# module_RevC_panelized.net
KiCad netlist of a schematic drawn in EAGLE
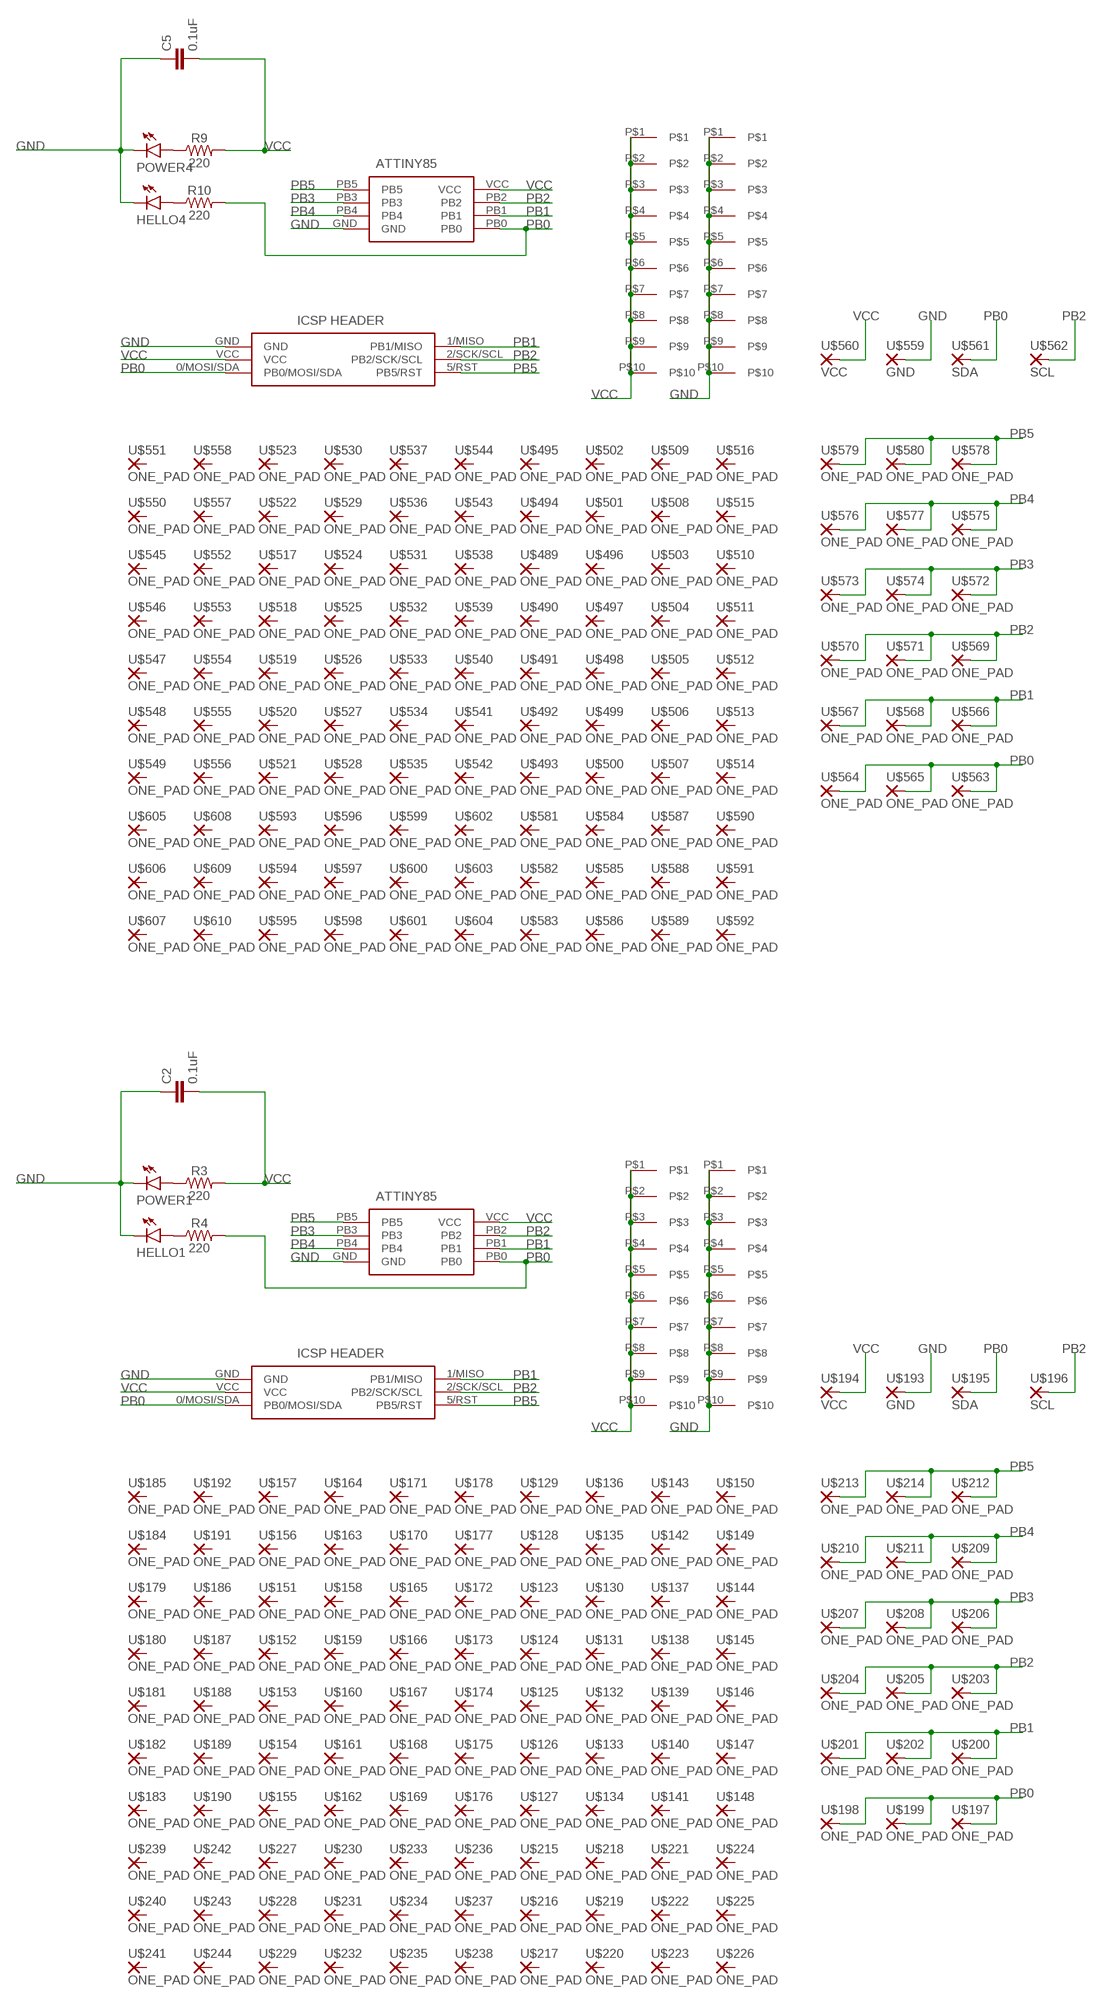
[diagram p0: schematic, sheet 1, part 1 of 2]
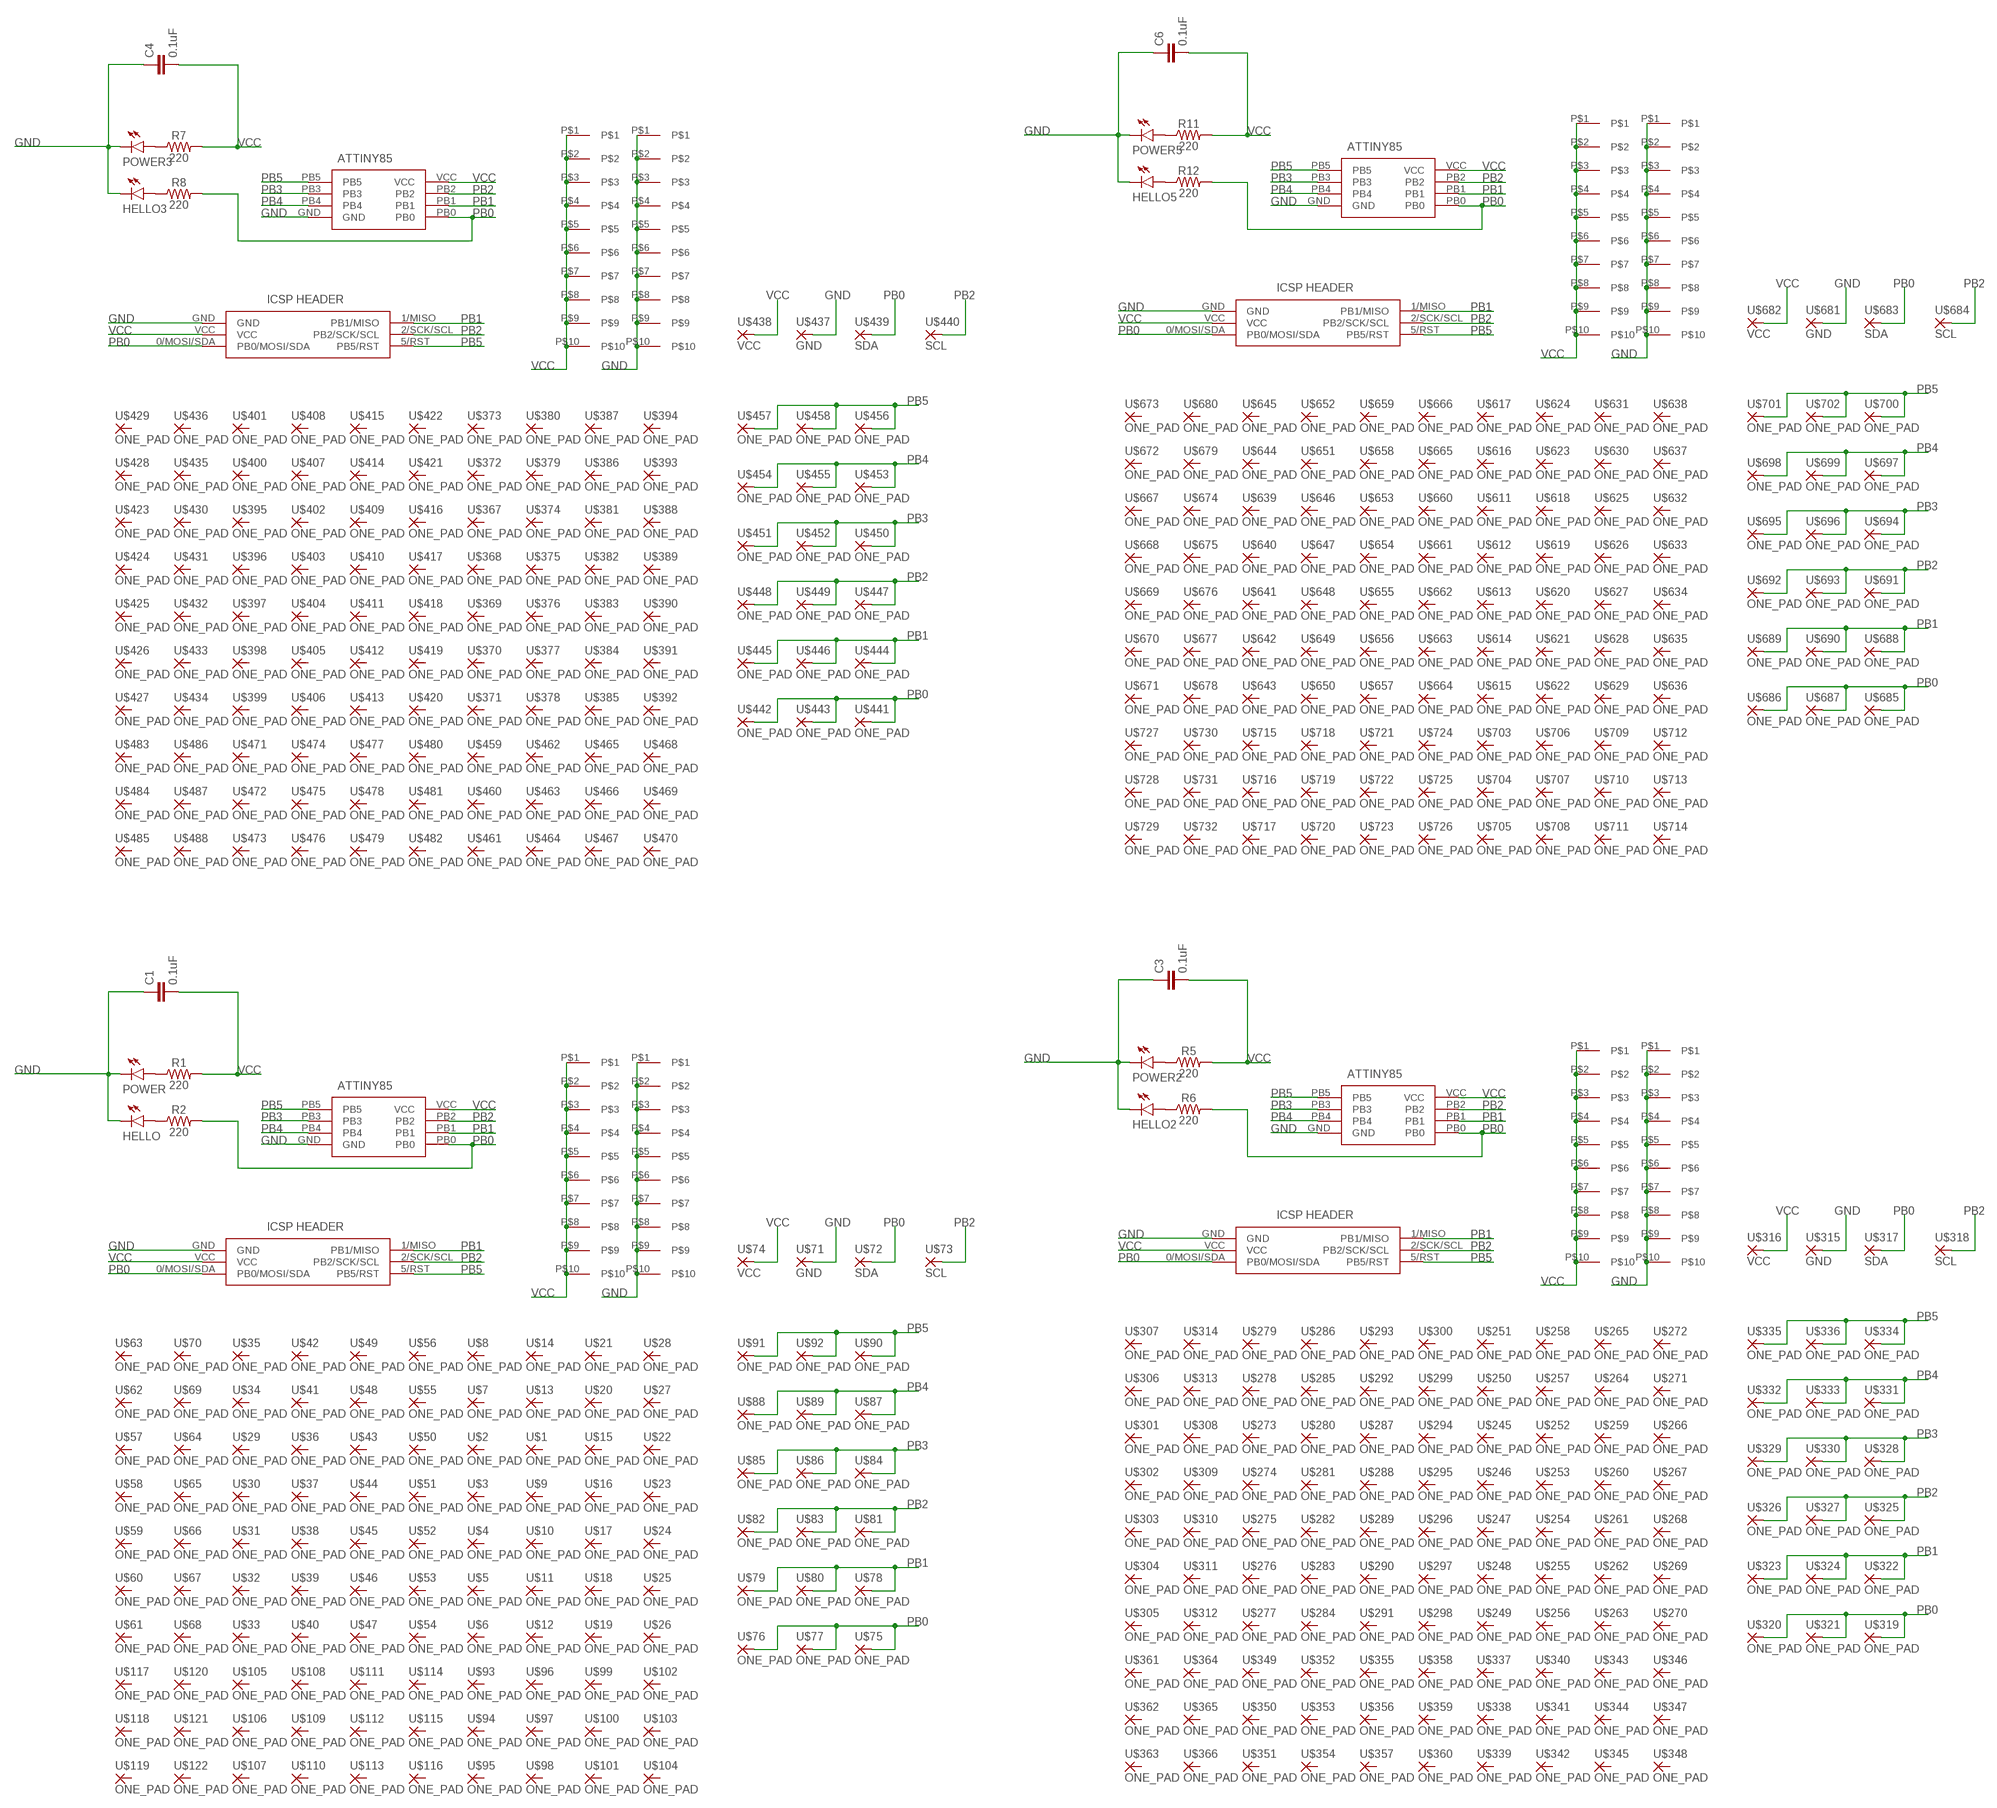
[diagram p1: schematic, sheet 1, part 2 of 2]

(export (version "E")
  (design (tool "Eeschema 10.0.6"))
  (components
    (comp (ref "C1")
      (value "0.1uF")
      (footprint "eagle-import:0603")
      (libsource (lib "eagle-import") (part "0.1UF-0603-25V-5%"))
    )
    (comp (ref "C2")
      (value "0.1uF")
      (footprint "eagle-import:0603")
      (libsource (lib "eagle-import") (part "0.1UF-0603-25V-5%"))
    )
    (comp (ref "C3")
      (value "0.1uF")
      (footprint "eagle-import:0603")
      (libsource (lib "eagle-import") (part "0.1UF-0603-25V-5%"))
    )
    (comp (ref "C4")
      (value "0.1uF")
      (footprint "eagle-import:0603")
      (libsource (lib "eagle-import") (part "0.1UF-0603-25V-5%"))
    )
    (comp (ref "C5")
      (value "0.1uF")
      (footprint "eagle-import:0603")
      (libsource (lib "eagle-import") (part "0.1UF-0603-25V-5%"))
    )
    (comp (ref "C6")
      (value "0.1uF")
      (footprint "eagle-import:0603")
      (libsource (lib "eagle-import") (part "0.1UF-0603-25V-5%"))
    )
    (comp (ref "GND")
      (value "10X-PADS")
      (footprint "eagle-import:10X-PADS")
      (libsource (lib "eagle-import") (part "10X-PADS"))
    )
    (comp (ref "GND1")
      (value "10X-PADS")
      (footprint "eagle-import:10X-PADS")
      (libsource (lib "eagle-import") (part "10X-PADS"))
    )
    (comp (ref "GND2")
      (value "10X-PADS")
      (footprint "eagle-import:10X-PADS")
      (libsource (lib "eagle-import") (part "10X-PADS"))
    )
    (comp (ref "GND3")
      (value "10X-PADS")
      (footprint "eagle-import:10X-PADS")
      (libsource (lib "eagle-import") (part "10X-PADS"))
    )
    (comp (ref "GND4")
      (value "10X-PADS")
      (footprint "eagle-import:10X-PADS")
      (libsource (lib "eagle-import") (part "10X-PADS"))
    )
    (comp (ref "GND5")
      (value "10X-PADS")
      (footprint "eagle-import:10X-PADS")
      (libsource (lib "eagle-import") (part "10X-PADS"))
    )
    (comp (ref "HELLO")
      (value "LED3MM")
      (footprint "eagle-import:LED3MM")
      (libsource (lib "eagle-import") (part "LED3MM"))
    )
    (comp (ref "HELLO1")
      (value "LED3MM")
      (footprint "eagle-import:LED3MM")
      (libsource (lib "eagle-import") (part "LED3MM"))
    )
    (comp (ref "HELLO2")
      (value "LED3MM")
      (footprint "eagle-import:LED3MM")
      (libsource (lib "eagle-import") (part "LED3MM"))
    )
    (comp (ref "HELLO3")
      (value "LED3MM")
      (footprint "eagle-import:LED3MM")
      (libsource (lib "eagle-import") (part "LED3MM"))
    )
    (comp (ref "HELLO4")
      (value "LED3MM")
      (footprint "eagle-import:LED3MM")
      (libsource (lib "eagle-import") (part "LED3MM"))
    )
    (comp (ref "HELLO5")
      (value "LED3MM")
      (footprint "eagle-import:LED3MM")
      (libsource (lib "eagle-import") (part "LED3MM"))
    )
    (comp (ref "IC1")
      (value "ATTINY85-20SU")
      (footprint "eagle-import:SOT127P798X216-8N")
      (fields (field (name "RS_PART_NUMBER") "1331674"))
      (libsource (lib "eagle-import") (part "ATTINY85-20SU"))
    )
    (comp (ref "IC2")
      (value "ATTINY85-20SU")
      (footprint "eagle-import:SOT127P798X216-8N")
      (fields (field (name "RS_PART_NUMBER") "1331674"))
      (libsource (lib "eagle-import") (part "ATTINY85-20SU"))
    )
    (comp (ref "IC3")
      (value "ATTINY85-20SU")
      (footprint "eagle-import:SOT127P798X216-8N")
      (fields (field (name "RS_PART_NUMBER") "1331674"))
      (libsource (lib "eagle-import") (part "ATTINY85-20SU"))
    )
    (comp (ref "IC4")
      (value "ATTINY85-20SU")
      (footprint "eagle-import:SOT127P798X216-8N")
      (fields (field (name "RS_PART_NUMBER") "1331674"))
      (libsource (lib "eagle-import") (part "ATTINY85-20SU"))
    )
    (comp (ref "IC5")
      (value "ATTINY85-20SU")
      (footprint "eagle-import:SOT127P798X216-8N")
      (fields (field (name "RS_PART_NUMBER") "1331674"))
      (libsource (lib "eagle-import") (part "ATTINY85-20SU"))
    )
    (comp (ref "IC6")
      (value "ATTINY85-20SU")
      (footprint "eagle-import:SOT127P798X216-8N")
      (fields (field (name "RS_PART_NUMBER") "1331674"))
      (libsource (lib "eagle-import") (part "ATTINY85-20SU"))
    )
    (comp (ref "J1")
      (value "M20-9980346")
      (footprint "eagle-import:HDRV6W64P254_2X3_762X508X868P")
      (fields (field (name "RS_PART_NUMBER") "7457046P"))
      (libsource (lib "eagle-import") (part "M20-9980346"))
    )
    (comp (ref "J2")
      (value "M20-9980346")
      (footprint "eagle-import:HDRV6W64P254_2X3_762X508X868P")
      (fields (field (name "RS_PART_NUMBER") "7457046P"))
      (libsource (lib "eagle-import") (part "M20-9980346"))
    )
    (comp (ref "J3")
      (value "M20-9980346")
      (footprint "eagle-import:HDRV6W64P254_2X3_762X508X868P")
      (fields (field (name "RS_PART_NUMBER") "7457046P"))
      (libsource (lib "eagle-import") (part "M20-9980346"))
    )
    (comp (ref "J4")
      (value "M20-9980346")
      (footprint "eagle-import:HDRV6W64P254_2X3_762X508X868P")
      (fields (field (name "RS_PART_NUMBER") "7457046P"))
      (libsource (lib "eagle-import") (part "M20-9980346"))
    )
    (comp (ref "J5")
      (value "M20-9980346")
      (footprint "eagle-import:HDRV6W64P254_2X3_762X508X868P")
      (fields (field (name "RS_PART_NUMBER") "7457046P"))
      (libsource (lib "eagle-import") (part "M20-9980346"))
    )
    (comp (ref "J6")
      (value "M20-9980346")
      (footprint "eagle-import:HDRV6W64P254_2X3_762X508X868P")
      (fields (field (name "RS_PART_NUMBER") "7457046P"))
      (libsource (lib "eagle-import") (part "M20-9980346"))
    )
    (comp (ref "POWER")
      (value "LED3MM")
      (footprint "eagle-import:LED3MM")
      (libsource (lib "eagle-import") (part "LED3MM"))
    )
    (comp (ref "POWER1")
      (value "LED3MM")
      (footprint "eagle-import:LED3MM")
      (libsource (lib "eagle-import") (part "LED3MM"))
    )
    (comp (ref "POWER2")
      (value "LED3MM")
      (footprint "eagle-import:LED3MM")
      (libsource (lib "eagle-import") (part "LED3MM"))
    )
    (comp (ref "POWER3")
      (value "LED3MM")
      (footprint "eagle-import:LED3MM")
      (libsource (lib "eagle-import") (part "LED3MM"))
    )
    (comp (ref "POWER4")
      (value "LED3MM")
      (footprint "eagle-import:LED3MM")
      (libsource (lib "eagle-import") (part "LED3MM"))
    )
    (comp (ref "POWER5")
      (value "LED3MM")
      (footprint "eagle-import:LED3MM")
      (libsource (lib "eagle-import") (part "LED3MM"))
    )
    (comp (ref "R1")
      (value "220")
      (footprint "eagle-import:AXIAL-0.3")
      (libsource (lib "eagle-import") (part "RESISTORAXIAL-0.3"))
    )
    (comp (ref "R2")
      (value "220")
      (footprint "eagle-import:AXIAL-0.3")
      (libsource (lib "eagle-import") (part "RESISTORAXIAL-0.3"))
    )
    (comp (ref "R3")
      (value "220")
      (footprint "eagle-import:AXIAL-0.3")
      (libsource (lib "eagle-import") (part "RESISTORAXIAL-0.3"))
    )
    (comp (ref "R4")
      (value "220")
      (footprint "eagle-import:AXIAL-0.3")
      (libsource (lib "eagle-import") (part "RESISTORAXIAL-0.3"))
    )
    (comp (ref "R5")
      (value "220")
      (footprint "eagle-import:AXIAL-0.3")
      (libsource (lib "eagle-import") (part "RESISTORAXIAL-0.3"))
    )
    (comp (ref "R6")
      (value "220")
      (footprint "eagle-import:AXIAL-0.3")
      (libsource (lib "eagle-import") (part "RESISTORAXIAL-0.3"))
    )
    (comp (ref "R7")
      (value "220")
      (footprint "eagle-import:AXIAL-0.3")
      (libsource (lib "eagle-import") (part "RESISTORAXIAL-0.3"))
    )
    (comp (ref "R8")
      (value "220")
      (footprint "eagle-import:AXIAL-0.3")
      (libsource (lib "eagle-import") (part "RESISTORAXIAL-0.3"))
    )
    (comp (ref "R9")
      (value "220")
      (footprint "eagle-import:AXIAL-0.3")
      (libsource (lib "eagle-import") (part "RESISTORAXIAL-0.3"))
    )
    (comp (ref "R10")
      (value "220")
      (footprint "eagle-import:AXIAL-0.3")
      (libsource (lib "eagle-import") (part "RESISTORAXIAL-0.3"))
    )
    (comp (ref "R11")
      (value "220")
      (footprint "eagle-import:AXIAL-0.3")
      (libsource (lib "eagle-import") (part "RESISTORAXIAL-0.3"))
    )
    (comp (ref "R12")
      (value "220")
      (footprint "eagle-import:AXIAL-0.3")
      (libsource (lib "eagle-import") (part "RESISTORAXIAL-0.3"))
    )
    (comp (ref "U$1")
      (value "ONE_PAD")
      (footprint "eagle-import:1X01")
      (libsource (lib "eagle-import") (part "ONE_PAD"))
    )
    (comp (ref "U$2")
      (value "ONE_PAD")
      (footprint "eagle-import:1X01")
      (libsource (lib "eagle-import") (part "ONE_PAD"))
    )
    (comp (ref "U$3")
      (value "ONE_PAD")
      (footprint "eagle-import:1X01")
      (libsource (lib "eagle-import") (part "ONE_PAD"))
    )
    (comp (ref "U$4")
      (value "ONE_PAD")
      (footprint "eagle-import:1X01")
      (libsource (lib "eagle-import") (part "ONE_PAD"))
    )
    (comp (ref "U$5")
      (value "ONE_PAD")
      (footprint "eagle-import:1X01")
      (libsource (lib "eagle-import") (part "ONE_PAD"))
    )
    (comp (ref "U$6")
      (value "ONE_PAD")
      (footprint "eagle-import:1X01")
      (libsource (lib "eagle-import") (part "ONE_PAD"))
    )
    (comp (ref "U$7")
      (value "ONE_PAD")
      (footprint "eagle-import:1X01")
      (libsource (lib "eagle-import") (part "ONE_PAD"))
    )
    (comp (ref "U$8")
      (value "ONE_PAD")
      (footprint "eagle-import:1X01")
      (libsource (lib "eagle-import") (part "ONE_PAD"))
    )
    (comp (ref "U$9")
      (value "ONE_PAD")
      (footprint "eagle-import:1X01")
      (libsource (lib "eagle-import") (part "ONE_PAD"))
    )
    (comp (ref "U$10")
      (value "ONE_PAD")
      (footprint "eagle-import:1X01")
      (libsource (lib "eagle-import") (part "ONE_PAD"))
    )
    (comp (ref "U$11")
      (value "ONE_PAD")
      (footprint "eagle-import:1X01")
      (libsource (lib "eagle-import") (part "ONE_PAD"))
    )
    (comp (ref "U$12")
      (value "ONE_PAD")
      (footprint "eagle-import:1X01")
      (libsource (lib "eagle-import") (part "ONE_PAD"))
    )
    (comp (ref "U$13")
      (value "ONE_PAD")
      (footprint "eagle-import:1X01")
      (libsource (lib "eagle-import") (part "ONE_PAD"))
    )
    (comp (ref "U$14")
      (value "ONE_PAD")
      (footprint "eagle-import:1X01")
      (libsource (lib "eagle-import") (part "ONE_PAD"))
    )
    (comp (ref "U$15")
      (value "ONE_PAD")
      (footprint "eagle-import:1X01")
      (libsource (lib "eagle-import") (part "ONE_PAD"))
    )
    (comp (ref "U$16")
      (value "ONE_PAD")
      (footprint "eagle-import:1X01")
      (libsource (lib "eagle-import") (part "ONE_PAD"))
    )
    (comp (ref "U$17")
      (value "ONE_PAD")
      (footprint "eagle-import:1X01")
      (libsource (lib "eagle-import") (part "ONE_PAD"))
    )
    (comp (ref "U$18")
      (value "ONE_PAD")
      (footprint "eagle-import:1X01")
      (libsource (lib "eagle-import") (part "ONE_PAD"))
    )
    (comp (ref "U$19")
      (value "ONE_PAD")
      (footprint "eagle-import:1X01")
      (libsource (lib "eagle-import") (part "ONE_PAD"))
    )
    (comp (ref "U$20")
      (value "ONE_PAD")
      (footprint "eagle-import:1X01")
      (libsource (lib "eagle-import") (part "ONE_PAD"))
    )
    (comp (ref "U$21")
      (value "ONE_PAD")
      (footprint "eagle-import:1X01")
      (libsource (lib "eagle-import") (part "ONE_PAD"))
    )
    (comp (ref "U$22")
      (value "ONE_PAD")
      (footprint "eagle-import:1X01")
      (libsource (lib "eagle-import") (part "ONE_PAD"))
    )
    (comp (ref "U$23")
      (value "ONE_PAD")
      (footprint "eagle-import:1X01")
      (libsource (lib "eagle-import") (part "ONE_PAD"))
    )
    (comp (ref "U$24")
      (value "ONE_PAD")
      (footprint "eagle-import:1X01")
      (libsource (lib "eagle-import") (part "ONE_PAD"))
    )
    (comp (ref "U$25")
      (value "ONE_PAD")
      (footprint "eagle-import:1X01")
      (libsource (lib "eagle-import") (part "ONE_PAD"))
    )
    (comp (ref "U$26")
      (value "ONE_PAD")
      (footprint "eagle-import:1X01")
      (libsource (lib "eagle-import") (part "ONE_PAD"))
    )
    (comp (ref "U$27")
      (value "ONE_PAD")
      (footprint "eagle-import:1X01")
      (libsource (lib "eagle-import") (part "ONE_PAD"))
    )
    (comp (ref "U$28")
      (value "ONE_PAD")
      (footprint "eagle-import:1X01")
      (libsource (lib "eagle-import") (part "ONE_PAD"))
    )
    (comp (ref "U$29")
      (value "ONE_PAD")
      (footprint "eagle-import:1X01")
      (libsource (lib "eagle-import") (part "ONE_PAD"))
    )
    (comp (ref "U$30")
      (value "ONE_PAD")
      (footprint "eagle-import:1X01")
      (libsource (lib "eagle-import") (part "ONE_PAD"))
    )
    (comp (ref "U$31")
      (value "ONE_PAD")
      (footprint "eagle-import:1X01")
      (libsource (lib "eagle-import") (part "ONE_PAD"))
    )
    (comp (ref "U$32")
      (value "ONE_PAD")
      (footprint "eagle-import:1X01")
      (libsource (lib "eagle-import") (part "ONE_PAD"))
    )
    (comp (ref "U$33")
      (value "ONE_PAD")
      (footprint "eagle-import:1X01")
      (libsource (lib "eagle-import") (part "ONE_PAD"))
    )
    (comp (ref "U$34")
      (value "ONE_PAD")
      (footprint "eagle-import:1X01")
      (libsource (lib "eagle-import") (part "ONE_PAD"))
    )
    (comp (ref "U$35")
      (value "ONE_PAD")
      (footprint "eagle-import:1X01")
      (libsource (lib "eagle-import") (part "ONE_PAD"))
    )
    (comp (ref "U$36")
      (value "ONE_PAD")
      (footprint "eagle-import:1X01")
      (libsource (lib "eagle-import") (part "ONE_PAD"))
    )
    (comp (ref "U$37")
      (value "ONE_PAD")
      (footprint "eagle-import:1X01")
      (libsource (lib "eagle-import") (part "ONE_PAD"))
    )
    (comp (ref "U$38")
      (value "ONE_PAD")
      (footprint "eagle-import:1X01")
      (libsource (lib "eagle-import") (part "ONE_PAD"))
    )
    (comp (ref "U$39")
      (value "ONE_PAD")
      (footprint "eagle-import:1X01")
      (libsource (lib "eagle-import") (part "ONE_PAD"))
    )
    (comp (ref "U$40")
      (value "ONE_PAD")
      (footprint "eagle-import:1X01")
      (libsource (lib "eagle-import") (part "ONE_PAD"))
    )
    (comp (ref "U$41")
      (value "ONE_PAD")
      (footprint "eagle-import:1X01")
      (libsource (lib "eagle-import") (part "ONE_PAD"))
    )
    (comp (ref "U$42")
      (value "ONE_PAD")
      (footprint "eagle-import:1X01")
      (libsource (lib "eagle-import") (part "ONE_PAD"))
    )
    (comp (ref "U$43")
      (value "ONE_PAD")
      (footprint "eagle-import:1X01")
      (libsource (lib "eagle-import") (part "ONE_PAD"))
    )
    (comp (ref "U$44")
      (value "ONE_PAD")
      (footprint "eagle-import:1X01")
      (libsource (lib "eagle-import") (part "ONE_PAD"))
    )
    (comp (ref "U$45")
      (value "ONE_PAD")
      (footprint "eagle-import:1X01")
      (libsource (lib "eagle-import") (part "ONE_PAD"))
    )
    (comp (ref "U$46")
      (value "ONE_PAD")
      (footprint "eagle-import:1X01")
      (libsource (lib "eagle-import") (part "ONE_PAD"))
    )
    (comp (ref "U$47")
      (value "ONE_PAD")
      (footprint "eagle-import:1X01")
      (libsource (lib "eagle-import") (part "ONE_PAD"))
    )
    (comp (ref "U$48")
      (value "ONE_PAD")
      (footprint "eagle-import:1X01")
      (libsource (lib "eagle-import") (part "ONE_PAD"))
    )
    (comp (ref "U$49")
      (value "ONE_PAD")
      (footprint "eagle-import:1X01")
      (libsource (lib "eagle-import") (part "ONE_PAD"))
    )
    (comp (ref "U$50")
      (value "ONE_PAD")
      (footprint "eagle-import:1X01")
      (libsource (lib "eagle-import") (part "ONE_PAD"))
    )
    (comp (ref "U$51")
      (value "ONE_PAD")
      (footprint "eagle-import:1X01")
      (libsource (lib "eagle-import") (part "ONE_PAD"))
    )
    (comp (ref "U$52")
      (value "ONE_PAD")
      (footprint "eagle-import:1X01")
      (libsource (lib "eagle-import") (part "ONE_PAD"))
    )
    (comp (ref "U$53")
      (value "ONE_PAD")
      (footprint "eagle-import:1X01")
      (libsource (lib "eagle-import") (part "ONE_PAD"))
    )
    (comp (ref "U$54")
      (value "ONE_PAD")
      (footprint "eagle-import:1X01")
      (libsource (lib "eagle-import") (part "ONE_PAD"))
    )
    (comp (ref "U$55")
      (value "ONE_PAD")
      (footprint "eagle-import:1X01")
      (libsource (lib "eagle-import") (part "ONE_PAD"))
    )
    (comp (ref "U$56")
      (value "ONE_PAD")
      (footprint "eagle-import:1X01")
      (libsource (lib "eagle-import") (part "ONE_PAD"))
    )
    (comp (ref "U$57")
      (value "ONE_PAD")
      (footprint "eagle-import:1X01")
      (libsource (lib "eagle-import") (part "ONE_PAD"))
    )
    (comp (ref "U$58")
      (value "ONE_PAD")
      (footprint "eagle-import:1X01")
      (libsource (lib "eagle-import") (part "ONE_PAD"))
    )
    (comp (ref "U$59")
      (value "ONE_PAD")
      (footprint "eagle-import:1X01")
      (libsource (lib "eagle-import") (part "ONE_PAD"))
    )
    (comp (ref "U$60")
      (value "ONE_PAD")
      (footprint "eagle-import:1X01")
      (libsource (lib "eagle-import") (part "ONE_PAD"))
    )
    (comp (ref "U$61")
      (value "ONE_PAD")
      (footprint "eagle-import:1X01")
      (libsource (lib "eagle-import") (part "ONE_PAD"))
    )
    (comp (ref "U$62")
      (value "ONE_PAD")
      (footprint "eagle-import:1X01")
      (libsource (lib "eagle-import") (part "ONE_PAD"))
    )
    (comp (ref "U$63")
      (value "ONE_PAD")
      (footprint "eagle-import:1X01")
      (libsource (lib "eagle-import") (part "ONE_PAD"))
    )
    (comp (ref "U$64")
      (value "ONE_PAD")
      (footprint "eagle-import:1X01")
      (libsource (lib "eagle-import") (part "ONE_PAD"))
    )
    (comp (ref "U$65")
      (value "ONE_PAD")
      (footprint "eagle-import:1X01")
      (libsource (lib "eagle-import") (part "ONE_PAD"))
    )
    (comp (ref "U$66")
      (value "ONE_PAD")
      (footprint "eagle-import:1X01")
      (libsource (lib "eagle-import") (part "ONE_PAD"))
    )
    (comp (ref "U$67")
      (value "ONE_PAD")
      (footprint "eagle-import:1X01")
      (libsource (lib "eagle-import") (part "ONE_PAD"))
    )
    (comp (ref "U$68")
      (value "ONE_PAD")
      (footprint "eagle-import:1X01")
      (libsource (lib "eagle-import") (part "ONE_PAD"))
    )
    (comp (ref "U$69")
      (value "ONE_PAD")
      (footprint "eagle-import:1X01")
      (libsource (lib "eagle-import") (part "ONE_PAD"))
    )
    (comp (ref "U$70")
      (value "ONE_PAD")
      (footprint "eagle-import:1X01")
      (libsource (lib "eagle-import") (part "ONE_PAD"))
    )
    (comp (ref "U$71")
      (value "GND")
      (footprint "eagle-import:1X01")
      (libsource (lib "eagle-import") (part "ONE_PAD"))
    )
    (comp (ref "U$72")
      (value "SDA")
      (footprint "eagle-import:1X01")
      (libsource (lib "eagle-import") (part "ONE_PAD"))
    )
    (comp (ref "U$73")
      (value "SCL")
      (footprint "eagle-import:1X01")
      (libsource (lib "eagle-import") (part "ONE_PAD"))
    )
    (comp (ref "U$74")
      (value "VCC")
      (footprint "eagle-import:1X01")
      (libsource (lib "eagle-import") (part "ONE_PAD"))
    )
    (comp (ref "U$75")
      (value "ONE_PAD")
      (footprint "eagle-import:1X01")
      (libsource (lib "eagle-import") (part "ONE_PAD"))
    )
    (comp (ref "U$76")
      (value "ONE_PAD")
      (footprint "eagle-import:1X01")
      (libsource (lib "eagle-import") (part "ONE_PAD"))
    )
    (comp (ref "U$77")
      (value "ONE_PAD")
      (footprint "eagle-import:1X01")
      (libsource (lib "eagle-import") (part "ONE_PAD"))
    )
    (comp (ref "U$78")
      (value "ONE_PAD")
      (footprint "eagle-import:1X01")
      (libsource (lib "eagle-import") (part "ONE_PAD"))
    )
    (comp (ref "U$79")
      (value "ONE_PAD")
      (footprint "eagle-import:1X01")
      (libsource (lib "eagle-import") (part "ONE_PAD"))
    )
    (comp (ref "U$80")
      (value "ONE_PAD")
      (footprint "eagle-import:1X01")
      (libsource (lib "eagle-import") (part "ONE_PAD"))
    )
    (comp (ref "U$81")
      (value "ONE_PAD")
      (footprint "eagle-import:1X01")
      (libsource (lib "eagle-import") (part "ONE_PAD"))
    )
    (comp (ref "U$82")
      (value "ONE_PAD")
      (footprint "eagle-import:1X01")
      (libsource (lib "eagle-import") (part "ONE_PAD"))
    )
    (comp (ref "U$83")
      (value "ONE_PAD")
      (footprint "eagle-import:1X01")
      (libsource (lib "eagle-import") (part "ONE_PAD"))
    )
    (comp (ref "U$84")
      (value "ONE_PAD")
      (footprint "eagle-import:1X01")
      (libsource (lib "eagle-import") (part "ONE_PAD"))
    )
    (comp (ref "U$85")
      (value "ONE_PAD")
      (footprint "eagle-import:1X01")
      (libsource (lib "eagle-import") (part "ONE_PAD"))
    )
    (comp (ref "U$86")
      (value "ONE_PAD")
      (footprint "eagle-import:1X01")
      (libsource (lib "eagle-import") (part "ONE_PAD"))
    )
    (comp (ref "U$87")
      (value "ONE_PAD")
      (footprint "eagle-import:1X01")
      (libsource (lib "eagle-import") (part "ONE_PAD"))
    )
    (comp (ref "U$88")
      (value "ONE_PAD")
      (footprint "eagle-import:1X01")
      (libsource (lib "eagle-import") (part "ONE_PAD"))
    )
    (comp (ref "U$89")
      (value "ONE_PAD")
      (footprint "eagle-import:1X01")
      (libsource (lib "eagle-import") (part "ONE_PAD"))
    )
    (comp (ref "U$90")
      (value "ONE_PAD")
      (footprint "eagle-import:1X01")
      (libsource (lib "eagle-import") (part "ONE_PAD"))
    )
    (comp (ref "U$91")
      (value "ONE_PAD")
      (footprint "eagle-import:1X01")
      (libsource (lib "eagle-import") (part "ONE_PAD"))
    )
    (comp (ref "U$92")
      (value "ONE_PAD")
      (footprint "eagle-import:1X01")
      (libsource (lib "eagle-import") (part "ONE_PAD"))
    )
    (comp (ref "U$93")
      (value "ONE_PAD")
      (footprint "eagle-import:1X01")
      (libsource (lib "eagle-import") (part "ONE_PAD"))
    )
    (comp (ref "U$94")
      (value "ONE_PAD")
      (footprint "eagle-import:1X01")
      (libsource (lib "eagle-import") (part "ONE_PAD"))
    )
    (comp (ref "U$95")
      (value "ONE_PAD")
      (footprint "eagle-import:1X01")
      (libsource (lib "eagle-import") (part "ONE_PAD"))
    )
    (comp (ref "U$96")
      (value "ONE_PAD")
      (footprint "eagle-import:1X01")
      (libsource (lib "eagle-import") (part "ONE_PAD"))
    )
    (comp (ref "U$97")
      (value "ONE_PAD")
      (footprint "eagle-import:1X01")
      (libsource (lib "eagle-import") (part "ONE_PAD"))
    )
    (comp (ref "U$98")
      (value "ONE_PAD")
      (footprint "eagle-import:1X01")
      (libsource (lib "eagle-import") (part "ONE_PAD"))
    )
    (comp (ref "U$99")
      (value "ONE_PAD")
      (footprint "eagle-import:1X01")
      (libsource (lib "eagle-import") (part "ONE_PAD"))
    )
    (comp (ref "U$100")
      (value "ONE_PAD")
      (footprint "eagle-import:1X01")
      (libsource (lib "eagle-import") (part "ONE_PAD"))
    )
    (comp (ref "U$101")
      (value "ONE_PAD")
      (footprint "eagle-import:1X01")
      (libsource (lib "eagle-import") (part "ONE_PAD"))
    )
    (comp (ref "U$102")
      (value "ONE_PAD")
      (footprint "eagle-import:1X01")
      (libsource (lib "eagle-import") (part "ONE_PAD"))
    )
    (comp (ref "U$103")
      (value "ONE_PAD")
      (footprint "eagle-import:1X01")
      (libsource (lib "eagle-import") (part "ONE_PAD"))
    )
    (comp (ref "U$104")
      (value "ONE_PAD")
      (footprint "eagle-import:1X01")
      (libsource (lib "eagle-import") (part "ONE_PAD"))
    )
    (comp (ref "U$105")
      (value "ONE_PAD")
      (footprint "eagle-import:1X01")
      (libsource (lib "eagle-import") (part "ONE_PAD"))
    )
    (comp (ref "U$106")
      (value "ONE_PAD")
      (footprint "eagle-import:1X01")
      (libsource (lib "eagle-import") (part "ONE_PAD"))
    )
    (comp (ref "U$107")
      (value "ONE_PAD")
      (footprint "eagle-import:1X01")
      (libsource (lib "eagle-import") (part "ONE_PAD"))
    )
    (comp (ref "U$108")
      (value "ONE_PAD")
      (footprint "eagle-import:1X01")
      (libsource (lib "eagle-import") (part "ONE_PAD"))
    )
    (comp (ref "U$109")
      (value "ONE_PAD")
      (footprint "eagle-import:1X01")
      (libsource (lib "eagle-import") (part "ONE_PAD"))
    )
    (comp (ref "U$110")
      (value "ONE_PAD")
      (footprint "eagle-import:1X01")
      (libsource (lib "eagle-import") (part "ONE_PAD"))
    )
    (comp (ref "U$111")
      (value "ONE_PAD")
      (footprint "eagle-import:1X01")
      (libsource (lib "eagle-import") (part "ONE_PAD"))
    )
    (comp (ref "U$112")
      (value "ONE_PAD")
      (footprint "eagle-import:1X01")
      (libsource (lib "eagle-import") (part "ONE_PAD"))
    )
    (comp (ref "U$113")
      (value "ONE_PAD")
      (footprint "eagle-import:1X01")
      (libsource (lib "eagle-import") (part "ONE_PAD"))
    )
    (comp (ref "U$114")
      (value "ONE_PAD")
      (footprint "eagle-import:1X01")
      (libsource (lib "eagle-import") (part "ONE_PAD"))
    )
    (comp (ref "U$115")
      (value "ONE_PAD")
      (footprint "eagle-import:1X01")
      (libsource (lib "eagle-import") (part "ONE_PAD"))
    )
    (comp (ref "U$116")
      (value "ONE_PAD")
      (footprint "eagle-import:1X01")
      (libsource (lib "eagle-import") (part "ONE_PAD"))
    )
    (comp (ref "U$117")
      (value "ONE_PAD")
      (footprint "eagle-import:1X01")
      (libsource (lib "eagle-import") (part "ONE_PAD"))
    )
    (comp (ref "U$118")
      (value "ONE_PAD")
      (footprint "eagle-import:1X01")
      (libsource (lib "eagle-import") (part "ONE_PAD"))
    )
    (comp (ref "U$119")
      (value "ONE_PAD")
      (footprint "eagle-import:1X01")
      (libsource (lib "eagle-import") (part "ONE_PAD"))
    )
    (comp (ref "U$120")
      (value "ONE_PAD")
      (footprint "eagle-import:1X01")
      (libsource (lib "eagle-import") (part "ONE_PAD"))
    )
    (comp (ref "U$121")
      (value "ONE_PAD")
      (footprint "eagle-import:1X01")
      (libsource (lib "eagle-import") (part "ONE_PAD"))
    )
    (comp (ref "U$122")
      (value "ONE_PAD")
      (footprint "eagle-import:1X01")
      (libsource (lib "eagle-import") (part "ONE_PAD"))
    )
    (comp (ref "U$123")
      (value "ONE_PAD")
      (footprint "eagle-import:1X01")
      (libsource (lib "eagle-import") (part "ONE_PAD"))
    )
    (comp (ref "U$124")
      (value "ONE_PAD")
      (footprint "eagle-import:1X01")
      (libsource (lib "eagle-import") (part "ONE_PAD"))
    )
    (comp (ref "U$125")
      (value "ONE_PAD")
      (footprint "eagle-import:1X01")
      (libsource (lib "eagle-import") (part "ONE_PAD"))
    )
    (comp (ref "U$126")
      (value "ONE_PAD")
      (footprint "eagle-import:1X01")
      (libsource (lib "eagle-import") (part "ONE_PAD"))
    )
    (comp (ref "U$127")
      (value "ONE_PAD")
      (footprint "eagle-import:1X01")
      (libsource (lib "eagle-import") (part "ONE_PAD"))
    )
    (comp (ref "U$128")
      (value "ONE_PAD")
      (footprint "eagle-import:1X01")
      (libsource (lib "eagle-import") (part "ONE_PAD"))
    )
    (comp (ref "U$129")
      (value "ONE_PAD")
      (footprint "eagle-import:1X01")
      (libsource (lib "eagle-import") (part "ONE_PAD"))
    )
    (comp (ref "U$130")
      (value "ONE_PAD")
      (footprint "eagle-import:1X01")
      (libsource (lib "eagle-import") (part "ONE_PAD"))
    )
    (comp (ref "U$131")
      (value "ONE_PAD")
      (footprint "eagle-import:1X01")
      (libsource (lib "eagle-import") (part "ONE_PAD"))
    )
    (comp (ref "U$132")
      (value "ONE_PAD")
      (footprint "eagle-import:1X01")
      (libsource (lib "eagle-import") (part "ONE_PAD"))
    )
    (comp (ref "U$133")
      (value "ONE_PAD")
      (footprint "eagle-import:1X01")
      (libsource (lib "eagle-import") (part "ONE_PAD"))
    )
    (comp (ref "U$134")
      (value "ONE_PAD")
      (footprint "eagle-import:1X01")
      (libsource (lib "eagle-import") (part "ONE_PAD"))
    )
    (comp (ref "U$135")
      (value "ONE_PAD")
      (footprint "eagle-import:1X01")
      (libsource (lib "eagle-import") (part "ONE_PAD"))
    )
    (comp (ref "U$136")
      (value "ONE_PAD")
      (footprint "eagle-import:1X01")
      (libsource (lib "eagle-import") (part "ONE_PAD"))
    )
    (comp (ref "U$137")
      (value "ONE_PAD")
      (footprint "eagle-import:1X01")
      (libsource (lib "eagle-import") (part "ONE_PAD"))
    )
    (comp (ref "U$138")
      (value "ONE_PAD")
      (footprint "eagle-import:1X01")
      (libsource (lib "eagle-import") (part "ONE_PAD"))
    )
    (comp (ref "U$139")
      (value "ONE_PAD")
      (footprint "eagle-import:1X01")
      (libsource (lib "eagle-import") (part "ONE_PAD"))
    )
    (comp (ref "U$140")
      (value "ONE_PAD")
      (footprint "eagle-import:1X01")
      (libsource (lib "eagle-import") (part "ONE_PAD"))
    )
    (comp (ref "U$141")
      (value "ONE_PAD")
      (footprint "eagle-import:1X01")
      (libsource (lib "eagle-import") (part "ONE_PAD"))
    )
    (comp (ref "U$142")
      (value "ONE_PAD")
      (footprint "eagle-import:1X01")
      (libsource (lib "eagle-import") (part "ONE_PAD"))
    )
    (comp (ref "U$143")
      (value "ONE_PAD")
      (footprint "eagle-import:1X01")
      (libsource (lib "eagle-import") (part "ONE_PAD"))
    )
    (comp (ref "U$144")
      (value "ONE_PAD")
      (footprint "eagle-import:1X01")
      (libsource (lib "eagle-import") (part "ONE_PAD"))
    )
    (comp (ref "U$145")
      (value "ONE_PAD")
      (footprint "eagle-import:1X01")
      (libsource (lib "eagle-import") (part "ONE_PAD"))
    )
    (comp (ref "U$146")
      (value "ONE_PAD")
      (footprint "eagle-import:1X01")
      (libsource (lib "eagle-import") (part "ONE_PAD"))
    )
    (comp (ref "U$147")
      (value "ONE_PAD")
      (footprint "eagle-import:1X01")
      (libsource (lib "eagle-import") (part "ONE_PAD"))
    )
    (comp (ref "U$148")
      (value "ONE_PAD")
      (footprint "eagle-import:1X01")
      (libsource (lib "eagle-import") (part "ONE_PAD"))
    )
    (comp (ref "U$149")
      (value "ONE_PAD")
      (footprint "eagle-import:1X01")
      (libsource (lib "eagle-import") (part "ONE_PAD"))
    )
    (comp (ref "U$150")
      (value "ONE_PAD")
      (footprint "eagle-import:1X01")
      (libsource (lib "eagle-import") (part "ONE_PAD"))
    )
    (comp (ref "U$151")
      (value "ONE_PAD")
      (footprint "eagle-import:1X01")
      (libsource (lib "eagle-import") (part "ONE_PAD"))
    )
    (comp (ref "U$152")
      (value "ONE_PAD")
      (footprint "eagle-import:1X01")
      (libsource (lib "eagle-import") (part "ONE_PAD"))
    )
    (comp (ref "U$153")
      (value "ONE_PAD")
      (footprint "eagle-import:1X01")
      (libsource (lib "eagle-import") (part "ONE_PAD"))
    )
    (comp (ref "U$154")
      (value "ONE_PAD")
      (footprint "eagle-import:1X01")
      (libsource (lib "eagle-import") (part "ONE_PAD"))
    )
    (comp (ref "U$155")
      (value "ONE_PAD")
      (footprint "eagle-import:1X01")
      (libsource (lib "eagle-import") (part "ONE_PAD"))
    )
    (comp (ref "U$156")
      (value "ONE_PAD")
      (footprint "eagle-import:1X01")
      (libsource (lib "eagle-import") (part "ONE_PAD"))
    )
    (comp (ref "U$157")
      (value "ONE_PAD")
      (footprint "eagle-import:1X01")
      (libsource (lib "eagle-import") (part "ONE_PAD"))
    )
    (comp (ref "U$158")
      (value "ONE_PAD")
      (footprint "eagle-import:1X01")
      (libsource (lib "eagle-import") (part "ONE_PAD"))
    )
    (comp (ref "U$159")
      (value "ONE_PAD")
      (footprint "eagle-import:1X01")
      (libsource (lib "eagle-import") (part "ONE_PAD"))
    )
    (comp (ref "U$160")
      (value "ONE_PAD")
      (footprint "eagle-import:1X01")
      (libsource (lib "eagle-import") (part "ONE_PAD"))
    )
    (comp (ref "U$161")
      (value "ONE_PAD")
      (footprint "eagle-import:1X01")
      (libsource (lib "eagle-import") (part "ONE_PAD"))
    )
    (comp (ref "U$162")
      (value "ONE_PAD")
      (footprint "eagle-import:1X01")
      (libsource (lib "eagle-import") (part "ONE_PAD"))
    )
    (comp (ref "U$163")
      (value "ONE_PAD")
      (footprint "eagle-import:1X01")
      (libsource (lib "eagle-import") (part "ONE_PAD"))
    )
    (comp (ref "U$164")
      (value "ONE_PAD")
      (footprint "eagle-import:1X01")
      (libsource (lib "eagle-import") (part "ONE_PAD"))
    )
    (comp (ref "U$165")
      (value "ONE_PAD")
      (footprint "eagle-import:1X01")
      (libsource (lib "eagle-import") (part "ONE_PAD"))
    )
    (comp (ref "U$166")
      (value "ONE_PAD")
      (footprint "eagle-import:1X01")
      (libsource (lib "eagle-import") (part "ONE_PAD"))
    )
    (comp (ref "U$167")
      (value "ONE_PAD")
      (footprint "eagle-import:1X01")
      (libsource (lib "eagle-import") (part "ONE_PAD"))
    )
    (comp (ref "U$168")
      (value "ONE_PAD")
      (footprint "eagle-import:1X01")
      (libsource (lib "eagle-import") (part "ONE_PAD"))
    )
    (comp (ref "U$169")
      (value "ONE_PAD")
      (footprint "eagle-import:1X01")
      (libsource (lib "eagle-import") (part "ONE_PAD"))
    )
    (comp (ref "U$170")
      (value "ONE_PAD")
      (footprint "eagle-import:1X01")
      (libsource (lib "eagle-import") (part "ONE_PAD"))
    )
    (comp (ref "U$171")
      (value "ONE_PAD")
      (footprint "eagle-import:1X01")
      (libsource (lib "eagle-import") (part "ONE_PAD"))
    )
    (comp (ref "U$172")
      (value "ONE_PAD")
      (footprint "eagle-import:1X01")
      (libsource (lib "eagle-import") (part "ONE_PAD"))
    )
    (comp (ref "U$173")
      (value "ONE_PAD")
      (footprint "eagle-import:1X01")
      (libsource (lib "eagle-import") (part "ONE_PAD"))
    )
    (comp (ref "U$174")
      (value "ONE_PAD")
      (footprint "eagle-import:1X01")
      (libsource (lib "eagle-import") (part "ONE_PAD"))
    )
    (comp (ref "U$175")
      (value "ONE_PAD")
      (footprint "eagle-import:1X01")
      (libsource (lib "eagle-import") (part "ONE_PAD"))
    )
    (comp (ref "U$176")
      (value "ONE_PAD")
      (footprint "eagle-import:1X01")
      (libsource (lib "eagle-import") (part "ONE_PAD"))
    )
    (comp (ref "U$177")
      (value "ONE_PAD")
      (footprint "eagle-import:1X01")
      (libsource (lib "eagle-import") (part "ONE_PAD"))
    )
    (comp (ref "U$178")
      (value "ONE_PAD")
      (footprint "eagle-import:1X01")
      (libsource (lib "eagle-import") (part "ONE_PAD"))
    )
    (comp (ref "U$179")
      (value "ONE_PAD")
      (footprint "eagle-import:1X01")
      (libsource (lib "eagle-import") (part "ONE_PAD"))
    )
    (comp (ref "U$180")
      (value "ONE_PAD")
      (footprint "eagle-import:1X01")
      (libsource (lib "eagle-import") (part "ONE_PAD"))
    )
    (comp (ref "U$181")
      (value "ONE_PAD")
      (footprint "eagle-import:1X01")
      (libsource (lib "eagle-import") (part "ONE_PAD"))
    )
    (comp (ref "U$182")
      (value "ONE_PAD")
      (footprint "eagle-import:1X01")
      (libsource (lib "eagle-import") (part "ONE_PAD"))
    )
    (comp (ref "U$183")
      (value "ONE_PAD")
      (footprint "eagle-import:1X01")
      (libsource (lib "eagle-import") (part "ONE_PAD"))
    )
    (comp (ref "U$184")
      (value "ONE_PAD")
      (footprint "eagle-import:1X01")
      (libsource (lib "eagle-import") (part "ONE_PAD"))
    )
    (comp (ref "U$185")
      (value "ONE_PAD")
      (footprint "eagle-import:1X01")
      (libsource (lib "eagle-import") (part "ONE_PAD"))
    )
    (comp (ref "U$186")
      (value "ONE_PAD")
      (footprint "eagle-import:1X01")
      (libsource (lib "eagle-import") (part "ONE_PAD"))
    )
    (comp (ref "U$187")
      (value "ONE_PAD")
      (footprint "eagle-import:1X01")
      (libsource (lib "eagle-import") (part "ONE_PAD"))
    )
    (comp (ref "U$188")
      (value "ONE_PAD")
      (footprint "eagle-import:1X01")
      (libsource (lib "eagle-import") (part "ONE_PAD"))
    )
    (comp (ref "U$189")
      (value "ONE_PAD")
      (footprint "eagle-import:1X01")
      (libsource (lib "eagle-import") (part "ONE_PAD"))
    )
    (comp (ref "U$190")
      (value "ONE_PAD")
      (footprint "eagle-import:1X01")
      (libsource (lib "eagle-import") (part "ONE_PAD"))
    )
    (comp (ref "U$191")
      (value "ONE_PAD")
      (footprint "eagle-import:1X01")
      (libsource (lib "eagle-import") (part "ONE_PAD"))
    )
    (comp (ref "U$192")
      (value "ONE_PAD")
      (footprint "eagle-import:1X01")
      (libsource (lib "eagle-import") (part "ONE_PAD"))
    )
    (comp (ref "U$193")
      (value "GND")
      (footprint "eagle-import:1X01")
      (libsource (lib "eagle-import") (part "ONE_PAD"))
    )
    (comp (ref "U$194")
      (value "VCC")
      (footprint "eagle-import:1X01")
      (libsource (lib "eagle-import") (part "ONE_PAD"))
    )
    (comp (ref "U$195")
      (value "SDA")
      (footprint "eagle-import:1X01")
      (libsource (lib "eagle-import") (part "ONE_PAD"))
    )
    (comp (ref "U$196")
      (value "SCL")
      (footprint "eagle-import:1X01")
      (libsource (lib "eagle-import") (part "ONE_PAD"))
    )
    (comp (ref "U$197")
      (value "ONE_PAD")
      (footprint "eagle-import:1X01")
      (libsource (lib "eagle-import") (part "ONE_PAD"))
    )
    (comp (ref "U$198")
      (value "ONE_PAD")
      (footprint "eagle-import:1X01")
      (libsource (lib "eagle-import") (part "ONE_PAD"))
    )
    (comp (ref "U$199")
      (value "ONE_PAD")
      (footprint "eagle-import:1X01")
      (libsource (lib "eagle-import") (part "ONE_PAD"))
    )
    (comp (ref "U$200")
      (value "ONE_PAD")
      (footprint "eagle-import:1X01")
      (libsource (lib "eagle-import") (part "ONE_PAD"))
    )
    (comp (ref "U$201")
      (value "ONE_PAD")
      (footprint "eagle-import:1X01")
      (libsource (lib "eagle-import") (part "ONE_PAD"))
    )
    (comp (ref "U$202")
      (value "ONE_PAD")
      (footprint "eagle-import:1X01")
      (libsource (lib "eagle-import") (part "ONE_PAD"))
    )
    (comp (ref "U$203")
      (value "ONE_PAD")
      (footprint "eagle-import:1X01")
      (libsource (lib "eagle-import") (part "ONE_PAD"))
    )
    (comp (ref "U$204")
      (value "ONE_PAD")
      (footprint "eagle-import:1X01")
      (libsource (lib "eagle-import") (part "ONE_PAD"))
    )
    (comp (ref "U$205")
      (value "ONE_PAD")
      (footprint "eagle-import:1X01")
      (libsource (lib "eagle-import") (part "ONE_PAD"))
    )
    (comp (ref "U$206")
      (value "ONE_PAD")
      (footprint "eagle-import:1X01")
      (libsource (lib "eagle-import") (part "ONE_PAD"))
    )
    (comp (ref "U$207")
      (value "ONE_PAD")
      (footprint "eagle-import:1X01")
      (libsource (lib "eagle-import") (part "ONE_PAD"))
    )
    (comp (ref "U$208")
      (value "ONE_PAD")
      (footprint "eagle-import:1X01")
      (libsource (lib "eagle-import") (part "ONE_PAD"))
    )
    (comp (ref "U$209")
      (value "ONE_PAD")
      (footprint "eagle-import:1X01")
      (libsource (lib "eagle-import") (part "ONE_PAD"))
    )
    (comp (ref "U$210")
      (value "ONE_PAD")
      (footprint "eagle-import:1X01")
      (libsource (lib "eagle-import") (part "ONE_PAD"))
    )
    (comp (ref "U$211")
      (value "ONE_PAD")
      (footprint "eagle-import:1X01")
      (libsource (lib "eagle-import") (part "ONE_PAD"))
    )
    (comp (ref "U$212")
      (value "ONE_PAD")
      (footprint "eagle-import:1X01")
      (libsource (lib "eagle-import") (part "ONE_PAD"))
    )
    (comp (ref "U$213")
      (value "ONE_PAD")
      (footprint "eagle-import:1X01")
      (libsource (lib "eagle-import") (part "ONE_PAD"))
    )
    (comp (ref "U$214")
      (value "ONE_PAD")
      (footprint "eagle-import:1X01")
      (libsource (lib "eagle-import") (part "ONE_PAD"))
    )
    (comp (ref "U$215")
      (value "ONE_PAD")
      (footprint "eagle-import:1X01")
      (libsource (lib "eagle-import") (part "ONE_PAD"))
    )
    (comp (ref "U$216")
      (value "ONE_PAD")
      (footprint "eagle-import:1X01")
      (libsource (lib "eagle-import") (part "ONE_PAD"))
    )
    (comp (ref "U$217")
      (value "ONE_PAD")
      (footprint "eagle-import:1X01")
      (libsource (lib "eagle-import") (part "ONE_PAD"))
    )
    (comp (ref "U$218")
      (value "ONE_PAD")
      (footprint "eagle-import:1X01")
      (libsource (lib "eagle-import") (part "ONE_PAD"))
    )
    (comp (ref "U$219")
      (value "ONE_PAD")
      (footprint "eagle-import:1X01")
      (libsource (lib "eagle-import") (part "ONE_PAD"))
    )
    (comp (ref "U$220")
      (value "ONE_PAD")
      (footprint "eagle-import:1X01")
      (libsource (lib "eagle-import") (part "ONE_PAD"))
    )
    (comp (ref "U$221")
      (value "ONE_PAD")
      (footprint "eagle-import:1X01")
      (libsource (lib "eagle-import") (part "ONE_PAD"))
    )
    (comp (ref "U$222")
      (value "ONE_PAD")
      (footprint "eagle-import:1X01")
      (libsource (lib "eagle-import") (part "ONE_PAD"))
    )
    (comp (ref "U$223")
      (value "ONE_PAD")
      (footprint "eagle-import:1X01")
      (libsource (lib "eagle-import") (part "ONE_PAD"))
    )
    (comp (ref "U$224")
      (value "ONE_PAD")
      (footprint "eagle-import:1X01")
      (libsource (lib "eagle-import") (part "ONE_PAD"))
    )
    (comp (ref "U$225")
      (value "ONE_PAD")
      (footprint "eagle-import:1X01")
      (libsource (lib "eagle-import") (part "ONE_PAD"))
    )
    (comp (ref "U$226")
      (value "ONE_PAD")
      (footprint "eagle-import:1X01")
      (libsource (lib "eagle-import") (part "ONE_PAD"))
    )
    (comp (ref "U$227")
      (value "ONE_PAD")
      (footprint "eagle-import:1X01")
      (libsource (lib "eagle-import") (part "ONE_PAD"))
    )
    (comp (ref "U$228")
      (value "ONE_PAD")
      (footprint "eagle-import:1X01")
      (libsource (lib "eagle-import") (part "ONE_PAD"))
    )
    (comp (ref "U$229")
      (value "ONE_PAD")
      (footprint "eagle-import:1X01")
      (libsource (lib "eagle-import") (part "ONE_PAD"))
    )
    (comp (ref "U$230")
      (value "ONE_PAD")
      (footprint "eagle-import:1X01")
      (libsource (lib "eagle-import") (part "ONE_PAD"))
    )
    (comp (ref "U$231")
      (value "ONE_PAD")
      (footprint "eagle-import:1X01")
      (libsource (lib "eagle-import") (part "ONE_PAD"))
    )
    (comp (ref "U$232")
      (value "ONE_PAD")
      (footprint "eagle-import:1X01")
      (libsource (lib "eagle-import") (part "ONE_PAD"))
    )
    (comp (ref "U$233")
      (value "ONE_PAD")
      (footprint "eagle-import:1X01")
      (libsource (lib "eagle-import") (part "ONE_PAD"))
    )
    (comp (ref "U$234")
      (value "ONE_PAD")
      (footprint "eagle-import:1X01")
      (libsource (lib "eagle-import") (part "ONE_PAD"))
    )
    (comp (ref "U$235")
      (value "ONE_PAD")
      (footprint "eagle-import:1X01")
      (libsource (lib "eagle-import") (part "ONE_PAD"))
    )
    (comp (ref "U$236")
      (value "ONE_PAD")
      (footprint "eagle-import:1X01")
      (libsource (lib "eagle-import") (part "ONE_PAD"))
    )
    (comp (ref "U$237")
      (value "ONE_PAD")
      (footprint "eagle-import:1X01")
      (libsource (lib "eagle-import") (part "ONE_PAD"))
    )
    (comp (ref "U$238")
      (value "ONE_PAD")
      (footprint "eagle-import:1X01")
      (libsource (lib "eagle-import") (part "ONE_PAD"))
    )
    (comp (ref "U$239")
      (value "ONE_PAD")
      (footprint "eagle-import:1X01")
      (libsource (lib "eagle-import") (part "ONE_PAD"))
    )
    (comp (ref "U$240")
      (value "ONE_PAD")
      (footprint "eagle-import:1X01")
      (libsource (lib "eagle-import") (part "ONE_PAD"))
    )
    (comp (ref "U$241")
      (value "ONE_PAD")
      (footprint "eagle-import:1X01")
      (libsource (lib "eagle-import") (part "ONE_PAD"))
    )
    (comp (ref "U$242")
      (value "ONE_PAD")
      (footprint "eagle-import:1X01")
      (libsource (lib "eagle-import") (part "ONE_PAD"))
    )
    (comp (ref "U$243")
      (value "ONE_PAD")
      (footprint "eagle-import:1X01")
      (libsource (lib "eagle-import") (part "ONE_PAD"))
    )
    (comp (ref "U$244")
      (value "ONE_PAD")
      (footprint "eagle-import:1X01")
      (libsource (lib "eagle-import") (part "ONE_PAD"))
    )
    (comp (ref "U$245")
      (value "ONE_PAD")
      (footprint "eagle-import:1X01")
      (libsource (lib "eagle-import") (part "ONE_PAD"))
    )
    (comp (ref "U$246")
      (value "ONE_PAD")
      (footprint "eagle-import:1X01")
      (libsource (lib "eagle-import") (part "ONE_PAD"))
    )
    (comp (ref "U$247")
      (value "ONE_PAD")
      (footprint "eagle-import:1X01")
      (libsource (lib "eagle-import") (part "ONE_PAD"))
    )
    (comp (ref "U$248")
      (value "ONE_PAD")
      (footprint "eagle-import:1X01")
      (libsource (lib "eagle-import") (part "ONE_PAD"))
    )
    (comp (ref "U$249")
      (value "ONE_PAD")
      (footprint "eagle-import:1X01")
      (libsource (lib "eagle-import") (part "ONE_PAD"))
    )
    (comp (ref "U$250")
      (value "ONE_PAD")
      (footprint "eagle-import:1X01")
      (libsource (lib "eagle-import") (part "ONE_PAD"))
    )
    (comp (ref "U$251")
      (value "ONE_PAD")
      (footprint "eagle-import:1X01")
      (libsource (lib "eagle-import") (part "ONE_PAD"))
    )
    (comp (ref "U$252")
      (value "ONE_PAD")
      (footprint "eagle-import:1X01")
      (libsource (lib "eagle-import") (part "ONE_PAD"))
    )
    (comp (ref "U$253")
      (value "ONE_PAD")
      (footprint "eagle-import:1X01")
      (libsource (lib "eagle-import") (part "ONE_PAD"))
    )
    (comp (ref "U$254")
      (value "ONE_PAD")
      (footprint "eagle-import:1X01")
      (libsource (lib "eagle-import") (part "ONE_PAD"))
    )
    (comp (ref "U$255")
      (value "ONE_PAD")
      (footprint "eagle-import:1X01")
      (libsource (lib "eagle-import") (part "ONE_PAD"))
    )
    (comp (ref "U$256")
      (value "ONE_PAD")
      (footprint "eagle-import:1X01")
      (libsource (lib "eagle-import") (part "ONE_PAD"))
    )
    (comp (ref "U$257")
      (value "ONE_PAD")
      (footprint "eagle-import:1X01")
      (libsource (lib "eagle-import") (part "ONE_PAD"))
    )
    (comp (ref "U$258")
      (value "ONE_PAD")
      (footprint "eagle-import:1X01")
      (libsource (lib "eagle-import") (part "ONE_PAD"))
    )
    (comp (ref "U$259")
      (value "ONE_PAD")
      (footprint "eagle-import:1X01")
      (libsource (lib "eagle-import") (part "ONE_PAD"))
    )
    (comp (ref "U$260")
      (value "ONE_PAD")
      (footprint "eagle-import:1X01")
      (libsource (lib "eagle-import") (part "ONE_PAD"))
    )
    (comp (ref "U$261")
      (value "ONE_PAD")
      (footprint "eagle-import:1X01")
      (libsource (lib "eagle-import") (part "ONE_PAD"))
    )
    (comp (ref "U$262")
      (value "ONE_PAD")
      (footprint "eagle-import:1X01")
      (libsource (lib "eagle-import") (part "ONE_PAD"))
    )
    (comp (ref "U$263")
      (value "ONE_PAD")
      (footprint "eagle-import:1X01")
      (libsource (lib "eagle-import") (part "ONE_PAD"))
    )
    (comp (ref "U$264")
      (value "ONE_PAD")
      (footprint "eagle-import:1X01")
      (libsource (lib "eagle-import") (part "ONE_PAD"))
    )
    (comp (ref "U$265")
      (value "ONE_PAD")
      (footprint "eagle-import:1X01")
      (libsource (lib "eagle-import") (part "ONE_PAD"))
    )
    (comp (ref "U$266")
      (value "ONE_PAD")
      (footprint "eagle-import:1X01")
      (libsource (lib "eagle-import") (part "ONE_PAD"))
    )
    (comp (ref "U$267")
      (value "ONE_PAD")
      (footprint "eagle-import:1X01")
      (libsource (lib "eagle-import") (part "ONE_PAD"))
    )
    (comp (ref "U$268")
      (value "ONE_PAD")
      (footprint "eagle-import:1X01")
      (libsource (lib "eagle-import") (part "ONE_PAD"))
    )
    (comp (ref "U$269")
      (value "ONE_PAD")
      (footprint "eagle-import:1X01")
      (libsource (lib "eagle-import") (part "ONE_PAD"))
    )
    (comp (ref "U$270")
      (value "ONE_PAD")
      (footprint "eagle-import:1X01")
      (libsource (lib "eagle-import") (part "ONE_PAD"))
    )
    (comp (ref "U$271")
      (value "ONE_PAD")
      (footprint "eagle-import:1X01")
      (libsource (lib "eagle-import") (part "ONE_PAD"))
    )
    (comp (ref "U$272")
      (value "ONE_PAD")
      (footprint "eagle-import:1X01")
      (libsource (lib "eagle-import") (part "ONE_PAD"))
    )
    (comp (ref "U$273")
      (value "ONE_PAD")
      (footprint "eagle-import:1X01")
      (libsource (lib "eagle-import") (part "ONE_PAD"))
    )
    (comp (ref "U$274")
      (value "ONE_PAD")
      (footprint "eagle-import:1X01")
      (libsource (lib "eagle-import") (part "ONE_PAD"))
    )
    (comp (ref "U$275")
      (value "ONE_PAD")
      (footprint "eagle-import:1X01")
      (libsource (lib "eagle-import") (part "ONE_PAD"))
    )
    (comp (ref "U$276")
      (value "ONE_PAD")
      (footprint "eagle-import:1X01")
      (libsource (lib "eagle-import") (part "ONE_PAD"))
    )
    (comp (ref "U$277")
      (value "ONE_PAD")
      (footprint "eagle-import:1X01")
      (libsource (lib "eagle-import") (part "ONE_PAD"))
    )
    (comp (ref "U$278")
      (value "ONE_PAD")
      (footprint "eagle-import:1X01")
      (libsource (lib "eagle-import") (part "ONE_PAD"))
    )
    (comp (ref "U$279")
      (value "ONE_PAD")
      (footprint "eagle-import:1X01")
      (libsource (lib "eagle-import") (part "ONE_PAD"))
    )
    (comp (ref "U$280")
      (value "ONE_PAD")
      (footprint "eagle-import:1X01")
      (libsource (lib "eagle-import") (part "ONE_PAD"))
    )
    (comp (ref "U$281")
      (value "ONE_PAD")
      (footprint "eagle-import:1X01")
      (libsource (lib "eagle-import") (part "ONE_PAD"))
    )
    (comp (ref "U$282")
      (value "ONE_PAD")
      (footprint "eagle-import:1X01")
      (libsource (lib "eagle-import") (part "ONE_PAD"))
    )
    (comp (ref "U$283")
      (value "ONE_PAD")
      (footprint "eagle-import:1X01")
      (libsource (lib "eagle-import") (part "ONE_PAD"))
    )
    (comp (ref "U$284")
      (value "ONE_PAD")
      (footprint "eagle-import:1X01")
      (libsource (lib "eagle-import") (part "ONE_PAD"))
    )
    (comp (ref "U$285")
      (value "ONE_PAD")
      (footprint "eagle-import:1X01")
      (libsource (lib "eagle-import") (part "ONE_PAD"))
    )
    (comp (ref "U$286")
      (value "ONE_PAD")
      (footprint "eagle-import:1X01")
      (libsource (lib "eagle-import") (part "ONE_PAD"))
    )
    (comp (ref "U$287")
      (value "ONE_PAD")
      (footprint "eagle-import:1X01")
      (libsource (lib "eagle-import") (part "ONE_PAD"))
    )
    (comp (ref "U$288")
      (value "ONE_PAD")
      (footprint "eagle-import:1X01")
      (libsource (lib "eagle-import") (part "ONE_PAD"))
    )
    (comp (ref "U$289")
      (value "ONE_PAD")
      (footprint "eagle-import:1X01")
      (libsource (lib "eagle-import") (part "ONE_PAD"))
    )
    (comp (ref "U$290")
      (value "ONE_PAD")
      (footprint "eagle-import:1X01")
      (libsource (lib "eagle-import") (part "ONE_PAD"))
    )
    (comp (ref "U$291")
      (value "ONE_PAD")
      (footprint "eagle-import:1X01")
      (libsource (lib "eagle-import") (part "ONE_PAD"))
    )
    (comp (ref "U$292")
      (value "ONE_PAD")
      (footprint "eagle-import:1X01")
      (libsource (lib "eagle-import") (part "ONE_PAD"))
    )
    (comp (ref "U$293")
      (value "ONE_PAD")
      (footprint "eagle-import:1X01")
      (libsource (lib "eagle-import") (part "ONE_PAD"))
    )
    (comp (ref "U$294")
      (value "ONE_PAD")
      (footprint "eagle-import:1X01")
      (libsource (lib "eagle-import") (part "ONE_PAD"))
    )
    (comp (ref "U$295")
      (value "ONE_PAD")
      (footprint "eagle-import:1X01")
      (libsource (lib "eagle-import") (part "ONE_PAD"))
    )
    (comp (ref "U$296")
      (value "ONE_PAD")
      (footprint "eagle-import:1X01")
      (libsource (lib "eagle-import") (part "ONE_PAD"))
    )
    (comp (ref "U$297")
      (value "ONE_PAD")
      (footprint "eagle-import:1X01")
      (libsource (lib "eagle-import") (part "ONE_PAD"))
    )
    (comp (ref "U$298")
      (value "ONE_PAD")
      (footprint "eagle-import:1X01")
      (libsource (lib "eagle-import") (part "ONE_PAD"))
    )
    (comp (ref "U$299")
      (value "ONE_PAD")
      (footprint "eagle-import:1X01")
      (libsource (lib "eagle-import") (part "ONE_PAD"))
    )
    (comp (ref "U$300")
      (value "ONE_PAD")
      (footprint "eagle-import:1X01")
      (libsource (lib "eagle-import") (part "ONE_PAD"))
    )
    (comp (ref "U$301")
      (value "ONE_PAD")
      (footprint "eagle-import:1X01")
      (libsource (lib "eagle-import") (part "ONE_PAD"))
    )
    (comp (ref "U$302")
      (value "ONE_PAD")
      (footprint "eagle-import:1X01")
      (libsource (lib "eagle-import") (part "ONE_PAD"))
    )
    (comp (ref "U$303")
      (value "ONE_PAD")
      (footprint "eagle-import:1X01")
      (libsource (lib "eagle-import") (part "ONE_PAD"))
    )
    (comp (ref "U$304")
      (value "ONE_PAD")
      (footprint "eagle-import:1X01")
      (libsource (lib "eagle-import") (part "ONE_PAD"))
    )
    (comp (ref "U$305")
      (value "ONE_PAD")
      (footprint "eagle-import:1X01")
      (libsource (lib "eagle-import") (part "ONE_PAD"))
    )
    (comp (ref "U$306")
      (value "ONE_PAD")
      (footprint "eagle-import:1X01")
      (libsource (lib "eagle-import") (part "ONE_PAD"))
    )
    (comp (ref "U$307")
      (value "ONE_PAD")
      (footprint "eagle-import:1X01")
      (libsource (lib "eagle-import") (part "ONE_PAD"))
    )
    (comp (ref "U$308")
      (value "ONE_PAD")
      (footprint "eagle-import:1X01")
      (libsource (lib "eagle-import") (part "ONE_PAD"))
    )
    (comp (ref "U$309")
      (value "ONE_PAD")
      (footprint "eagle-import:1X01")
      (libsource (lib "eagle-import") (part "ONE_PAD"))
    )
    (comp (ref "U$310")
      (value "ONE_PAD")
      (footprint "eagle-import:1X01")
      (libsource (lib "eagle-import") (part "ONE_PAD"))
    )
    (comp (ref "U$311")
      (value "ONE_PAD")
      (footprint "eagle-import:1X01")
      (libsource (lib "eagle-import") (part "ONE_PAD"))
    )
    (comp (ref "U$312")
      (value "ONE_PAD")
      (footprint "eagle-import:1X01")
      (libsource (lib "eagle-import") (part "ONE_PAD"))
    )
    (comp (ref "U$313")
      (value "ONE_PAD")
      (footprint "eagle-import:1X01")
      (libsource (lib "eagle-import") (part "ONE_PAD"))
    )
    (comp (ref "U$314")
      (value "ONE_PAD")
      (footprint "eagle-import:1X01")
      (libsource (lib "eagle-import") (part "ONE_PAD"))
    )
    (comp (ref "U$315")
      (value "GND")
      (footprint "eagle-import:1X01")
      (libsource (lib "eagle-import") (part "ONE_PAD"))
    )
    (comp (ref "U$316")
      (value "VCC")
      (footprint "eagle-import:1X01")
      (libsource (lib "eagle-import") (part "ONE_PAD"))
    )
    (comp (ref "U$317")
      (value "SDA")
      (footprint "eagle-import:1X01")
      (libsource (lib "eagle-import") (part "ONE_PAD"))
    )
    (comp (ref "U$318")
      (value "SCL")
      (footprint "eagle-import:1X01")
      (libsource (lib "eagle-import") (part "ONE_PAD"))
    )
    (comp (ref "U$319")
      (value "ONE_PAD")
      (footprint "eagle-import:1X01")
      (libsource (lib "eagle-import") (part "ONE_PAD"))
    )
    (comp (ref "U$320")
      (value "ONE_PAD")
      (footprint "eagle-import:1X01")
      (libsource (lib "eagle-import") (part "ONE_PAD"))
    )
    (comp (ref "U$321")
      (value "ONE_PAD")
      (footprint "eagle-import:1X01")
      (libsource (lib "eagle-import") (part "ONE_PAD"))
    )
    (comp (ref "U$322")
      (value "ONE_PAD")
      (footprint "eagle-import:1X01")
      (libsource (lib "eagle-import") (part "ONE_PAD"))
    )
    (comp (ref "U$323")
      (value "ONE_PAD")
      (footprint "eagle-import:1X01")
      (libsource (lib "eagle-import") (part "ONE_PAD"))
    )
    (comp (ref "U$324")
      (value "ONE_PAD")
      (footprint "eagle-import:1X01")
      (libsource (lib "eagle-import") (part "ONE_PAD"))
    )
    (comp (ref "U$325")
      (value "ONE_PAD")
      (footprint "eagle-import:1X01")
      (libsource (lib "eagle-import") (part "ONE_PAD"))
    )
    (comp (ref "U$326")
      (value "ONE_PAD")
      (footprint "eagle-import:1X01")
      (libsource (lib "eagle-import") (part "ONE_PAD"))
    )
    (comp (ref "U$327")
      (value "ONE_PAD")
      (footprint "eagle-import:1X01")
      (libsource (lib "eagle-import") (part "ONE_PAD"))
    )
    (comp (ref "U$328")
      (value "ONE_PAD")
      (footprint "eagle-import:1X01")
      (libsource (lib "eagle-import") (part "ONE_PAD"))
    )
    (comp (ref "U$329")
      (value "ONE_PAD")
      (footprint "eagle-import:1X01")
      (libsource (lib "eagle-import") (part "ONE_PAD"))
    )
    (comp (ref "U$330")
      (value "ONE_PAD")
      (footprint "eagle-import:1X01")
      (libsource (lib "eagle-import") (part "ONE_PAD"))
    )
    (comp (ref "U$331")
      (value "ONE_PAD")
      (footprint "eagle-import:1X01")
      (libsource (lib "eagle-import") (part "ONE_PAD"))
    )
    (comp (ref "U$332")
      (value "ONE_PAD")
      (footprint "eagle-import:1X01")
      (libsource (lib "eagle-import") (part "ONE_PAD"))
    )
    (comp (ref "U$333")
      (value "ONE_PAD")
      (footprint "eagle-import:1X01")
      (libsource (lib "eagle-import") (part "ONE_PAD"))
    )
    (comp (ref "U$334")
      (value "ONE_PAD")
      (footprint "eagle-import:1X01")
      (libsource (lib "eagle-import") (part "ONE_PAD"))
    )
    (comp (ref "U$335")
      (value "ONE_PAD")
      (footprint "eagle-import:1X01")
      (libsource (lib "eagle-import") (part "ONE_PAD"))
    )
    (comp (ref "U$336")
      (value "ONE_PAD")
      (footprint "eagle-import:1X01")
      (libsource (lib "eagle-import") (part "ONE_PAD"))
    )
    (comp (ref "U$337")
      (value "ONE_PAD")
      (footprint "eagle-import:1X01")
      (libsource (lib "eagle-import") (part "ONE_PAD"))
    )
    (comp (ref "U$338")
      (value "ONE_PAD")
      (footprint "eagle-import:1X01")
      (libsource (lib "eagle-import") (part "ONE_PAD"))
    )
    (comp (ref "U$339")
      (value "ONE_PAD")
      (footprint "eagle-import:1X01")
      (libsource (lib "eagle-import") (part "ONE_PAD"))
    )
    (comp (ref "U$340")
      (value "ONE_PAD")
      (footprint "eagle-import:1X01")
      (libsource (lib "eagle-import") (part "ONE_PAD"))
    )
    (comp (ref "U$341")
      (value "ONE_PAD")
      (footprint "eagle-import:1X01")
      (libsource (lib "eagle-import") (part "ONE_PAD"))
    )
    (comp (ref "U$342")
      (value "ONE_PAD")
      (footprint "eagle-import:1X01")
      (libsource (lib "eagle-import") (part "ONE_PAD"))
    )
    (comp (ref "U$343")
      (value "ONE_PAD")
      (footprint "eagle-import:1X01")
      (libsource (lib "eagle-import") (part "ONE_PAD"))
    )
    (comp (ref "U$344")
      (value "ONE_PAD")
      (footprint "eagle-import:1X01")
      (libsource (lib "eagle-import") (part "ONE_PAD"))
    )
    (comp (ref "U$345")
      (value "ONE_PAD")
      (footprint "eagle-import:1X01")
      (libsource (lib "eagle-import") (part "ONE_PAD"))
    )
    (comp (ref "U$346")
      (value "ONE_PAD")
      (footprint "eagle-import:1X01")
      (libsource (lib "eagle-import") (part "ONE_PAD"))
    )
    (comp (ref "U$347")
      (value "ONE_PAD")
      (footprint "eagle-import:1X01")
      (libsource (lib "eagle-import") (part "ONE_PAD"))
    )
    (comp (ref "U$348")
      (value "ONE_PAD")
      (footprint "eagle-import:1X01")
      (libsource (lib "eagle-import") (part "ONE_PAD"))
    )
    (comp (ref "U$349")
      (value "ONE_PAD")
      (footprint "eagle-import:1X01")
      (libsource (lib "eagle-import") (part "ONE_PAD"))
    )
    (comp (ref "U$350")
      (value "ONE_PAD")
      (footprint "eagle-import:1X01")
      (libsource (lib "eagle-import") (part "ONE_PAD"))
    )
    (comp (ref "U$351")
      (value "ONE_PAD")
      (footprint "eagle-import:1X01")
      (libsource (lib "eagle-import") (part "ONE_PAD"))
    )
    (comp (ref "U$352")
      (value "ONE_PAD")
      (footprint "eagle-import:1X01")
      (libsource (lib "eagle-import") (part "ONE_PAD"))
    )
    (comp (ref "U$353")
      (value "ONE_PAD")
      (footprint "eagle-import:1X01")
      (libsource (lib "eagle-import") (part "ONE_PAD"))
    )
    (comp (ref "U$354")
      (value "ONE_PAD")
      (footprint "eagle-import:1X01")
      (libsource (lib "eagle-import") (part "ONE_PAD"))
    )
    (comp (ref "U$355")
      (value "ONE_PAD")
      (footprint "eagle-import:1X01")
      (libsource (lib "eagle-import") (part "ONE_PAD"))
    )
    (comp (ref "U$356")
      (value "ONE_PAD")
      (footprint "eagle-import:1X01")
      (libsource (lib "eagle-import") (part "ONE_PAD"))
    )
    (comp (ref "U$357")
      (value "ONE_PAD")
      (footprint "eagle-import:1X01")
      (libsource (lib "eagle-import") (part "ONE_PAD"))
    )
    (comp (ref "U$358")
      (value "ONE_PAD")
      (footprint "eagle-import:1X01")
      (libsource (lib "eagle-import") (part "ONE_PAD"))
    )
    (comp (ref "U$359")
      (value "ONE_PAD")
      (footprint "eagle-import:1X01")
      (libsource (lib "eagle-import") (part "ONE_PAD"))
    )
    (comp (ref "U$360")
      (value "ONE_PAD")
      (footprint "eagle-import:1X01")
      (libsource (lib "eagle-import") (part "ONE_PAD"))
    )
    (comp (ref "U$361")
      (value "ONE_PAD")
      (footprint "eagle-import:1X01")
      (libsource (lib "eagle-import") (part "ONE_PAD"))
    )
    (comp (ref "U$362")
      (value "ONE_PAD")
      (footprint "eagle-import:1X01")
      (libsource (lib "eagle-import") (part "ONE_PAD"))
    )
    (comp (ref "U$363")
      (value "ONE_PAD")
      (footprint "eagle-import:1X01")
      (libsource (lib "eagle-import") (part "ONE_PAD"))
    )
    (comp (ref "U$364")
      (value "ONE_PAD")
      (footprint "eagle-import:1X01")
      (libsource (lib "eagle-import") (part "ONE_PAD"))
    )
    (comp (ref "U$365")
      (value "ONE_PAD")
      (footprint "eagle-import:1X01")
      (libsource (lib "eagle-import") (part "ONE_PAD"))
    )
    (comp (ref "U$366")
      (value "ONE_PAD")
      (footprint "eagle-import:1X01")
      (libsource (lib "eagle-import") (part "ONE_PAD"))
    )
    (comp (ref "U$367")
      (value "ONE_PAD")
      (footprint "eagle-import:1X01")
      (libsource (lib "eagle-import") (part "ONE_PAD"))
    )
    (comp (ref "U$368")
      (value "ONE_PAD")
      (footprint "eagle-import:1X01")
      (libsource (lib "eagle-import") (part "ONE_PAD"))
    )
    (comp (ref "U$369")
      (value "ONE_PAD")
      (footprint "eagle-import:1X01")
      (libsource (lib "eagle-import") (part "ONE_PAD"))
    )
    (comp (ref "U$370")
      (value "ONE_PAD")
      (footprint "eagle-import:1X01")
      (libsource (lib "eagle-import") (part "ONE_PAD"))
    )
    (comp (ref "U$371")
      (value "ONE_PAD")
      (footprint "eagle-import:1X01")
      (libsource (lib "eagle-import") (part "ONE_PAD"))
    )
    (comp (ref "U$372")
      (value "ONE_PAD")
      (footprint "eagle-import:1X01")
      (libsource (lib "eagle-import") (part "ONE_PAD"))
    )
    (comp (ref "U$373")
      (value "ONE_PAD")
      (footprint "eagle-import:1X01")
      (libsource (lib "eagle-import") (part "ONE_PAD"))
    )
    (comp (ref "U$374")
      (value "ONE_PAD")
      (footprint "eagle-import:1X01")
      (libsource (lib "eagle-import") (part "ONE_PAD"))
    )
    (comp (ref "U$375")
      (value "ONE_PAD")
      (footprint "eagle-import:1X01")
      (libsource (lib "eagle-import") (part "ONE_PAD"))
    )
    (comp (ref "U$376")
      (value "ONE_PAD")
      (footprint "eagle-import:1X01")
      (libsource (lib "eagle-import") (part "ONE_PAD"))
    )
    (comp (ref "U$377")
      (value "ONE_PAD")
      (footprint "eagle-import:1X01")
      (libsource (lib "eagle-import") (part "ONE_PAD"))
    )
    (comp (ref "U$378")
      (value "ONE_PAD")
      (footprint "eagle-import:1X01")
      (libsource (lib "eagle-import") (part "ONE_PAD"))
    )
    (comp (ref "U$379")
      (value "ONE_PAD")
      (footprint "eagle-import:1X01")
      (libsource (lib "eagle-import") (part "ONE_PAD"))
    )
    (comp (ref "U$380")
      (value "ONE_PAD")
      (footprint "eagle-import:1X01")
      (libsource (lib "eagle-import") (part "ONE_PAD"))
    )
    (comp (ref "U$381")
      (value "ONE_PAD")
      (footprint "eagle-import:1X01")
      (libsource (lib "eagle-import") (part "ONE_PAD"))
    )
    (comp (ref "U$382")
      (value "ONE_PAD")
      (footprint "eagle-import:1X01")
      (libsource (lib "eagle-import") (part "ONE_PAD"))
    )
    (comp (ref "U$383")
      (value "ONE_PAD")
      (footprint "eagle-import:1X01")
      (libsource (lib "eagle-import") (part "ONE_PAD"))
    )
    (comp (ref "U$384")
      (value "ONE_PAD")
      (footprint "eagle-import:1X01")
      (libsource (lib "eagle-import") (part "ONE_PAD"))
    )
    (comp (ref "U$385")
      (value "ONE_PAD")
      (footprint "eagle-import:1X01")
      (libsource (lib "eagle-import") (part "ONE_PAD"))
    )
    (comp (ref "U$386")
      (value "ONE_PAD")
      (footprint "eagle-import:1X01")
      (libsource (lib "eagle-import") (part "ONE_PAD"))
    )
    (comp (ref "U$387")
      (value "ONE_PAD")
      (footprint "eagle-import:1X01")
      (libsource (lib "eagle-import") (part "ONE_PAD"))
    )
    (comp (ref "U$388")
      (value "ONE_PAD")
      (footprint "eagle-import:1X01")
      (libsource (lib "eagle-import") (part "ONE_PAD"))
    )
    (comp (ref "U$389")
      (value "ONE_PAD")
      (footprint "eagle-import:1X01")
      (libsource (lib "eagle-import") (part "ONE_PAD"))
    )
    (comp (ref "U$390")
      (value "ONE_PAD")
      (footprint "eagle-import:1X01")
      (libsource (lib "eagle-import") (part "ONE_PAD"))
    )
    (comp (ref "U$391")
      (value "ONE_PAD")
      (footprint "eagle-import:1X01")
      (libsource (lib "eagle-import") (part "ONE_PAD"))
    )
    (comp (ref "U$392")
      (value "ONE_PAD")
      (footprint "eagle-import:1X01")
      (libsource (lib "eagle-import") (part "ONE_PAD"))
    )
    (comp (ref "U$393")
      (value "ONE_PAD")
      (footprint "eagle-import:1X01")
      (libsource (lib "eagle-import") (part "ONE_PAD"))
    )
    (comp (ref "U$394")
      (value "ONE_PAD")
      (footprint "eagle-import:1X01")
      (libsource (lib "eagle-import") (part "ONE_PAD"))
    )
    (comp (ref "U$395")
      (value "ONE_PAD")
      (footprint "eagle-import:1X01")
      (libsource (lib "eagle-import") (part "ONE_PAD"))
    )
    (comp (ref "U$396")
      (value "ONE_PAD")
      (footprint "eagle-import:1X01")
      (libsource (lib "eagle-import") (part "ONE_PAD"))
    )
    (comp (ref "U$397")
      (value "ONE_PAD")
      (footprint "eagle-import:1X01")
      (libsource (lib "eagle-import") (part "ONE_PAD"))
    )
    (comp (ref "U$398")
      (value "ONE_PAD")
      (footprint "eagle-import:1X01")
      (libsource (lib "eagle-import") (part "ONE_PAD"))
    )
    (comp (ref "U$399")
      (value "ONE_PAD")
      (footprint "eagle-import:1X01")
      (libsource (lib "eagle-import") (part "ONE_PAD"))
    )
    (comp (ref "U$400")
      (value "ONE_PAD")
      (footprint "eagle-import:1X01")
      (libsource (lib "eagle-import") (part "ONE_PAD"))
    )
    (comp (ref "U$401")
      (value "ONE_PAD")
      (footprint "eagle-import:1X01")
      (libsource (lib "eagle-import") (part "ONE_PAD"))
    )
    (comp (ref "U$402")
      (value "ONE_PAD")
      (footprint "eagle-import:1X01")
      (libsource (lib "eagle-import") (part "ONE_PAD"))
    )
    (comp (ref "U$403")
      (value "ONE_PAD")
      (footprint "eagle-import:1X01")
      (libsource (lib "eagle-import") (part "ONE_PAD"))
    )
    (comp (ref "U$404")
      (value "ONE_PAD")
      (footprint "eagle-import:1X01")
      (libsource (lib "eagle-import") (part "ONE_PAD"))
    )
    (comp (ref "U$405")
      (value "ONE_PAD")
      (footprint "eagle-import:1X01")
      (libsource (lib "eagle-import") (part "ONE_PAD"))
    )
    (comp (ref "U$406")
      (value "ONE_PAD")
      (footprint "eagle-import:1X01")
      (libsource (lib "eagle-import") (part "ONE_PAD"))
    )
    (comp (ref "U$407")
      (value "ONE_PAD")
      (footprint "eagle-import:1X01")
      (libsource (lib "eagle-import") (part "ONE_PAD"))
    )
    (comp (ref "U$408")
      (value "ONE_PAD")
      (footprint "eagle-import:1X01")
      (libsource (lib "eagle-import") (part "ONE_PAD"))
    )
    (comp (ref "U$409")
      (value "ONE_PAD")
      (footprint "eagle-import:1X01")
      (libsource (lib "eagle-import") (part "ONE_PAD"))
    )
    (comp (ref "U$410")
      (value "ONE_PAD")
      (footprint "eagle-import:1X01")
      (libsource (lib "eagle-import") (part "ONE_PAD"))
    )
    (comp (ref "U$411")
      (value "ONE_PAD")
      (footprint "eagle-import:1X01")
      (libsource (lib "eagle-import") (part "ONE_PAD"))
    )
    (comp (ref "U$412")
      (value "ONE_PAD")
      (footprint "eagle-import:1X01")
      (libsource (lib "eagle-import") (part "ONE_PAD"))
    )
    (comp (ref "U$413")
      (value "ONE_PAD")
      (footprint "eagle-import:1X01")
      (libsource (lib "eagle-import") (part "ONE_PAD"))
    )
    (comp (ref "U$414")
      (value "ONE_PAD")
      (footprint "eagle-import:1X01")
      (libsource (lib "eagle-import") (part "ONE_PAD"))
    )
    (comp (ref "U$415")
      (value "ONE_PAD")
      (footprint "eagle-import:1X01")
      (libsource (lib "eagle-import") (part "ONE_PAD"))
    )
    (comp (ref "U$416")
      (value "ONE_PAD")
      (footprint "eagle-import:1X01")
      (libsource (lib "eagle-import") (part "ONE_PAD"))
    )
    (comp (ref "U$417")
      (value "ONE_PAD")
      (footprint "eagle-import:1X01")
      (libsource (lib "eagle-import") (part "ONE_PAD"))
    )
    (comp (ref "U$418")
      (value "ONE_PAD")
      (footprint "eagle-import:1X01")
      (libsource (lib "eagle-import") (part "ONE_PAD"))
    )
    (comp (ref "U$419")
      (value "ONE_PAD")
      (footprint "eagle-import:1X01")
      (libsource (lib "eagle-import") (part "ONE_PAD"))
    )
    (comp (ref "U$420")
      (value "ONE_PAD")
      (footprint "eagle-import:1X01")
      (libsource (lib "eagle-import") (part "ONE_PAD"))
    )
    (comp (ref "U$421")
      (value "ONE_PAD")
      (footprint "eagle-import:1X01")
      (libsource (lib "eagle-import") (part "ONE_PAD"))
    )
    (comp (ref "U$422")
      (value "ONE_PAD")
      (footprint "eagle-import:1X01")
      (libsource (lib "eagle-import") (part "ONE_PAD"))
    )
    (comp (ref "U$423")
      (value "ONE_PAD")
      (footprint "eagle-import:1X01")
      (libsource (lib "eagle-import") (part "ONE_PAD"))
    )
    (comp (ref "U$424")
      (value "ONE_PAD")
      (footprint "eagle-import:1X01")
      (libsource (lib "eagle-import") (part "ONE_PAD"))
    )
    (comp (ref "U$425")
      (value "ONE_PAD")
      (footprint "eagle-import:1X01")
      (libsource (lib "eagle-import") (part "ONE_PAD"))
    )
    (comp (ref "U$426")
      (value "ONE_PAD")
      (footprint "eagle-import:1X01")
      (libsource (lib "eagle-import") (part "ONE_PAD"))
    )
    (comp (ref "U$427")
      (value "ONE_PAD")
      (footprint "eagle-import:1X01")
      (libsource (lib "eagle-import") (part "ONE_PAD"))
    )
    (comp (ref "U$428")
      (value "ONE_PAD")
      (footprint "eagle-import:1X01")
      (libsource (lib "eagle-import") (part "ONE_PAD"))
    )
    (comp (ref "U$429")
      (value "ONE_PAD")
      (footprint "eagle-import:1X01")
      (libsource (lib "eagle-import") (part "ONE_PAD"))
    )
    (comp (ref "U$430")
      (value "ONE_PAD")
      (footprint "eagle-import:1X01")
      (libsource (lib "eagle-import") (part "ONE_PAD"))
    )
    (comp (ref "U$431")
      (value "ONE_PAD")
      (footprint "eagle-import:1X01")
      (libsource (lib "eagle-import") (part "ONE_PAD"))
    )
    (comp (ref "U$432")
      (value "ONE_PAD")
      (footprint "eagle-import:1X01")
      (libsource (lib "eagle-import") (part "ONE_PAD"))
    )
    (comp (ref "U$433")
      (value "ONE_PAD")
      (footprint "eagle-import:1X01")
      (libsource (lib "eagle-import") (part "ONE_PAD"))
    )
    (comp (ref "U$434")
      (value "ONE_PAD")
      (footprint "eagle-import:1X01")
      (libsource (lib "eagle-import") (part "ONE_PAD"))
    )
    (comp (ref "U$435")
      (value "ONE_PAD")
      (footprint "eagle-import:1X01")
      (libsource (lib "eagle-import") (part "ONE_PAD"))
    )
    (comp (ref "U$436")
      (value "ONE_PAD")
      (footprint "eagle-import:1X01")
      (libsource (lib "eagle-import") (part "ONE_PAD"))
    )
    (comp (ref "U$437")
      (value "GND")
      (footprint "eagle-import:1X01")
      (libsource (lib "eagle-import") (part "ONE_PAD"))
    )
    (comp (ref "U$438")
      (value "VCC")
      (footprint "eagle-import:1X01")
      (libsource (lib "eagle-import") (part "ONE_PAD"))
    )
    (comp (ref "U$439")
      (value "SDA")
      (footprint "eagle-import:1X01")
      (libsource (lib "eagle-import") (part "ONE_PAD"))
    )
    (comp (ref "U$440")
      (value "SCL")
      (footprint "eagle-import:1X01")
      (libsource (lib "eagle-import") (part "ONE_PAD"))
    )
    (comp (ref "U$441")
      (value "ONE_PAD")
      (footprint "eagle-import:1X01")
      (libsource (lib "eagle-import") (part "ONE_PAD"))
    )
    (comp (ref "U$442")
      (value "ONE_PAD")
      (footprint "eagle-import:1X01")
      (libsource (lib "eagle-import") (part "ONE_PAD"))
    )
    (comp (ref "U$443")
      (value "ONE_PAD")
      (footprint "eagle-import:1X01")
      (libsource (lib "eagle-import") (part "ONE_PAD"))
    )
    (comp (ref "U$444")
      (value "ONE_PAD")
      (footprint "eagle-import:1X01")
      (libsource (lib "eagle-import") (part "ONE_PAD"))
    )
    (comp (ref "U$445")
      (value "ONE_PAD")
      (footprint "eagle-import:1X01")
      (libsource (lib "eagle-import") (part "ONE_PAD"))
    )
    (comp (ref "U$446")
      (value "ONE_PAD")
      (footprint "eagle-import:1X01")
      (libsource (lib "eagle-import") (part "ONE_PAD"))
    )
    (comp (ref "U$447")
      (value "ONE_PAD")
      (footprint "eagle-import:1X01")
      (libsource (lib "eagle-import") (part "ONE_PAD"))
    )
    (comp (ref "U$448")
      (value "ONE_PAD")
      (footprint "eagle-import:1X01")
      (libsource (lib "eagle-import") (part "ONE_PAD"))
    )
    (comp (ref "U$449")
      (value "ONE_PAD")
      (footprint "eagle-import:1X01")
      (libsource (lib "eagle-import") (part "ONE_PAD"))
    )
    (comp (ref "U$450")
      (value "ONE_PAD")
      (footprint "eagle-import:1X01")
      (libsource (lib "eagle-import") (part "ONE_PAD"))
    )
    (comp (ref "U$451")
      (value "ONE_PAD")
      (footprint "eagle-import:1X01")
      (libsource (lib "eagle-import") (part "ONE_PAD"))
    )
    (comp (ref "U$452")
      (value "ONE_PAD")
      (footprint "eagle-import:1X01")
      (libsource (lib "eagle-import") (part "ONE_PAD"))
    )
    (comp (ref "U$453")
      (value "ONE_PAD")
      (footprint "eagle-import:1X01")
      (libsource (lib "eagle-import") (part "ONE_PAD"))
    )
    (comp (ref "U$454")
      (value "ONE_PAD")
      (footprint "eagle-import:1X01")
      (libsource (lib "eagle-import") (part "ONE_PAD"))
    )
    (comp (ref "U$455")
      (value "ONE_PAD")
      (footprint "eagle-import:1X01")
      (libsource (lib "eagle-import") (part "ONE_PAD"))
    )
    (comp (ref "U$456")
      (value "ONE_PAD")
      (footprint "eagle-import:1X01")
      (libsource (lib "eagle-import") (part "ONE_PAD"))
    )
    (comp (ref "U$457")
      (value "ONE_PAD")
      (footprint "eagle-import:1X01")
      (libsource (lib "eagle-import") (part "ONE_PAD"))
    )
    (comp (ref "U$458")
      (value "ONE_PAD")
      (footprint "eagle-import:1X01")
      (libsource (lib "eagle-import") (part "ONE_PAD"))
    )
    (comp (ref "U$459")
      (value "ONE_PAD")
      (footprint "eagle-import:1X01")
      (libsource (lib "eagle-import") (part "ONE_PAD"))
    )
    (comp (ref "U$460")
      (value "ONE_PAD")
      (footprint "eagle-import:1X01")
      (libsource (lib "eagle-import") (part "ONE_PAD"))
    )
    (comp (ref "U$461")
      (value "ONE_PAD")
      (footprint "eagle-import:1X01")
      (libsource (lib "eagle-import") (part "ONE_PAD"))
    )
    (comp (ref "U$462")
      (value "ONE_PAD")
      (footprint "eagle-import:1X01")
      (libsource (lib "eagle-import") (part "ONE_PAD"))
    )
    (comp (ref "U$463")
      (value "ONE_PAD")
      (footprint "eagle-import:1X01")
      (libsource (lib "eagle-import") (part "ONE_PAD"))
    )
    (comp (ref "U$464")
      (value "ONE_PAD")
      (footprint "eagle-import:1X01")
      (libsource (lib "eagle-import") (part "ONE_PAD"))
    )
    (comp (ref "U$465")
      (value "ONE_PAD")
      (footprint "eagle-import:1X01")
      (libsource (lib "eagle-import") (part "ONE_PAD"))
    )
    (comp (ref "U$466")
      (value "ONE_PAD")
      (footprint "eagle-import:1X01")
      (libsource (lib "eagle-import") (part "ONE_PAD"))
    )
    (comp (ref "U$467")
      (value "ONE_PAD")
      (footprint "eagle-import:1X01")
      (libsource (lib "eagle-import") (part "ONE_PAD"))
    )
    (comp (ref "U$468")
      (value "ONE_PAD")
      (footprint "eagle-import:1X01")
      (libsource (lib "eagle-import") (part "ONE_PAD"))
    )
    (comp (ref "U$469")
      (value "ONE_PAD")
      (footprint "eagle-import:1X01")
      (libsource (lib "eagle-import") (part "ONE_PAD"))
    )
    (comp (ref "U$470")
      (value "ONE_PAD")
      (footprint "eagle-import:1X01")
      (libsource (lib "eagle-import") (part "ONE_PAD"))
    )
    (comp (ref "U$471")
      (value "ONE_PAD")
      (footprint "eagle-import:1X01")
      (libsource (lib "eagle-import") (part "ONE_PAD"))
    )
    (comp (ref "U$472")
      (value "ONE_PAD")
      (footprint "eagle-import:1X01")
      (libsource (lib "eagle-import") (part "ONE_PAD"))
    )
    (comp (ref "U$473")
      (value "ONE_PAD")
      (footprint "eagle-import:1X01")
      (libsource (lib "eagle-import") (part "ONE_PAD"))
    )
    (comp (ref "U$474")
      (value "ONE_PAD")
      (footprint "eagle-import:1X01")
      (libsource (lib "eagle-import") (part "ONE_PAD"))
    )
    (comp (ref "U$475")
      (value "ONE_PAD")
      (footprint "eagle-import:1X01")
      (libsource (lib "eagle-import") (part "ONE_PAD"))
    )
    (comp (ref "U$476")
      (value "ONE_PAD")
      (footprint "eagle-import:1X01")
      (libsource (lib "eagle-import") (part "ONE_PAD"))
    )
    (comp (ref "U$477")
      (value "ONE_PAD")
      (footprint "eagle-import:1X01")
      (libsource (lib "eagle-import") (part "ONE_PAD"))
    )
    (comp (ref "U$478")
      (value "ONE_PAD")
      (footprint "eagle-import:1X01")
      (libsource (lib "eagle-import") (part "ONE_PAD"))
    )
    (comp (ref "U$479")
      (value "ONE_PAD")
      (footprint "eagle-import:1X01")
      (libsource (lib "eagle-import") (part "ONE_PAD"))
    )
    (comp (ref "U$480")
      (value "ONE_PAD")
      (footprint "eagle-import:1X01")
      (libsource (lib "eagle-import") (part "ONE_PAD"))
    )
    (comp (ref "U$481")
      (value "ONE_PAD")
      (footprint "eagle-import:1X01")
      (libsource (lib "eagle-import") (part "ONE_PAD"))
    )
    (comp (ref "U$482")
      (value "ONE_PAD")
      (footprint "eagle-import:1X01")
      (libsource (lib "eagle-import") (part "ONE_PAD"))
    )
    (comp (ref "U$483")
      (value "ONE_PAD")
      (footprint "eagle-import:1X01")
      (libsource (lib "eagle-import") (part "ONE_PAD"))
    )
    (comp (ref "U$484")
      (value "ONE_PAD")
      (footprint "eagle-import:1X01")
      (libsource (lib "eagle-import") (part "ONE_PAD"))
    )
    (comp (ref "U$485")
      (value "ONE_PAD")
      (footprint "eagle-import:1X01")
      (libsource (lib "eagle-import") (part "ONE_PAD"))
    )
    (comp (ref "U$486")
      (value "ONE_PAD")
      (footprint "eagle-import:1X01")
      (libsource (lib "eagle-import") (part "ONE_PAD"))
    )
    (comp (ref "U$487")
      (value "ONE_PAD")
      (footprint "eagle-import:1X01")
      (libsource (lib "eagle-import") (part "ONE_PAD"))
    )
    (comp (ref "U$488")
      (value "ONE_PAD")
      (footprint "eagle-import:1X01")
      (libsource (lib "eagle-import") (part "ONE_PAD"))
    )
    (comp (ref "U$489")
      (value "ONE_PAD")
      (footprint "eagle-import:1X01")
      (libsource (lib "eagle-import") (part "ONE_PAD"))
    )
    (comp (ref "U$490")
      (value "ONE_PAD")
      (footprint "eagle-import:1X01")
      (libsource (lib "eagle-import") (part "ONE_PAD"))
    )
    (comp (ref "U$491")
      (value "ONE_PAD")
      (footprint "eagle-import:1X01")
      (libsource (lib "eagle-import") (part "ONE_PAD"))
    )
    (comp (ref "U$492")
      (value "ONE_PAD")
      (footprint "eagle-import:1X01")
      (libsource (lib "eagle-import") (part "ONE_PAD"))
    )
    (comp (ref "U$493")
      (value "ONE_PAD")
      (footprint "eagle-import:1X01")
      (libsource (lib "eagle-import") (part "ONE_PAD"))
    )
    (comp (ref "U$494")
      (value "ONE_PAD")
      (footprint "eagle-import:1X01")
      (libsource (lib "eagle-import") (part "ONE_PAD"))
    )
    (comp (ref "U$495")
      (value "ONE_PAD")
      (footprint "eagle-import:1X01")
      (libsource (lib "eagle-import") (part "ONE_PAD"))
    )
    (comp (ref "U$496")
      (value "ONE_PAD")
      (footprint "eagle-import:1X01")
      (libsource (lib "eagle-import") (part "ONE_PAD"))
    )
    (comp (ref "U$497")
      (value "ONE_PAD")
      (footprint "eagle-import:1X01")
      (libsource (lib "eagle-import") (part "ONE_PAD"))
    )
    (comp (ref "U$498")
      (value "ONE_PAD")
      (footprint "eagle-import:1X01")
      (libsource (lib "eagle-import") (part "ONE_PAD"))
    )
    (comp (ref "U$499")
      (value "ONE_PAD")
      (footprint "eagle-import:1X01")
      (libsource (lib "eagle-import") (part "ONE_PAD"))
    )
    (comp (ref "U$500")
      (value "ONE_PAD")
      (footprint "eagle-import:1X01")
      (libsource (lib "eagle-import") (part "ONE_PAD"))
    )
    (comp (ref "U$501")
      (value "ONE_PAD")
      (footprint "eagle-import:1X01")
      (libsource (lib "eagle-import") (part "ONE_PAD"))
    )
    (comp (ref "U$502")
      (value "ONE_PAD")
      (footprint "eagle-import:1X01")
      (libsource (lib "eagle-import") (part "ONE_PAD"))
    )
    (comp (ref "U$503")
      (value "ONE_PAD")
      (footprint "eagle-import:1X01")
      (libsource (lib "eagle-import") (part "ONE_PAD"))
    )
    (comp (ref "U$504")
      (value "ONE_PAD")
      (footprint "eagle-import:1X01")
      (libsource (lib "eagle-import") (part "ONE_PAD"))
    )
    (comp (ref "U$505")
      (value "ONE_PAD")
      (footprint "eagle-import:1X01")
      (libsource (lib "eagle-import") (part "ONE_PAD"))
    )
    (comp (ref "U$506")
      (value "ONE_PAD")
      (footprint "eagle-import:1X01")
      (libsource (lib "eagle-import") (part "ONE_PAD"))
    )
    (comp (ref "U$507")
      (value "ONE_PAD")
      (footprint "eagle-import:1X01")
      (libsource (lib "eagle-import") (part "ONE_PAD"))
    )
    (comp (ref "U$508")
      (value "ONE_PAD")
      (footprint "eagle-import:1X01")
      (libsource (lib "eagle-import") (part "ONE_PAD"))
    )
    (comp (ref "U$509")
      (value "ONE_PAD")
      (footprint "eagle-import:1X01")
      (libsource (lib "eagle-import") (part "ONE_PAD"))
    )
    (comp (ref "U$510")
      (value "ONE_PAD")
      (footprint "eagle-import:1X01")
      (libsource (lib "eagle-import") (part "ONE_PAD"))
    )
    (comp (ref "U$511")
      (value "ONE_PAD")
      (footprint "eagle-import:1X01")
      (libsource (lib "eagle-import") (part "ONE_PAD"))
    )
    (comp (ref "U$512")
      (value "ONE_PAD")
      (footprint "eagle-import:1X01")
      (libsource (lib "eagle-import") (part "ONE_PAD"))
    )
    (comp (ref "U$513")
      (value "ONE_PAD")
      (footprint "eagle-import:1X01")
      (libsource (lib "eagle-import") (part "ONE_PAD"))
    )
    (comp (ref "U$514")
      (value "ONE_PAD")
      (footprint "eagle-import:1X01")
      (libsource (lib "eagle-import") (part "ONE_PAD"))
    )
    (comp (ref "U$515")
      (value "ONE_PAD")
      (footprint "eagle-import:1X01")
      (libsource (lib "eagle-import") (part "ONE_PAD"))
    )
    (comp (ref "U$516")
      (value "ONE_PAD")
      (footprint "eagle-import:1X01")
      (libsource (lib "eagle-import") (part "ONE_PAD"))
    )
    (comp (ref "U$517")
      (value "ONE_PAD")
      (footprint "eagle-import:1X01")
      (libsource (lib "eagle-import") (part "ONE_PAD"))
    )
    (comp (ref "U$518")
      (value "ONE_PAD")
      (footprint "eagle-import:1X01")
      (libsource (lib "eagle-import") (part "ONE_PAD"))
    )
    (comp (ref "U$519")
      (value "ONE_PAD")
      (footprint "eagle-import:1X01")
      (libsource (lib "eagle-import") (part "ONE_PAD"))
    )
    (comp (ref "U$520")
      (value "ONE_PAD")
      (footprint "eagle-import:1X01")
      (libsource (lib "eagle-import") (part "ONE_PAD"))
    )
    (comp (ref "U$521")
      (value "ONE_PAD")
      (footprint "eagle-import:1X01")
      (libsource (lib "eagle-import") (part "ONE_PAD"))
    )
    (comp (ref "U$522")
      (value "ONE_PAD")
      (footprint "eagle-import:1X01")
      (libsource (lib "eagle-import") (part "ONE_PAD"))
    )
    (comp (ref "U$523")
      (value "ONE_PAD")
      (footprint "eagle-import:1X01")
      (libsource (lib "eagle-import") (part "ONE_PAD"))
    )
    (comp (ref "U$524")
      (value "ONE_PAD")
      (footprint "eagle-import:1X01")
      (libsource (lib "eagle-import") (part "ONE_PAD"))
    )
    (comp (ref "U$525")
      (value "ONE_PAD")
      (footprint "eagle-import:1X01")
      (libsource (lib "eagle-import") (part "ONE_PAD"))
    )
    (comp (ref "U$526")
      (value "ONE_PAD")
      (footprint "eagle-import:1X01")
      (libsource (lib "eagle-import") (part "ONE_PAD"))
    )
    (comp (ref "U$527")
      (value "ONE_PAD")
      (footprint "eagle-import:1X01")
      (libsource (lib "eagle-import") (part "ONE_PAD"))
    )
    (comp (ref "U$528")
      (value "ONE_PAD")
      (footprint "eagle-import:1X01")
      (libsource (lib "eagle-import") (part "ONE_PAD"))
    )
    (comp (ref "U$529")
      (value "ONE_PAD")
      (footprint "eagle-import:1X01")
      (libsource (lib "eagle-import") (part "ONE_PAD"))
    )
    (comp (ref "U$530")
      (value "ONE_PAD")
      (footprint "eagle-import:1X01")
      (libsource (lib "eagle-import") (part "ONE_PAD"))
    )
    (comp (ref "U$531")
      (value "ONE_PAD")
      (footprint "eagle-import:1X01")
      (libsource (lib "eagle-import") (part "ONE_PAD"))
    )
    (comp (ref "U$532")
      (value "ONE_PAD")
      (footprint "eagle-import:1X01")
      (libsource (lib "eagle-import") (part "ONE_PAD"))
    )
    (comp (ref "U$533")
      (value "ONE_PAD")
      (footprint "eagle-import:1X01")
      (libsource (lib "eagle-import") (part "ONE_PAD"))
    )
    (comp (ref "U$534")
      (value "ONE_PAD")
      (footprint "eagle-import:1X01")
      (libsource (lib "eagle-import") (part "ONE_PAD"))
    )
    (comp (ref "U$535")
      (value "ONE_PAD")
      (footprint "eagle-import:1X01")
      (libsource (lib "eagle-import") (part "ONE_PAD"))
    )
    (comp (ref "U$536")
      (value "ONE_PAD")
      (footprint "eagle-import:1X01")
      (libsource (lib "eagle-import") (part "ONE_PAD"))
    )
    (comp (ref "U$537")
      (value "ONE_PAD")
      (footprint "eagle-import:1X01")
      (libsource (lib "eagle-import") (part "ONE_PAD"))
    )
    (comp (ref "U$538")
      (value "ONE_PAD")
      (footprint "eagle-import:1X01")
      (libsource (lib "eagle-import") (part "ONE_PAD"))
    )
    (comp (ref "U$539")
      (value "ONE_PAD")
      (footprint "eagle-import:1X01")
      (libsource (lib "eagle-import") (part "ONE_PAD"))
    )
    (comp (ref "U$540")
      (value "ONE_PAD")
      (footprint "eagle-import:1X01")
      (libsource (lib "eagle-import") (part "ONE_PAD"))
    )
    (comp (ref "U$541")
      (value "ONE_PAD")
      (footprint "eagle-import:1X01")
      (libsource (lib "eagle-import") (part "ONE_PAD"))
    )
    (comp (ref "U$542")
      (value "ONE_PAD")
      (footprint "eagle-import:1X01")
      (libsource (lib "eagle-import") (part "ONE_PAD"))
    )
    (comp (ref "U$543")
      (value "ONE_PAD")
      (footprint "eagle-import:1X01")
      (libsource (lib "eagle-import") (part "ONE_PAD"))
    )
    (comp (ref "U$544")
      (value "ONE_PAD")
      (footprint "eagle-import:1X01")
      (libsource (lib "eagle-import") (part "ONE_PAD"))
    )
    (comp (ref "U$545")
      (value "ONE_PAD")
      (footprint "eagle-import:1X01")
      (libsource (lib "eagle-import") (part "ONE_PAD"))
    )
    (comp (ref "U$546")
      (value "ONE_PAD")
      (footprint "eagle-import:1X01")
      (libsource (lib "eagle-import") (part "ONE_PAD"))
    )
    (comp (ref "U$547")
      (value "ONE_PAD")
      (footprint "eagle-import:1X01")
      (libsource (lib "eagle-import") (part "ONE_PAD"))
    )
    (comp (ref "U$548")
      (value "ONE_PAD")
      (footprint "eagle-import:1X01")
      (libsource (lib "eagle-import") (part "ONE_PAD"))
    )
    (comp (ref "U$549")
      (value "ONE_PAD")
      (footprint "eagle-import:1X01")
      (libsource (lib "eagle-import") (part "ONE_PAD"))
    )
    (comp (ref "U$550")
      (value "ONE_PAD")
      (footprint "eagle-import:1X01")
      (libsource (lib "eagle-import") (part "ONE_PAD"))
    )
    (comp (ref "U$551")
      (value "ONE_PAD")
      (footprint "eagle-import:1X01")
      (libsource (lib "eagle-import") (part "ONE_PAD"))
    )
    (comp (ref "U$552")
      (value "ONE_PAD")
      (footprint "eagle-import:1X01")
      (libsource (lib "eagle-import") (part "ONE_PAD"))
    )
    (comp (ref "U$553")
      (value "ONE_PAD")
      (footprint "eagle-import:1X01")
      (libsource (lib "eagle-import") (part "ONE_PAD"))
    )
    (comp (ref "U$554")
      (value "ONE_PAD")
      (footprint "eagle-import:1X01")
      (libsource (lib "eagle-import") (part "ONE_PAD"))
    )
    (comp (ref "U$555")
      (value "ONE_PAD")
      (footprint "eagle-import:1X01")
      (libsource (lib "eagle-import") (part "ONE_PAD"))
    )
    (comp (ref "U$556")
      (value "ONE_PAD")
      (footprint "eagle-import:1X01")
      (libsource (lib "eagle-import") (part "ONE_PAD"))
    )
    (comp (ref "U$557")
      (value "ONE_PAD")
      (footprint "eagle-import:1X01")
      (libsource (lib "eagle-import") (part "ONE_PAD"))
    )
    (comp (ref "U$558")
      (value "ONE_PAD")
      (footprint "eagle-import:1X01")
      (libsource (lib "eagle-import") (part "ONE_PAD"))
    )
    (comp (ref "U$559")
      (value "GND")
      (footprint "eagle-import:1X01")
      (libsource (lib "eagle-import") (part "ONE_PAD"))
    )
    (comp (ref "U$560")
      (value "VCC")
      (footprint "eagle-import:1X01")
      (libsource (lib "eagle-import") (part "ONE_PAD"))
    )
    (comp (ref "U$561")
      (value "SDA")
      (footprint "eagle-import:1X01")
      (libsource (lib "eagle-import") (part "ONE_PAD"))
    )
    (comp (ref "U$562")
      (value "SCL")
      (footprint "eagle-import:1X01")
      (libsource (lib "eagle-import") (part "ONE_PAD"))
    )
    (comp (ref "U$563")
      (value "ONE_PAD")
      (footprint "eagle-import:1X01")
      (libsource (lib "eagle-import") (part "ONE_PAD"))
    )
    (comp (ref "U$564")
      (value "ONE_PAD")
      (footprint "eagle-import:1X01")
      (libsource (lib "eagle-import") (part "ONE_PAD"))
    )
    (comp (ref "U$565")
      (value "ONE_PAD")
      (footprint "eagle-import:1X01")
      (libsource (lib "eagle-import") (part "ONE_PAD"))
    )
    (comp (ref "U$566")
      (value "ONE_PAD")
      (footprint "eagle-import:1X01")
      (libsource (lib "eagle-import") (part "ONE_PAD"))
    )
    (comp (ref "U$567")
      (value "ONE_PAD")
      (footprint "eagle-import:1X01")
      (libsource (lib "eagle-import") (part "ONE_PAD"))
    )
    (comp (ref "U$568")
      (value "ONE_PAD")
      (footprint "eagle-import:1X01")
      (libsource (lib "eagle-import") (part "ONE_PAD"))
    )
    (comp (ref "U$569")
      (value "ONE_PAD")
      (footprint "eagle-import:1X01")
      (libsource (lib "eagle-import") (part "ONE_PAD"))
    )
    (comp (ref "U$570")
      (value "ONE_PAD")
      (footprint "eagle-import:1X01")
      (libsource (lib "eagle-import") (part "ONE_PAD"))
    )
    (comp (ref "U$571")
      (value "ONE_PAD")
      (footprint "eagle-import:1X01")
      (libsource (lib "eagle-import") (part "ONE_PAD"))
    )
    (comp (ref "U$572")
      (value "ONE_PAD")
      (footprint "eagle-import:1X01")
      (libsource (lib "eagle-import") (part "ONE_PAD"))
    )
    (comp (ref "U$573")
      (value "ONE_PAD")
      (footprint "eagle-import:1X01")
      (libsource (lib "eagle-import") (part "ONE_PAD"))
    )
    (comp (ref "U$574")
      (value "ONE_PAD")
      (footprint "eagle-import:1X01")
      (libsource (lib "eagle-import") (part "ONE_PAD"))
    )
    (comp (ref "U$575")
      (value "ONE_PAD")
      (footprint "eagle-import:1X01")
      (libsource (lib "eagle-import") (part "ONE_PAD"))
    )
    (comp (ref "U$576")
      (value "ONE_PAD")
      (footprint "eagle-import:1X01")
      (libsource (lib "eagle-import") (part "ONE_PAD"))
    )
    (comp (ref "U$577")
      (value "ONE_PAD")
      (footprint "eagle-import:1X01")
      (libsource (lib "eagle-import") (part "ONE_PAD"))
    )
    (comp (ref "U$578")
      (value "ONE_PAD")
      (footprint "eagle-import:1X01")
      (libsource (lib "eagle-import") (part "ONE_PAD"))
    )
    (comp (ref "U$579")
      (value "ONE_PAD")
      (footprint "eagle-import:1X01")
      (libsource (lib "eagle-import") (part "ONE_PAD"))
    )
    (comp (ref "U$580")
      (value "ONE_PAD")
      (footprint "eagle-import:1X01")
      (libsource (lib "eagle-import") (part "ONE_PAD"))
    )
    (comp (ref "U$581")
      (value "ONE_PAD")
      (footprint "eagle-import:1X01")
      (libsource (lib "eagle-import") (part "ONE_PAD"))
    )
    (comp (ref "U$582")
      (value "ONE_PAD")
      (footprint "eagle-import:1X01")
      (libsource (lib "eagle-import") (part "ONE_PAD"))
    )
    (comp (ref "U$583")
      (value "ONE_PAD")
      (footprint "eagle-import:1X01")
      (libsource (lib "eagle-import") (part "ONE_PAD"))
    )
    (comp (ref "U$584")
      (value "ONE_PAD")
      (footprint "eagle-import:1X01")
      (libsource (lib "eagle-import") (part "ONE_PAD"))
    )
    (comp (ref "U$585")
      (value "ONE_PAD")
      (footprint "eagle-import:1X01")
      (libsource (lib "eagle-import") (part "ONE_PAD"))
    )
    (comp (ref "U$586")
      (value "ONE_PAD")
      (footprint "eagle-import:1X01")
      (libsource (lib "eagle-import") (part "ONE_PAD"))
    )
    (comp (ref "U$587")
      (value "ONE_PAD")
      (footprint "eagle-import:1X01")
      (libsource (lib "eagle-import") (part "ONE_PAD"))
    )
    (comp (ref "U$588")
      (value "ONE_PAD")
      (footprint "eagle-import:1X01")
      (libsource (lib "eagle-import") (part "ONE_PAD"))
    )
    (comp (ref "U$589")
      (value "ONE_PAD")
      (footprint "eagle-import:1X01")
      (libsource (lib "eagle-import") (part "ONE_PAD"))
    )
    (comp (ref "U$590")
      (value "ONE_PAD")
      (footprint "eagle-import:1X01")
      (libsource (lib "eagle-import") (part "ONE_PAD"))
    )
    (comp (ref "U$591")
      (value "ONE_PAD")
      (footprint "eagle-import:1X01")
      (libsource (lib "eagle-import") (part "ONE_PAD"))
    )
    (comp (ref "U$592")
      (value "ONE_PAD")
      (footprint "eagle-import:1X01")
      (libsource (lib "eagle-import") (part "ONE_PAD"))
    )
    (comp (ref "U$593")
      (value "ONE_PAD")
      (footprint "eagle-import:1X01")
      (libsource (lib "eagle-import") (part "ONE_PAD"))
    )
    (comp (ref "U$594")
      (value "ONE_PAD")
      (footprint "eagle-import:1X01")
      (libsource (lib "eagle-import") (part "ONE_PAD"))
    )
    (comp (ref "U$595")
      (value "ONE_PAD")
      (footprint "eagle-import:1X01")
      (libsource (lib "eagle-import") (part "ONE_PAD"))
    )
    (comp (ref "U$596")
      (value "ONE_PAD")
      (footprint "eagle-import:1X01")
      (libsource (lib "eagle-import") (part "ONE_PAD"))
    )
    (comp (ref "U$597")
      (value "ONE_PAD")
      (footprint "eagle-import:1X01")
      (libsource (lib "eagle-import") (part "ONE_PAD"))
    )
    (comp (ref "U$598")
      (value "ONE_PAD")
      (footprint "eagle-import:1X01")
      (libsource (lib "eagle-import") (part "ONE_PAD"))
    )
    (comp (ref "U$599")
      (value "ONE_PAD")
      (footprint "eagle-import:1X01")
      (libsource (lib "eagle-import") (part "ONE_PAD"))
    )
    (comp (ref "U$600")
      (value "ONE_PAD")
      (footprint "eagle-import:1X01")
      (libsource (lib "eagle-import") (part "ONE_PAD"))
    )
    (comp (ref "U$601")
      (value "ONE_PAD")
      (footprint "eagle-import:1X01")
      (libsource (lib "eagle-import") (part "ONE_PAD"))
    )
    (comp (ref "U$602")
      (value "ONE_PAD")
      (footprint "eagle-import:1X01")
      (libsource (lib "eagle-import") (part "ONE_PAD"))
    )
    (comp (ref "U$603")
      (value "ONE_PAD")
      (footprint "eagle-import:1X01")
      (libsource (lib "eagle-import") (part "ONE_PAD"))
    )
    (comp (ref "U$604")
      (value "ONE_PAD")
      (footprint "eagle-import:1X01")
      (libsource (lib "eagle-import") (part "ONE_PAD"))
    )
    (comp (ref "U$605")
      (value "ONE_PAD")
      (footprint "eagle-import:1X01")
      (libsource (lib "eagle-import") (part "ONE_PAD"))
    )
    (comp (ref "U$606")
      (value "ONE_PAD")
      (footprint "eagle-import:1X01")
      (libsource (lib "eagle-import") (part "ONE_PAD"))
    )
    (comp (ref "U$607")
      (value "ONE_PAD")
      (footprint "eagle-import:1X01")
      (libsource (lib "eagle-import") (part "ONE_PAD"))
    )
    (comp (ref "U$608")
      (value "ONE_PAD")
      (footprint "eagle-import:1X01")
      (libsource (lib "eagle-import") (part "ONE_PAD"))
    )
    (comp (ref "U$609")
      (value "ONE_PAD")
      (footprint "eagle-import:1X01")
      (libsource (lib "eagle-import") (part "ONE_PAD"))
    )
    (comp (ref "U$610")
      (value "ONE_PAD")
      (footprint "eagle-import:1X01")
      (libsource (lib "eagle-import") (part "ONE_PAD"))
    )
    (comp (ref "U$611")
      (value "ONE_PAD")
      (footprint "eagle-import:1X01")
      (libsource (lib "eagle-import") (part "ONE_PAD"))
    )
    (comp (ref "U$612")
      (value "ONE_PAD")
      (footprint "eagle-import:1X01")
      (libsource (lib "eagle-import") (part "ONE_PAD"))
    )
    (comp (ref "U$613")
      (value "ONE_PAD")
      (footprint "eagle-import:1X01")
      (libsource (lib "eagle-import") (part "ONE_PAD"))
    )
    (comp (ref "U$614")
      (value "ONE_PAD")
      (footprint "eagle-import:1X01")
      (libsource (lib "eagle-import") (part "ONE_PAD"))
    )
    (comp (ref "U$615")
      (value "ONE_PAD")
      (footprint "eagle-import:1X01")
      (libsource (lib "eagle-import") (part "ONE_PAD"))
    )
    (comp (ref "U$616")
      (value "ONE_PAD")
      (footprint "eagle-import:1X01")
      (libsource (lib "eagle-import") (part "ONE_PAD"))
    )
    (comp (ref "U$617")
      (value "ONE_PAD")
      (footprint "eagle-import:1X01")
      (libsource (lib "eagle-import") (part "ONE_PAD"))
    )
    (comp (ref "U$618")
      (value "ONE_PAD")
      (footprint "eagle-import:1X01")
      (libsource (lib "eagle-import") (part "ONE_PAD"))
    )
    (comp (ref "U$619")
      (value "ONE_PAD")
      (footprint "eagle-import:1X01")
      (libsource (lib "eagle-import") (part "ONE_PAD"))
    )
    (comp (ref "U$620")
      (value "ONE_PAD")
      (footprint "eagle-import:1X01")
      (libsource (lib "eagle-import") (part "ONE_PAD"))
    )
    (comp (ref "U$621")
      (value "ONE_PAD")
      (footprint "eagle-import:1X01")
      (libsource (lib "eagle-import") (part "ONE_PAD"))
    )
    (comp (ref "U$622")
      (value "ONE_PAD")
      (footprint "eagle-import:1X01")
      (libsource (lib "eagle-import") (part "ONE_PAD"))
    )
    (comp (ref "U$623")
      (value "ONE_PAD")
      (footprint "eagle-import:1X01")
      (libsource (lib "eagle-import") (part "ONE_PAD"))
    )
    (comp (ref "U$624")
      (value "ONE_PAD")
      (footprint "eagle-import:1X01")
      (libsource (lib "eagle-import") (part "ONE_PAD"))
    )
    (comp (ref "U$625")
      (value "ONE_PAD")
      (footprint "eagle-import:1X01")
      (libsource (lib "eagle-import") (part "ONE_PAD"))
    )
    (comp (ref "U$626")
      (value "ONE_PAD")
      (footprint "eagle-import:1X01")
      (libsource (lib "eagle-import") (part "ONE_PAD"))
    )
    (comp (ref "U$627")
      (value "ONE_PAD")
      (footprint "eagle-import:1X01")
      (libsource (lib "eagle-import") (part "ONE_PAD"))
    )
    (comp (ref "U$628")
      (value "ONE_PAD")
      (footprint "eagle-import:1X01")
      (libsource (lib "eagle-import") (part "ONE_PAD"))
    )
    (comp (ref "U$629")
      (value "ONE_PAD")
      (footprint "eagle-import:1X01")
      (libsource (lib "eagle-import") (part "ONE_PAD"))
    )
    (comp (ref "U$630")
      (value "ONE_PAD")
      (footprint "eagle-import:1X01")
      (libsource (lib "eagle-import") (part "ONE_PAD"))
    )
    (comp (ref "U$631")
      (value "ONE_PAD")
      (footprint "eagle-import:1X01")
      (libsource (lib "eagle-import") (part "ONE_PAD"))
    )
    (comp (ref "U$632")
      (value "ONE_PAD")
      (footprint "eagle-import:1X01")
      (libsource (lib "eagle-import") (part "ONE_PAD"))
    )
    (comp (ref "U$633")
      (value "ONE_PAD")
      (footprint "eagle-import:1X01")
      (libsource (lib "eagle-import") (part "ONE_PAD"))
    )
    (comp (ref "U$634")
      (value "ONE_PAD")
      (footprint "eagle-import:1X01")
      (libsource (lib "eagle-import") (part "ONE_PAD"))
    )
    (comp (ref "U$635")
      (value "ONE_PAD")
      (footprint "eagle-import:1X01")
      (libsource (lib "eagle-import") (part "ONE_PAD"))
    )
    (comp (ref "U$636")
      (value "ONE_PAD")
      (footprint "eagle-import:1X01")
      (libsource (lib "eagle-import") (part "ONE_PAD"))
    )
    (comp (ref "U$637")
      (value "ONE_PAD")
      (footprint "eagle-import:1X01")
      (libsource (lib "eagle-import") (part "ONE_PAD"))
    )
    (comp (ref "U$638")
      (value "ONE_PAD")
      (footprint "eagle-import:1X01")
      (libsource (lib "eagle-import") (part "ONE_PAD"))
    )
    (comp (ref "U$639")
      (value "ONE_PAD")
      (footprint "eagle-import:1X01")
      (libsource (lib "eagle-import") (part "ONE_PAD"))
    )
    (comp (ref "U$640")
      (value "ONE_PAD")
      (footprint "eagle-import:1X01")
      (libsource (lib "eagle-import") (part "ONE_PAD"))
    )
    (comp (ref "U$641")
      (value "ONE_PAD")
      (footprint "eagle-import:1X01")
      (libsource (lib "eagle-import") (part "ONE_PAD"))
    )
    (comp (ref "U$642")
      (value "ONE_PAD")
      (footprint "eagle-import:1X01")
      (libsource (lib "eagle-import") (part "ONE_PAD"))
    )
    (comp (ref "U$643")
      (value "ONE_PAD")
      (footprint "eagle-import:1X01")
      (libsource (lib "eagle-import") (part "ONE_PAD"))
    )
    (comp (ref "U$644")
      (value "ONE_PAD")
      (footprint "eagle-import:1X01")
      (libsource (lib "eagle-import") (part "ONE_PAD"))
    )
    (comp (ref "U$645")
      (value "ONE_PAD")
      (footprint "eagle-import:1X01")
      (libsource (lib "eagle-import") (part "ONE_PAD"))
    )
    (comp (ref "U$646")
      (value "ONE_PAD")
      (footprint "eagle-import:1X01")
      (libsource (lib "eagle-import") (part "ONE_PAD"))
    )
    (comp (ref "U$647")
      (value "ONE_PAD")
      (footprint "eagle-import:1X01")
      (libsource (lib "eagle-import") (part "ONE_PAD"))
    )
    (comp (ref "U$648")
      (value "ONE_PAD")
      (footprint "eagle-import:1X01")
      (libsource (lib "eagle-import") (part "ONE_PAD"))
    )
    (comp (ref "U$649")
      (value "ONE_PAD")
      (footprint "eagle-import:1X01")
      (libsource (lib "eagle-import") (part "ONE_PAD"))
    )
    (comp (ref "U$650")
      (value "ONE_PAD")
      (footprint "eagle-import:1X01")
      (libsource (lib "eagle-import") (part "ONE_PAD"))
    )
    (comp (ref "U$651")
      (value "ONE_PAD")
      (footprint "eagle-import:1X01")
      (libsource (lib "eagle-import") (part "ONE_PAD"))
    )
    (comp (ref "U$652")
      (value "ONE_PAD")
      (footprint "eagle-import:1X01")
      (libsource (lib "eagle-import") (part "ONE_PAD"))
    )
    (comp (ref "U$653")
      (value "ONE_PAD")
      (footprint "eagle-import:1X01")
      (libsource (lib "eagle-import") (part "ONE_PAD"))
    )
    (comp (ref "U$654")
      (value "ONE_PAD")
      (footprint "eagle-import:1X01")
      (libsource (lib "eagle-import") (part "ONE_PAD"))
    )
    (comp (ref "U$655")
      (value "ONE_PAD")
      (footprint "eagle-import:1X01")
      (libsource (lib "eagle-import") (part "ONE_PAD"))
    )
    (comp (ref "U$656")
      (value "ONE_PAD")
      (footprint "eagle-import:1X01")
      (libsource (lib "eagle-import") (part "ONE_PAD"))
    )
    (comp (ref "U$657")
      (value "ONE_PAD")
      (footprint "eagle-import:1X01")
      (libsource (lib "eagle-import") (part "ONE_PAD"))
    )
    (comp (ref "U$658")
      (value "ONE_PAD")
      (footprint "eagle-import:1X01")
      (libsource (lib "eagle-import") (part "ONE_PAD"))
    )
    (comp (ref "U$659")
      (value "ONE_PAD")
      (footprint "eagle-import:1X01")
      (libsource (lib "eagle-import") (part "ONE_PAD"))
    )
    (comp (ref "U$660")
      (value "ONE_PAD")
      (footprint "eagle-import:1X01")
      (libsource (lib "eagle-import") (part "ONE_PAD"))
    )
    (comp (ref "U$661")
      (value "ONE_PAD")
      (footprint "eagle-import:1X01")
      (libsource (lib "eagle-import") (part "ONE_PAD"))
    )
    (comp (ref "U$662")
      (value "ONE_PAD")
      (footprint "eagle-import:1X01")
      (libsource (lib "eagle-import") (part "ONE_PAD"))
    )
    (comp (ref "U$663")
      (value "ONE_PAD")
      (footprint "eagle-import:1X01")
      (libsource (lib "eagle-import") (part "ONE_PAD"))
    )
    (comp (ref "U$664")
      (value "ONE_PAD")
      (footprint "eagle-import:1X01")
      (libsource (lib "eagle-import") (part "ONE_PAD"))
    )
    (comp (ref "U$665")
      (value "ONE_PAD")
      (footprint "eagle-import:1X01")
      (libsource (lib "eagle-import") (part "ONE_PAD"))
    )
    (comp (ref "U$666")
      (value "ONE_PAD")
      (footprint "eagle-import:1X01")
      (libsource (lib "eagle-import") (part "ONE_PAD"))
    )
    (comp (ref "U$667")
      (value "ONE_PAD")
      (footprint "eagle-import:1X01")
      (libsource (lib "eagle-import") (part "ONE_PAD"))
    )
    (comp (ref "U$668")
      (value "ONE_PAD")
      (footprint "eagle-import:1X01")
      (libsource (lib "eagle-import") (part "ONE_PAD"))
    )
    (comp (ref "U$669")
      (value "ONE_PAD")
      (footprint "eagle-import:1X01")
      (libsource (lib "eagle-import") (part "ONE_PAD"))
    )
    (comp (ref "U$670")
      (value "ONE_PAD")
      (footprint "eagle-import:1X01")
      (libsource (lib "eagle-import") (part "ONE_PAD"))
    )
    (comp (ref "U$671")
      (value "ONE_PAD")
      (footprint "eagle-import:1X01")
      (libsource (lib "eagle-import") (part "ONE_PAD"))
    )
    (comp (ref "U$672")
      (value "ONE_PAD")
      (footprint "eagle-import:1X01")
      (libsource (lib "eagle-import") (part "ONE_PAD"))
    )
    (comp (ref "U$673")
      (value "ONE_PAD")
      (footprint "eagle-import:1X01")
      (libsource (lib "eagle-import") (part "ONE_PAD"))
    )
    (comp (ref "U$674")
      (value "ONE_PAD")
      (footprint "eagle-import:1X01")
      (libsource (lib "eagle-import") (part "ONE_PAD"))
    )
    (comp (ref "U$675")
      (value "ONE_PAD")
      (footprint "eagle-import:1X01")
      (libsource (lib "eagle-import") (part "ONE_PAD"))
    )
    (comp (ref "U$676")
      (value "ONE_PAD")
      (footprint "eagle-import:1X01")
      (libsource (lib "eagle-import") (part "ONE_PAD"))
    )
    (comp (ref "U$677")
      (value "ONE_PAD")
      (footprint "eagle-import:1X01")
      (libsource (lib "eagle-import") (part "ONE_PAD"))
    )
    (comp (ref "U$678")
      (value "ONE_PAD")
      (footprint "eagle-import:1X01")
      (libsource (lib "eagle-import") (part "ONE_PAD"))
    )
    (comp (ref "U$679")
      (value "ONE_PAD")
      (footprint "eagle-import:1X01")
      (libsource (lib "eagle-import") (part "ONE_PAD"))
    )
    (comp (ref "U$680")
      (value "ONE_PAD")
      (footprint "eagle-import:1X01")
      (libsource (lib "eagle-import") (part "ONE_PAD"))
    )
    (comp (ref "U$681")
      (value "GND")
      (footprint "eagle-import:1X01")
      (libsource (lib "eagle-import") (part "ONE_PAD"))
    )
    (comp (ref "U$682")
      (value "VCC")
      (footprint "eagle-import:1X01")
      (libsource (lib "eagle-import") (part "ONE_PAD"))
    )
    (comp (ref "U$683")
      (value "SDA")
      (footprint "eagle-import:1X01")
      (libsource (lib "eagle-import") (part "ONE_PAD"))
    )
    (comp (ref "U$684")
      (value "SCL")
      (footprint "eagle-import:1X01")
      (libsource (lib "eagle-import") (part "ONE_PAD"))
    )
    (comp (ref "U$685")
      (value "ONE_PAD")
      (footprint "eagle-import:1X01")
      (libsource (lib "eagle-import") (part "ONE_PAD"))
    )
    (comp (ref "U$686")
      (value "ONE_PAD")
      (footprint "eagle-import:1X01")
      (libsource (lib "eagle-import") (part "ONE_PAD"))
    )
    (comp (ref "U$687")
      (value "ONE_PAD")
      (footprint "eagle-import:1X01")
      (libsource (lib "eagle-import") (part "ONE_PAD"))
    )
    (comp (ref "U$688")
      (value "ONE_PAD")
      (footprint "eagle-import:1X01")
      (libsource (lib "eagle-import") (part "ONE_PAD"))
    )
    (comp (ref "U$689")
      (value "ONE_PAD")
      (footprint "eagle-import:1X01")
      (libsource (lib "eagle-import") (part "ONE_PAD"))
    )
    (comp (ref "U$690")
      (value "ONE_PAD")
      (footprint "eagle-import:1X01")
      (libsource (lib "eagle-import") (part "ONE_PAD"))
    )
    (comp (ref "U$691")
      (value "ONE_PAD")
      (footprint "eagle-import:1X01")
      (libsource (lib "eagle-import") (part "ONE_PAD"))
    )
    (comp (ref "U$692")
      (value "ONE_PAD")
      (footprint "eagle-import:1X01")
      (libsource (lib "eagle-import") (part "ONE_PAD"))
    )
    (comp (ref "U$693")
      (value "ONE_PAD")
      (footprint "eagle-import:1X01")
      (libsource (lib "eagle-import") (part "ONE_PAD"))
    )
    (comp (ref "U$694")
      (value "ONE_PAD")
      (footprint "eagle-import:1X01")
      (libsource (lib "eagle-import") (part "ONE_PAD"))
    )
    (comp (ref "U$695")
      (value "ONE_PAD")
      (footprint "eagle-import:1X01")
      (libsource (lib "eagle-import") (part "ONE_PAD"))
    )
    (comp (ref "U$696")
      (value "ONE_PAD")
      (footprint "eagle-import:1X01")
      (libsource (lib "eagle-import") (part "ONE_PAD"))
    )
    (comp (ref "U$697")
      (value "ONE_PAD")
      (footprint "eagle-import:1X01")
      (libsource (lib "eagle-import") (part "ONE_PAD"))
    )
    (comp (ref "U$698")
      (value "ONE_PAD")
      (footprint "eagle-import:1X01")
      (libsource (lib "eagle-import") (part "ONE_PAD"))
    )
    (comp (ref "U$699")
      (value "ONE_PAD")
      (footprint "eagle-import:1X01")
      (libsource (lib "eagle-import") (part "ONE_PAD"))
    )
    (comp (ref "U$700")
      (value "ONE_PAD")
      (footprint "eagle-import:1X01")
      (libsource (lib "eagle-import") (part "ONE_PAD"))
    )
    (comp (ref "U$701")
      (value "ONE_PAD")
      (footprint "eagle-import:1X01")
      (libsource (lib "eagle-import") (part "ONE_PAD"))
    )
    (comp (ref "U$702")
      (value "ONE_PAD")
      (footprint "eagle-import:1X01")
      (libsource (lib "eagle-import") (part "ONE_PAD"))
    )
    (comp (ref "U$703")
      (value "ONE_PAD")
      (footprint "eagle-import:1X01")
      (libsource (lib "eagle-import") (part "ONE_PAD"))
    )
    (comp (ref "U$704")
      (value "ONE_PAD")
      (footprint "eagle-import:1X01")
      (libsource (lib "eagle-import") (part "ONE_PAD"))
    )
    (comp (ref "U$705")
      (value "ONE_PAD")
      (footprint "eagle-import:1X01")
      (libsource (lib "eagle-import") (part "ONE_PAD"))
    )
    (comp (ref "U$706")
      (value "ONE_PAD")
      (footprint "eagle-import:1X01")
      (libsource (lib "eagle-import") (part "ONE_PAD"))
    )
    (comp (ref "U$707")
      (value "ONE_PAD")
      (footprint "eagle-import:1X01")
      (libsource (lib "eagle-import") (part "ONE_PAD"))
    )
    (comp (ref "U$708")
      (value "ONE_PAD")
      (footprint "eagle-import:1X01")
      (libsource (lib "eagle-import") (part "ONE_PAD"))
    )
    (comp (ref "U$709")
      (value "ONE_PAD")
      (footprint "eagle-import:1X01")
      (libsource (lib "eagle-import") (part "ONE_PAD"))
    )
    (comp (ref "U$710")
      (value "ONE_PAD")
      (footprint "eagle-import:1X01")
      (libsource (lib "eagle-import") (part "ONE_PAD"))
    )
    (comp (ref "U$711")
      (value "ONE_PAD")
      (footprint "eagle-import:1X01")
      (libsource (lib "eagle-import") (part "ONE_PAD"))
    )
    (comp (ref "U$712")
      (value "ONE_PAD")
      (footprint "eagle-import:1X01")
      (libsource (lib "eagle-import") (part "ONE_PAD"))
    )
    (comp (ref "U$713")
      (value "ONE_PAD")
      (footprint "eagle-import:1X01")
      (libsource (lib "eagle-import") (part "ONE_PAD"))
    )
    (comp (ref "U$714")
      (value "ONE_PAD")
      (footprint "eagle-import:1X01")
      (libsource (lib "eagle-import") (part "ONE_PAD"))
    )
    (comp (ref "U$715")
      (value "ONE_PAD")
      (footprint "eagle-import:1X01")
      (libsource (lib "eagle-import") (part "ONE_PAD"))
    )
    (comp (ref "U$716")
      (value "ONE_PAD")
      (footprint "eagle-import:1X01")
      (libsource (lib "eagle-import") (part "ONE_PAD"))
    )
    (comp (ref "U$717")
      (value "ONE_PAD")
      (footprint "eagle-import:1X01")
      (libsource (lib "eagle-import") (part "ONE_PAD"))
    )
    (comp (ref "U$718")
      (value "ONE_PAD")
      (footprint "eagle-import:1X01")
      (libsource (lib "eagle-import") (part "ONE_PAD"))
    )
    (comp (ref "U$719")
      (value "ONE_PAD")
      (footprint "eagle-import:1X01")
      (libsource (lib "eagle-import") (part "ONE_PAD"))
    )
    (comp (ref "U$720")
      (value "ONE_PAD")
      (footprint "eagle-import:1X01")
      (libsource (lib "eagle-import") (part "ONE_PAD"))
    )
    (comp (ref "U$721")
      (value "ONE_PAD")
      (footprint "eagle-import:1X01")
      (libsource (lib "eagle-import") (part "ONE_PAD"))
    )
    (comp (ref "U$722")
      (value "ONE_PAD")
      (footprint "eagle-import:1X01")
      (libsource (lib "eagle-import") (part "ONE_PAD"))
    )
    (comp (ref "U$723")
      (value "ONE_PAD")
      (footprint "eagle-import:1X01")
      (libsource (lib "eagle-import") (part "ONE_PAD"))
    )
    (comp (ref "U$724")
      (value "ONE_PAD")
      (footprint "eagle-import:1X01")
      (libsource (lib "eagle-import") (part "ONE_PAD"))
    )
    (comp (ref "U$725")
      (value "ONE_PAD")
      (footprint "eagle-import:1X01")
      (libsource (lib "eagle-import") (part "ONE_PAD"))
    )
    (comp (ref "U$726")
      (value "ONE_PAD")
      (footprint "eagle-import:1X01")
      (libsource (lib "eagle-import") (part "ONE_PAD"))
    )
    (comp (ref "U$727")
      (value "ONE_PAD")
      (footprint "eagle-import:1X01")
      (libsource (lib "eagle-import") (part "ONE_PAD"))
    )
    (comp (ref "U$728")
      (value "ONE_PAD")
      (footprint "eagle-import:1X01")
      (libsource (lib "eagle-import") (part "ONE_PAD"))
    )
    (comp (ref "U$729")
      (value "ONE_PAD")
      (footprint "eagle-import:1X01")
      (libsource (lib "eagle-import") (part "ONE_PAD"))
    )
    (comp (ref "U$730")
      (value "ONE_PAD")
      (footprint "eagle-import:1X01")
      (libsource (lib "eagle-import") (part "ONE_PAD"))
    )
    (comp (ref "U$731")
      (value "ONE_PAD")
      (footprint "eagle-import:1X01")
      (libsource (lib "eagle-import") (part "ONE_PAD"))
    )
    (comp (ref "U$732")
      (value "ONE_PAD")
      (footprint "eagle-import:1X01")
      (libsource (lib "eagle-import") (part "ONE_PAD"))
    )
    (comp (ref "VCC")
      (value "10X-PADS")
      (footprint "eagle-import:10X-PADS")
      (libsource (lib "eagle-import") (part "10X-PADS"))
    )
    (comp (ref "VCC1")
      (value "10X-PADS")
      (footprint "eagle-import:10X-PADS")
      (libsource (lib "eagle-import") (part "10X-PADS"))
    )
    (comp (ref "VCC2")
      (value "10X-PADS")
      (footprint "eagle-import:10X-PADS")
      (libsource (lib "eagle-import") (part "10X-PADS"))
    )
    (comp (ref "VCC3")
      (value "10X-PADS")
      (footprint "eagle-import:10X-PADS")
      (libsource (lib "eagle-import") (part "10X-PADS"))
    )
    (comp (ref "VCC4")
      (value "10X-PADS")
      (footprint "eagle-import:10X-PADS")
      (libsource (lib "eagle-import") (part "10X-PADS"))
    )
    (comp (ref "VCC5")
      (value "10X-PADS")
      (footprint "eagle-import:10X-PADS")
      (libsource (lib "eagle-import") (part "10X-PADS"))
    )
  )
  (nets
    (net (code "1") (name "/GND") (class "Default")
      (node (ref "C1") (pin "1") (pinfunction "1_1") (pintype "passive"))
      (node (ref "C2") (pin "1") (pinfunction "1_1") (pintype "passive"))
      (node (ref "C3") (pin "1") (pinfunction "1_1") (pintype "passive"))
      (node (ref "C4") (pin "1") (pinfunction "1_1") (pintype "passive"))
      (node (ref "C5") (pin "1") (pinfunction "1_1") (pintype "passive"))
      (node (ref "C6") (pin "1") (pinfunction "1_1") (pintype "passive"))
      (node (ref "GND") (pin "P$1") (pinfunction "P$1_P$1") (pintype "bidirectional"))
      (node (ref "GND") (pin "P$10") (pinfunction "P$10_P$10") (pintype "bidirectional"))
      (node (ref "GND") (pin "P$2") (pinfunction "P$2_P$2") (pintype "bidirectional"))
      (node (ref "GND") (pin "P$3") (pinfunction "P$3_P$3") (pintype "bidirectional"))
      (node (ref "GND") (pin "P$4") (pinfunction "P$4_P$4") (pintype "bidirectional"))
      (node (ref "GND") (pin "P$5") (pinfunction "P$5_P$5") (pintype "bidirectional"))
      (node (ref "GND") (pin "P$6") (pinfunction "P$6_P$6") (pintype "bidirectional"))
      (node (ref "GND") (pin "P$7") (pinfunction "P$7_P$7") (pintype "bidirectional"))
      (node (ref "GND") (pin "P$8") (pinfunction "P$8_P$8") (pintype "bidirectional"))
      (node (ref "GND") (pin "P$9") (pinfunction "P$9_P$9") (pintype "bidirectional"))
      (node (ref "GND1") (pin "P$1") (pinfunction "P$1_P$1") (pintype "bidirectional"))
      (node (ref "GND1") (pin "P$10") (pinfunction "P$10_P$10") (pintype "bidirectional"))
      (node (ref "GND1") (pin "P$2") (pinfunction "P$2_P$2") (pintype "bidirectional"))
      (node (ref "GND1") (pin "P$3") (pinfunction "P$3_P$3") (pintype "bidirectional"))
      (node (ref "GND1") (pin "P$4") (pinfunction "P$4_P$4") (pintype "bidirectional"))
      (node (ref "GND1") (pin "P$5") (pinfunction "P$5_P$5") (pintype "bidirectional"))
      (node (ref "GND1") (pin "P$6") (pinfunction "P$6_P$6") (pintype "bidirectional"))
      (node (ref "GND1") (pin "P$7") (pinfunction "P$7_P$7") (pintype "bidirectional"))
      (node (ref "GND1") (pin "P$8") (pinfunction "P$8_P$8") (pintype "bidirectional"))
      (node (ref "GND1") (pin "P$9") (pinfunction "P$9_P$9") (pintype "bidirectional"))
      (node (ref "GND2") (pin "P$1") (pinfunction "P$1_P$1") (pintype "bidirectional"))
      (node (ref "GND2") (pin "P$10") (pinfunction "P$10_P$10") (pintype "bidirectional"))
      (node (ref "GND2") (pin "P$2") (pinfunction "P$2_P$2") (pintype "bidirectional"))
      (node (ref "GND2") (pin "P$3") (pinfunction "P$3_P$3") (pintype "bidirectional"))
      (node (ref "GND2") (pin "P$4") (pinfunction "P$4_P$4") (pintype "bidirectional"))
      (node (ref "GND2") (pin "P$5") (pinfunction "P$5_P$5") (pintype "bidirectional"))
      (node (ref "GND2") (pin "P$6") (pinfunction "P$6_P$6") (pintype "bidirectional"))
      (node (ref "GND2") (pin "P$7") (pinfunction "P$7_P$7") (pintype "bidirectional"))
      (node (ref "GND2") (pin "P$8") (pinfunction "P$8_P$8") (pintype "bidirectional"))
      (node (ref "GND2") (pin "P$9") (pinfunction "P$9_P$9") (pintype "bidirectional"))
      (node (ref "GND3") (pin "P$1") (pinfunction "P$1_P$1") (pintype "bidirectional"))
      (node (ref "GND3") (pin "P$10") (pinfunction "P$10_P$10") (pintype "bidirectional"))
      (node (ref "GND3") (pin "P$2") (pinfunction "P$2_P$2") (pintype "bidirectional"))
      (node (ref "GND3") (pin "P$3") (pinfunction "P$3_P$3") (pintype "bidirectional"))
      (node (ref "GND3") (pin "P$4") (pinfunction "P$4_P$4") (pintype "bidirectional"))
      (node (ref "GND3") (pin "P$5") (pinfunction "P$5_P$5") (pintype "bidirectional"))
      (node (ref "GND3") (pin "P$6") (pinfunction "P$6_P$6") (pintype "bidirectional"))
      (node (ref "GND3") (pin "P$7") (pinfunction "P$7_P$7") (pintype "bidirectional"))
      (node (ref "GND3") (pin "P$8") (pinfunction "P$8_P$8") (pintype "bidirectional"))
      (node (ref "GND3") (pin "P$9") (pinfunction "P$9_P$9") (pintype "bidirectional"))
      (node (ref "GND4") (pin "P$1") (pinfunction "P$1_P$1") (pintype "bidirectional"))
      (node (ref "GND4") (pin "P$10") (pinfunction "P$10_P$10") (pintype "bidirectional"))
      (node (ref "GND4") (pin "P$2") (pinfunction "P$2_P$2") (pintype "bidirectional"))
      (node (ref "GND4") (pin "P$3") (pinfunction "P$3_P$3") (pintype "bidirectional"))
      (node (ref "GND4") (pin "P$4") (pinfunction "P$4_P$4") (pintype "bidirectional"))
      (node (ref "GND4") (pin "P$5") (pinfunction "P$5_P$5") (pintype "bidirectional"))
      (node (ref "GND4") (pin "P$6") (pinfunction "P$6_P$6") (pintype "bidirectional"))
      (node (ref "GND4") (pin "P$7") (pinfunction "P$7_P$7") (pintype "bidirectional"))
      (node (ref "GND4") (pin "P$8") (pinfunction "P$8_P$8") (pintype "bidirectional"))
      (node (ref "GND4") (pin "P$9") (pinfunction "P$9_P$9") (pintype "bidirectional"))
      (node (ref "GND5") (pin "P$1") (pinfunction "P$1_P$1") (pintype "bidirectional"))
      (node (ref "GND5") (pin "P$10") (pinfunction "P$10_P$10") (pintype "bidirectional"))
      (node (ref "GND5") (pin "P$2") (pinfunction "P$2_P$2") (pintype "bidirectional"))
      (node (ref "GND5") (pin "P$3") (pinfunction "P$3_P$3") (pintype "bidirectional"))
      (node (ref "GND5") (pin "P$4") (pinfunction "P$4_P$4") (pintype "bidirectional"))
      (node (ref "GND5") (pin "P$5") (pinfunction "P$5_P$5") (pintype "bidirectional"))
      (node (ref "GND5") (pin "P$6") (pinfunction "P$6_P$6") (pintype "bidirectional"))
      (node (ref "GND5") (pin "P$7") (pinfunction "P$7_P$7") (pintype "bidirectional"))
      (node (ref "GND5") (pin "P$8") (pinfunction "P$8_P$8") (pintype "bidirectional"))
      (node (ref "GND5") (pin "P$9") (pinfunction "P$9_P$9") (pintype "bidirectional"))
      (node (ref "HELLO") (pin "NEG") (pinfunction "NEG_NEG") (pintype "passive"))
      (node (ref "HELLO1") (pin "NEG") (pinfunction "NEG_NEG") (pintype "passive"))
      (node (ref "HELLO2") (pin "NEG") (pinfunction "NEG_NEG") (pintype "passive"))
      (node (ref "HELLO3") (pin "NEG") (pinfunction "NEG_NEG") (pintype "passive"))
      (node (ref "HELLO4") (pin "NEG") (pinfunction "NEG_NEG") (pintype "passive"))
      (node (ref "HELLO5") (pin "NEG") (pinfunction "NEG_NEG") (pintype "passive"))
      (node (ref "IC1") (pin "GND") (pinfunction "GND_GND") (pintype "bidirectional"))
      (node (ref "IC2") (pin "GND") (pinfunction "GND_GND") (pintype "bidirectional"))
      (node (ref "IC3") (pin "GND") (pinfunction "GND_GND") (pintype "bidirectional"))
      (node (ref "IC4") (pin "GND") (pinfunction "GND_GND") (pintype "bidirectional"))
      (node (ref "IC5") (pin "GND") (pinfunction "GND_GND") (pintype "bidirectional"))
      (node (ref "IC6") (pin "GND") (pinfunction "GND_GND") (pintype "bidirectional"))
      (node (ref "J1") (pin "GND") (pinfunction "GND_GND") (pintype "bidirectional"))
      (node (ref "J2") (pin "GND") (pinfunction "GND_GND") (pintype "bidirectional"))
      (node (ref "J3") (pin "GND") (pinfunction "GND_GND") (pintype "bidirectional"))
      (node (ref "J4") (pin "GND") (pinfunction "GND_GND") (pintype "bidirectional"))
      (node (ref "J5") (pin "GND") (pinfunction "GND_GND") (pintype "bidirectional"))
      (node (ref "J6") (pin "GND") (pinfunction "GND_GND") (pintype "bidirectional"))
      (node (ref "POWER") (pin "NEG") (pinfunction "NEG_NEG") (pintype "passive"))
      (node (ref "POWER1") (pin "NEG") (pinfunction "NEG_NEG") (pintype "passive"))
      (node (ref "POWER2") (pin "NEG") (pinfunction "NEG_NEG") (pintype "passive"))
      (node (ref "POWER3") (pin "NEG") (pinfunction "NEG_NEG") (pintype "passive"))
      (node (ref "POWER4") (pin "NEG") (pinfunction "NEG_NEG") (pintype "passive"))
      (node (ref "POWER5") (pin "NEG") (pinfunction "NEG_NEG") (pintype "passive"))
      (node (ref "U$193") (pin "1") (pinfunction "P_1") (pintype "passive"))
      (node (ref "U$315") (pin "1") (pinfunction "P_1") (pintype "passive"))
      (node (ref "U$437") (pin "1") (pinfunction "P_1") (pintype "passive"))
      (node (ref "U$559") (pin "1") (pinfunction "P_1") (pintype "passive"))
      (node (ref "U$681") (pin "1") (pinfunction "P_1") (pintype "passive"))
      (node (ref "U$71") (pin "1") (pinfunction "P_1") (pintype "passive"))
    )
    (net (code "2") (name "/PB0") (class "Default")
      (node (ref "IC1") (pin "PB0") (pinfunction "PB0_PB0") (pintype "bidirectional"))
      (node (ref "IC2") (pin "PB0") (pinfunction "PB0_PB0") (pintype "bidirectional"))
      (node (ref "IC3") (pin "PB0") (pinfunction "PB0_PB0") (pintype "bidirectional"))
      (node (ref "IC4") (pin "PB0") (pinfunction "PB0_PB0") (pintype "bidirectional"))
      (node (ref "IC5") (pin "PB0") (pinfunction "PB0_PB0") (pintype "bidirectional"))
      (node (ref "IC6") (pin "PB0") (pinfunction "PB0_PB0") (pintype "bidirectional"))
      (node (ref "J1") (pin "0/MOSI/SDA") (pinfunction "PB0/MOSI/SDA_0/MOSI/SDA") (pintype "bidirectional"))
      (node (ref "J2") (pin "0/MOSI/SDA") (pinfunction "PB0/MOSI/SDA_0/MOSI/SDA") (pintype "bidirectional"))
      (node (ref "J3") (pin "0/MOSI/SDA") (pinfunction "PB0/MOSI/SDA_0/MOSI/SDA") (pintype "bidirectional"))
      (node (ref "J4") (pin "0/MOSI/SDA") (pinfunction "PB0/MOSI/SDA_0/MOSI/SDA") (pintype "bidirectional"))
      (node (ref "J5") (pin "0/MOSI/SDA") (pinfunction "PB0/MOSI/SDA_0/MOSI/SDA") (pintype "bidirectional"))
      (node (ref "J6") (pin "0/MOSI/SDA") (pinfunction "PB0/MOSI/SDA_0/MOSI/SDA") (pintype "bidirectional"))
      (node (ref "R10") (pin "P$2") (pinfunction "2_P$2") (pintype "passive"))
      (node (ref "R12") (pin "P$2") (pinfunction "2_P$2") (pintype "passive"))
      (node (ref "R2") (pin "P$2") (pinfunction "2_P$2") (pintype "passive"))
      (node (ref "R4") (pin "P$2") (pinfunction "2_P$2") (pintype "passive"))
      (node (ref "R6") (pin "P$2") (pinfunction "2_P$2") (pintype "passive"))
      (node (ref "R8") (pin "P$2") (pinfunction "2_P$2") (pintype "passive"))
      (node (ref "U$195") (pin "1") (pinfunction "P_1") (pintype "passive"))
      (node (ref "U$197") (pin "1") (pinfunction "P_1") (pintype "passive"))
      (node (ref "U$198") (pin "1") (pinfunction "P_1") (pintype "passive"))
      (node (ref "U$199") (pin "1") (pinfunction "P_1") (pintype "passive"))
      (node (ref "U$317") (pin "1") (pinfunction "P_1") (pintype "passive"))
      (node (ref "U$319") (pin "1") (pinfunction "P_1") (pintype "passive"))
      (node (ref "U$320") (pin "1") (pinfunction "P_1") (pintype "passive"))
      (node (ref "U$321") (pin "1") (pinfunction "P_1") (pintype "passive"))
      (node (ref "U$439") (pin "1") (pinfunction "P_1") (pintype "passive"))
      (node (ref "U$441") (pin "1") (pinfunction "P_1") (pintype "passive"))
      (node (ref "U$442") (pin "1") (pinfunction "P_1") (pintype "passive"))
      (node (ref "U$443") (pin "1") (pinfunction "P_1") (pintype "passive"))
      (node (ref "U$561") (pin "1") (pinfunction "P_1") (pintype "passive"))
      (node (ref "U$563") (pin "1") (pinfunction "P_1") (pintype "passive"))
      (node (ref "U$564") (pin "1") (pinfunction "P_1") (pintype "passive"))
      (node (ref "U$565") (pin "1") (pinfunction "P_1") (pintype "passive"))
      (node (ref "U$683") (pin "1") (pinfunction "P_1") (pintype "passive"))
      (node (ref "U$685") (pin "1") (pinfunction "P_1") (pintype "passive"))
      (node (ref "U$686") (pin "1") (pinfunction "P_1") (pintype "passive"))
      (node (ref "U$687") (pin "1") (pinfunction "P_1") (pintype "passive"))
      (node (ref "U$72") (pin "1") (pinfunction "P_1") (pintype "passive"))
      (node (ref "U$75") (pin "1") (pinfunction "P_1") (pintype "passive"))
      (node (ref "U$76") (pin "1") (pinfunction "P_1") (pintype "passive"))
      (node (ref "U$77") (pin "1") (pinfunction "P_1") (pintype "passive"))
    )
    (net (code "3") (name "/PB1") (class "Default")
      (node (ref "IC1") (pin "PB1") (pinfunction "PB1_PB1") (pintype "bidirectional"))
      (node (ref "IC2") (pin "PB1") (pinfunction "PB1_PB1") (pintype "bidirectional"))
      (node (ref "IC3") (pin "PB1") (pinfunction "PB1_PB1") (pintype "bidirectional"))
      (node (ref "IC4") (pin "PB1") (pinfunction "PB1_PB1") (pintype "bidirectional"))
      (node (ref "IC5") (pin "PB1") (pinfunction "PB1_PB1") (pintype "bidirectional"))
      (node (ref "IC6") (pin "PB1") (pinfunction "PB1_PB1") (pintype "bidirectional"))
      (node (ref "J1") (pin "1/MISO") (pinfunction "PB1/MISO_1/MISO") (pintype "bidirectional"))
      (node (ref "J2") (pin "1/MISO") (pinfunction "PB1/MISO_1/MISO") (pintype "bidirectional"))
      (node (ref "J3") (pin "1/MISO") (pinfunction "PB1/MISO_1/MISO") (pintype "bidirectional"))
      (node (ref "J4") (pin "1/MISO") (pinfunction "PB1/MISO_1/MISO") (pintype "bidirectional"))
      (node (ref "J5") (pin "1/MISO") (pinfunction "PB1/MISO_1/MISO") (pintype "bidirectional"))
      (node (ref "J6") (pin "1/MISO") (pinfunction "PB1/MISO_1/MISO") (pintype "bidirectional"))
      (node (ref "U$200") (pin "1") (pinfunction "P_1") (pintype "passive"))
      (node (ref "U$201") (pin "1") (pinfunction "P_1") (pintype "passive"))
      (node (ref "U$202") (pin "1") (pinfunction "P_1") (pintype "passive"))
      (node (ref "U$322") (pin "1") (pinfunction "P_1") (pintype "passive"))
      (node (ref "U$323") (pin "1") (pinfunction "P_1") (pintype "passive"))
      (node (ref "U$324") (pin "1") (pinfunction "P_1") (pintype "passive"))
      (node (ref "U$444") (pin "1") (pinfunction "P_1") (pintype "passive"))
      (node (ref "U$445") (pin "1") (pinfunction "P_1") (pintype "passive"))
      (node (ref "U$446") (pin "1") (pinfunction "P_1") (pintype "passive"))
      (node (ref "U$566") (pin "1") (pinfunction "P_1") (pintype "passive"))
      (node (ref "U$567") (pin "1") (pinfunction "P_1") (pintype "passive"))
      (node (ref "U$568") (pin "1") (pinfunction "P_1") (pintype "passive"))
      (node (ref "U$688") (pin "1") (pinfunction "P_1") (pintype "passive"))
      (node (ref "U$689") (pin "1") (pinfunction "P_1") (pintype "passive"))
      (node (ref "U$690") (pin "1") (pinfunction "P_1") (pintype "passive"))
      (node (ref "U$78") (pin "1") (pinfunction "P_1") (pintype "passive"))
      (node (ref "U$79") (pin "1") (pinfunction "P_1") (pintype "passive"))
      (node (ref "U$80") (pin "1") (pinfunction "P_1") (pintype "passive"))
    )
    (net (code "4") (name "/PB2") (class "Default")
      (node (ref "IC1") (pin "PB2") (pinfunction "PB2_PB2") (pintype "bidirectional"))
      (node (ref "IC2") (pin "PB2") (pinfunction "PB2_PB2") (pintype "bidirectional"))
      (node (ref "IC3") (pin "PB2") (pinfunction "PB2_PB2") (pintype "bidirectional"))
      (node (ref "IC4") (pin "PB2") (pinfunction "PB2_PB2") (pintype "bidirectional"))
      (node (ref "IC5") (pin "PB2") (pinfunction "PB2_PB2") (pintype "bidirectional"))
      (node (ref "IC6") (pin "PB2") (pinfunction "PB2_PB2") (pintype "bidirectional"))
      (node (ref "J1") (pin "2/SCK/SCL") (pinfunction "PB2/SCK/SCL_2/SCK/SCL") (pintype "bidirectional"))
      (node (ref "J2") (pin "2/SCK/SCL") (pinfunction "PB2/SCK/SCL_2/SCK/SCL") (pintype "bidirectional"))
      (node (ref "J3") (pin "2/SCK/SCL") (pinfunction "PB2/SCK/SCL_2/SCK/SCL") (pintype "bidirectional"))
      (node (ref "J4") (pin "2/SCK/SCL") (pinfunction "PB2/SCK/SCL_2/SCK/SCL") (pintype "bidirectional"))
      (node (ref "J5") (pin "2/SCK/SCL") (pinfunction "PB2/SCK/SCL_2/SCK/SCL") (pintype "bidirectional"))
      (node (ref "J6") (pin "2/SCK/SCL") (pinfunction "PB2/SCK/SCL_2/SCK/SCL") (pintype "bidirectional"))
      (node (ref "U$196") (pin "1") (pinfunction "P_1") (pintype "passive"))
      (node (ref "U$203") (pin "1") (pinfunction "P_1") (pintype "passive"))
      (node (ref "U$204") (pin "1") (pinfunction "P_1") (pintype "passive"))
      (node (ref "U$205") (pin "1") (pinfunction "P_1") (pintype "passive"))
      (node (ref "U$318") (pin "1") (pinfunction "P_1") (pintype "passive"))
      (node (ref "U$325") (pin "1") (pinfunction "P_1") (pintype "passive"))
      (node (ref "U$326") (pin "1") (pinfunction "P_1") (pintype "passive"))
      (node (ref "U$327") (pin "1") (pinfunction "P_1") (pintype "passive"))
      (node (ref "U$440") (pin "1") (pinfunction "P_1") (pintype "passive"))
      (node (ref "U$447") (pin "1") (pinfunction "P_1") (pintype "passive"))
      (node (ref "U$448") (pin "1") (pinfunction "P_1") (pintype "passive"))
      (node (ref "U$449") (pin "1") (pinfunction "P_1") (pintype "passive"))
      (node (ref "U$562") (pin "1") (pinfunction "P_1") (pintype "passive"))
      (node (ref "U$569") (pin "1") (pinfunction "P_1") (pintype "passive"))
      (node (ref "U$570") (pin "1") (pinfunction "P_1") (pintype "passive"))
      (node (ref "U$571") (pin "1") (pinfunction "P_1") (pintype "passive"))
      (node (ref "U$684") (pin "1") (pinfunction "P_1") (pintype "passive"))
      (node (ref "U$691") (pin "1") (pinfunction "P_1") (pintype "passive"))
      (node (ref "U$692") (pin "1") (pinfunction "P_1") (pintype "passive"))
      (node (ref "U$693") (pin "1") (pinfunction "P_1") (pintype "passive"))
      (node (ref "U$73") (pin "1") (pinfunction "P_1") (pintype "passive"))
      (node (ref "U$81") (pin "1") (pinfunction "P_1") (pintype "passive"))
      (node (ref "U$82") (pin "1") (pinfunction "P_1") (pintype "passive"))
      (node (ref "U$83") (pin "1") (pinfunction "P_1") (pintype "passive"))
    )
    (net (code "5") (name "/PB3") (class "Default")
      (node (ref "IC1") (pin "PB3") (pinfunction "PB3_PB3") (pintype "bidirectional"))
      (node (ref "IC2") (pin "PB3") (pinfunction "PB3_PB3") (pintype "bidirectional"))
      (node (ref "IC3") (pin "PB3") (pinfunction "PB3_PB3") (pintype "bidirectional"))
      (node (ref "IC4") (pin "PB3") (pinfunction "PB3_PB3") (pintype "bidirectional"))
      (node (ref "IC5") (pin "PB3") (pinfunction "PB3_PB3") (pintype "bidirectional"))
      (node (ref "IC6") (pin "PB3") (pinfunction "PB3_PB3") (pintype "bidirectional"))
      (node (ref "U$206") (pin "1") (pinfunction "P_1") (pintype "passive"))
      (node (ref "U$207") (pin "1") (pinfunction "P_1") (pintype "passive"))
      (node (ref "U$208") (pin "1") (pinfunction "P_1") (pintype "passive"))
      (node (ref "U$328") (pin "1") (pinfunction "P_1") (pintype "passive"))
      (node (ref "U$329") (pin "1") (pinfunction "P_1") (pintype "passive"))
      (node (ref "U$330") (pin "1") (pinfunction "P_1") (pintype "passive"))
      (node (ref "U$450") (pin "1") (pinfunction "P_1") (pintype "passive"))
      (node (ref "U$451") (pin "1") (pinfunction "P_1") (pintype "passive"))
      (node (ref "U$452") (pin "1") (pinfunction "P_1") (pintype "passive"))
      (node (ref "U$572") (pin "1") (pinfunction "P_1") (pintype "passive"))
      (node (ref "U$573") (pin "1") (pinfunction "P_1") (pintype "passive"))
      (node (ref "U$574") (pin "1") (pinfunction "P_1") (pintype "passive"))
      (node (ref "U$694") (pin "1") (pinfunction "P_1") (pintype "passive"))
      (node (ref "U$695") (pin "1") (pinfunction "P_1") (pintype "passive"))
      (node (ref "U$696") (pin "1") (pinfunction "P_1") (pintype "passive"))
      (node (ref "U$84") (pin "1") (pinfunction "P_1") (pintype "passive"))
      (node (ref "U$85") (pin "1") (pinfunction "P_1") (pintype "passive"))
      (node (ref "U$86") (pin "1") (pinfunction "P_1") (pintype "passive"))
    )
    (net (code "6") (name "/PB4") (class "Default")
      (node (ref "IC1") (pin "PB4") (pinfunction "PB4_PB4") (pintype "bidirectional"))
      (node (ref "IC2") (pin "PB4") (pinfunction "PB4_PB4") (pintype "bidirectional"))
      (node (ref "IC3") (pin "PB4") (pinfunction "PB4_PB4") (pintype "bidirectional"))
      (node (ref "IC4") (pin "PB4") (pinfunction "PB4_PB4") (pintype "bidirectional"))
      (node (ref "IC5") (pin "PB4") (pinfunction "PB4_PB4") (pintype "bidirectional"))
      (node (ref "IC6") (pin "PB4") (pinfunction "PB4_PB4") (pintype "bidirectional"))
      (node (ref "U$209") (pin "1") (pinfunction "P_1") (pintype "passive"))
      (node (ref "U$210") (pin "1") (pinfunction "P_1") (pintype "passive"))
      (node (ref "U$211") (pin "1") (pinfunction "P_1") (pintype "passive"))
      (node (ref "U$331") (pin "1") (pinfunction "P_1") (pintype "passive"))
      (node (ref "U$332") (pin "1") (pinfunction "P_1") (pintype "passive"))
      (node (ref "U$333") (pin "1") (pinfunction "P_1") (pintype "passive"))
      (node (ref "U$453") (pin "1") (pinfunction "P_1") (pintype "passive"))
      (node (ref "U$454") (pin "1") (pinfunction "P_1") (pintype "passive"))
      (node (ref "U$455") (pin "1") (pinfunction "P_1") (pintype "passive"))
      (node (ref "U$575") (pin "1") (pinfunction "P_1") (pintype "passive"))
      (node (ref "U$576") (pin "1") (pinfunction "P_1") (pintype "passive"))
      (node (ref "U$577") (pin "1") (pinfunction "P_1") (pintype "passive"))
      (node (ref "U$697") (pin "1") (pinfunction "P_1") (pintype "passive"))
      (node (ref "U$698") (pin "1") (pinfunction "P_1") (pintype "passive"))
      (node (ref "U$699") (pin "1") (pinfunction "P_1") (pintype "passive"))
      (node (ref "U$87") (pin "1") (pinfunction "P_1") (pintype "passive"))
      (node (ref "U$88") (pin "1") (pinfunction "P_1") (pintype "passive"))
      (node (ref "U$89") (pin "1") (pinfunction "P_1") (pintype "passive"))
    )
    (net (code "7") (name "/PB5") (class "Default")
      (node (ref "IC1") (pin "PB5") (pinfunction "PB5_PB5") (pintype "bidirectional"))
      (node (ref "IC2") (pin "PB5") (pinfunction "PB5_PB5") (pintype "bidirectional"))
      (node (ref "IC3") (pin "PB5") (pinfunction "PB5_PB5") (pintype "bidirectional"))
      (node (ref "IC4") (pin "PB5") (pinfunction "PB5_PB5") (pintype "bidirectional"))
      (node (ref "IC5") (pin "PB5") (pinfunction "PB5_PB5") (pintype "bidirectional"))
      (node (ref "IC6") (pin "PB5") (pinfunction "PB5_PB5") (pintype "bidirectional"))
      (node (ref "J1") (pin "5/RST") (pinfunction "PB5/RST_5/RST") (pintype "bidirectional"))
      (node (ref "J2") (pin "5/RST") (pinfunction "PB5/RST_5/RST") (pintype "bidirectional"))
      (node (ref "J3") (pin "5/RST") (pinfunction "PB5/RST_5/RST") (pintype "bidirectional"))
      (node (ref "J4") (pin "5/RST") (pinfunction "PB5/RST_5/RST") (pintype "bidirectional"))
      (node (ref "J5") (pin "5/RST") (pinfunction "PB5/RST_5/RST") (pintype "bidirectional"))
      (node (ref "J6") (pin "5/RST") (pinfunction "PB5/RST_5/RST") (pintype "bidirectional"))
      (node (ref "U$212") (pin "1") (pinfunction "P_1") (pintype "passive"))
      (node (ref "U$213") (pin "1") (pinfunction "P_1") (pintype "passive"))
      (node (ref "U$214") (pin "1") (pinfunction "P_1") (pintype "passive"))
      (node (ref "U$334") (pin "1") (pinfunction "P_1") (pintype "passive"))
      (node (ref "U$335") (pin "1") (pinfunction "P_1") (pintype "passive"))
      (node (ref "U$336") (pin "1") (pinfunction "P_1") (pintype "passive"))
      (node (ref "U$456") (pin "1") (pinfunction "P_1") (pintype "passive"))
      (node (ref "U$457") (pin "1") (pinfunction "P_1") (pintype "passive"))
      (node (ref "U$458") (pin "1") (pinfunction "P_1") (pintype "passive"))
      (node (ref "U$578") (pin "1") (pinfunction "P_1") (pintype "passive"))
      (node (ref "U$579") (pin "1") (pinfunction "P_1") (pintype "passive"))
      (node (ref "U$580") (pin "1") (pinfunction "P_1") (pintype "passive"))
      (node (ref "U$700") (pin "1") (pinfunction "P_1") (pintype "passive"))
      (node (ref "U$701") (pin "1") (pinfunction "P_1") (pintype "passive"))
      (node (ref "U$702") (pin "1") (pinfunction "P_1") (pintype "passive"))
      (node (ref "U$90") (pin "1") (pinfunction "P_1") (pintype "passive"))
      (node (ref "U$91") (pin "1") (pinfunction "P_1") (pintype "passive"))
      (node (ref "U$92") (pin "1") (pinfunction "P_1") (pintype "passive"))
    )
    (net (code "8") (name "/VCC") (class "Default")
      (node (ref "C1") (pin "2") (pinfunction "2_2") (pintype "passive"))
      (node (ref "C2") (pin "2") (pinfunction "2_2") (pintype "passive"))
      (node (ref "C3") (pin "2") (pinfunction "2_2") (pintype "passive"))
      (node (ref "C4") (pin "2") (pinfunction "2_2") (pintype "passive"))
      (node (ref "C5") (pin "2") (pinfunction "2_2") (pintype "passive"))
      (node (ref "C6") (pin "2") (pinfunction "2_2") (pintype "passive"))
      (node (ref "IC1") (pin "VCC") (pinfunction "VCC_VCC") (pintype "bidirectional"))
      (node (ref "IC2") (pin "VCC") (pinfunction "VCC_VCC") (pintype "bidirectional"))
      (node (ref "IC3") (pin "VCC") (pinfunction "VCC_VCC") (pintype "bidirectional"))
      (node (ref "IC4") (pin "VCC") (pinfunction "VCC_VCC") (pintype "bidirectional"))
      (node (ref "IC5") (pin "VCC") (pinfunction "VCC_VCC") (pintype "bidirectional"))
      (node (ref "IC6") (pin "VCC") (pinfunction "VCC_VCC") (pintype "bidirectional"))
      (node (ref "J1") (pin "VCC") (pinfunction "VCC_VCC") (pintype "bidirectional"))
      (node (ref "J2") (pin "VCC") (pinfunction "VCC_VCC") (pintype "bidirectional"))
      (node (ref "J3") (pin "VCC") (pinfunction "VCC_VCC") (pintype "bidirectional"))
      (node (ref "J4") (pin "VCC") (pinfunction "VCC_VCC") (pintype "bidirectional"))
      (node (ref "J5") (pin "VCC") (pinfunction "VCC_VCC") (pintype "bidirectional"))
      (node (ref "J6") (pin "VCC") (pinfunction "VCC_VCC") (pintype "bidirectional"))
      (node (ref "R1") (pin "P$2") (pinfunction "2_P$2") (pintype "passive"))
      (node (ref "R11") (pin "P$2") (pinfunction "2_P$2") (pintype "passive"))
      (node (ref "R3") (pin "P$2") (pinfunction "2_P$2") (pintype "passive"))
      (node (ref "R5") (pin "P$2") (pinfunction "2_P$2") (pintype "passive"))
      (node (ref "R7") (pin "P$2") (pinfunction "2_P$2") (pintype "passive"))
      (node (ref "R9") (pin "P$2") (pinfunction "2_P$2") (pintype "passive"))
      (node (ref "U$194") (pin "1") (pinfunction "P_1") (pintype "passive"))
      (node (ref "U$316") (pin "1") (pinfunction "P_1") (pintype "passive"))
      (node (ref "U$438") (pin "1") (pinfunction "P_1") (pintype "passive"))
      (node (ref "U$560") (pin "1") (pinfunction "P_1") (pintype "passive"))
      (node (ref "U$682") (pin "1") (pinfunction "P_1") (pintype "passive"))
      (node (ref "U$74") (pin "1") (pinfunction "P_1") (pintype "passive"))
      (node (ref "VCC") (pin "P$1") (pinfunction "P$1_P$1") (pintype "bidirectional"))
      (node (ref "VCC") (pin "P$10") (pinfunction "P$10_P$10") (pintype "bidirectional"))
      (node (ref "VCC") (pin "P$2") (pinfunction "P$2_P$2") (pintype "bidirectional"))
      (node (ref "VCC") (pin "P$3") (pinfunction "P$3_P$3") (pintype "bidirectional"))
      (node (ref "VCC") (pin "P$4") (pinfunction "P$4_P$4") (pintype "bidirectional"))
      (node (ref "VCC") (pin "P$5") (pinfunction "P$5_P$5") (pintype "bidirectional"))
      (node (ref "VCC") (pin "P$6") (pinfunction "P$6_P$6") (pintype "bidirectional"))
      (node (ref "VCC") (pin "P$7") (pinfunction "P$7_P$7") (pintype "bidirectional"))
      (node (ref "VCC") (pin "P$8") (pinfunction "P$8_P$8") (pintype "bidirectional"))
      (node (ref "VCC") (pin "P$9") (pinfunction "P$9_P$9") (pintype "bidirectional"))
      (node (ref "VCC1") (pin "P$1") (pinfunction "P$1_P$1") (pintype "bidirectional"))
      (node (ref "VCC1") (pin "P$10") (pinfunction "P$10_P$10") (pintype "bidirectional"))
      (node (ref "VCC1") (pin "P$2") (pinfunction "P$2_P$2") (pintype "bidirectional"))
      (node (ref "VCC1") (pin "P$3") (pinfunction "P$3_P$3") (pintype "bidirectional"))
      (node (ref "VCC1") (pin "P$4") (pinfunction "P$4_P$4") (pintype "bidirectional"))
      (node (ref "VCC1") (pin "P$5") (pinfunction "P$5_P$5") (pintype "bidirectional"))
      (node (ref "VCC1") (pin "P$6") (pinfunction "P$6_P$6") (pintype "bidirectional"))
      (node (ref "VCC1") (pin "P$7") (pinfunction "P$7_P$7") (pintype "bidirectional"))
      (node (ref "VCC1") (pin "P$8") (pinfunction "P$8_P$8") (pintype "bidirectional"))
      (node (ref "VCC1") (pin "P$9") (pinfunction "P$9_P$9") (pintype "bidirectional"))
      (node (ref "VCC2") (pin "P$1") (pinfunction "P$1_P$1") (pintype "bidirectional"))
      (node (ref "VCC2") (pin "P$10") (pinfunction "P$10_P$10") (pintype "bidirectional"))
      (node (ref "VCC2") (pin "P$2") (pinfunction "P$2_P$2") (pintype "bidirectional"))
      (node (ref "VCC2") (pin "P$3") (pinfunction "P$3_P$3") (pintype "bidirectional"))
      (node (ref "VCC2") (pin "P$4") (pinfunction "P$4_P$4") (pintype "bidirectional"))
      (node (ref "VCC2") (pin "P$5") (pinfunction "P$5_P$5") (pintype "bidirectional"))
      (node (ref "VCC2") (pin "P$6") (pinfunction "P$6_P$6") (pintype "bidirectional"))
      (node (ref "VCC2") (pin "P$7") (pinfunction "P$7_P$7") (pintype "bidirectional"))
      (node (ref "VCC2") (pin "P$8") (pinfunction "P$8_P$8") (pintype "bidirectional"))
      (node (ref "VCC2") (pin "P$9") (pinfunction "P$9_P$9") (pintype "bidirectional"))
      (node (ref "VCC3") (pin "P$1") (pinfunction "P$1_P$1") (pintype "bidirectional"))
      (node (ref "VCC3") (pin "P$10") (pinfunction "P$10_P$10") (pintype "bidirectional"))
      (node (ref "VCC3") (pin "P$2") (pinfunction "P$2_P$2") (pintype "bidirectional"))
      (node (ref "VCC3") (pin "P$3") (pinfunction "P$3_P$3") (pintype "bidirectional"))
      (node (ref "VCC3") (pin "P$4") (pinfunction "P$4_P$4") (pintype "bidirectional"))
      (node (ref "VCC3") (pin "P$5") (pinfunction "P$5_P$5") (pintype "bidirectional"))
      (node (ref "VCC3") (pin "P$6") (pinfunction "P$6_P$6") (pintype "bidirectional"))
      (node (ref "VCC3") (pin "P$7") (pinfunction "P$7_P$7") (pintype "bidirectional"))
      (node (ref "VCC3") (pin "P$8") (pinfunction "P$8_P$8") (pintype "bidirectional"))
      (node (ref "VCC3") (pin "P$9") (pinfunction "P$9_P$9") (pintype "bidirectional"))
      (node (ref "VCC4") (pin "P$1") (pinfunction "P$1_P$1") (pintype "bidirectional"))
      (node (ref "VCC4") (pin "P$10") (pinfunction "P$10_P$10") (pintype "bidirectional"))
      (node (ref "VCC4") (pin "P$2") (pinfunction "P$2_P$2") (pintype "bidirectional"))
      (node (ref "VCC4") (pin "P$3") (pinfunction "P$3_P$3") (pintype "bidirectional"))
      (node (ref "VCC4") (pin "P$4") (pinfunction "P$4_P$4") (pintype "bidirectional"))
      (node (ref "VCC4") (pin "P$5") (pinfunction "P$5_P$5") (pintype "bidirectional"))
      (node (ref "VCC4") (pin "P$6") (pinfunction "P$6_P$6") (pintype "bidirectional"))
      (node (ref "VCC4") (pin "P$7") (pinfunction "P$7_P$7") (pintype "bidirectional"))
      (node (ref "VCC4") (pin "P$8") (pinfunction "P$8_P$8") (pintype "bidirectional"))
      (node (ref "VCC4") (pin "P$9") (pinfunction "P$9_P$9") (pintype "bidirectional"))
      (node (ref "VCC5") (pin "P$1") (pinfunction "P$1_P$1") (pintype "bidirectional"))
      (node (ref "VCC5") (pin "P$10") (pinfunction "P$10_P$10") (pintype "bidirectional"))
      (node (ref "VCC5") (pin "P$2") (pinfunction "P$2_P$2") (pintype "bidirectional"))
      (node (ref "VCC5") (pin "P$3") (pinfunction "P$3_P$3") (pintype "bidirectional"))
      (node (ref "VCC5") (pin "P$4") (pinfunction "P$4_P$4") (pintype "bidirectional"))
      (node (ref "VCC5") (pin "P$5") (pinfunction "P$5_P$5") (pintype "bidirectional"))
      (node (ref "VCC5") (pin "P$6") (pinfunction "P$6_P$6") (pintype "bidirectional"))
      (node (ref "VCC5") (pin "P$7") (pinfunction "P$7_P$7") (pintype "bidirectional"))
      (node (ref "VCC5") (pin "P$8") (pinfunction "P$8_P$8") (pintype "bidirectional"))
      (node (ref "VCC5") (pin "P$9") (pinfunction "P$9_P$9") (pintype "bidirectional"))
    )
    (net (code "9") (name "Net-(R1-1)") (class "Default")
      (node (ref "POWER") (pin "POS") (pinfunction "POS_POS") (pintype "passive"))
      (node (ref "R1") (pin "P$1") (pinfunction "1_P$1") (pintype "passive"))
    )
    (net (code "10") (name "Net-(R2-1)") (class "Default")
      (node (ref "HELLO") (pin "POS") (pinfunction "POS_POS") (pintype "passive"))
      (node (ref "R2") (pin "P$1") (pinfunction "1_P$1") (pintype "passive"))
    )
    (net (code "11") (name "Net-(R3-1)") (class "Default")
      (node (ref "POWER1") (pin "POS") (pinfunction "POS_POS") (pintype "passive"))
      (node (ref "R3") (pin "P$1") (pinfunction "1_P$1") (pintype "passive"))
    )
    (net (code "12") (name "Net-(R4-1)") (class "Default")
      (node (ref "HELLO1") (pin "POS") (pinfunction "POS_POS") (pintype "passive"))
      (node (ref "R4") (pin "P$1") (pinfunction "1_P$1") (pintype "passive"))
    )
    (net (code "13") (name "Net-(R5-1)") (class "Default")
      (node (ref "POWER2") (pin "POS") (pinfunction "POS_POS") (pintype "passive"))
      (node (ref "R5") (pin "P$1") (pinfunction "1_P$1") (pintype "passive"))
    )
    (net (code "14") (name "Net-(R6-1)") (class "Default")
      (node (ref "HELLO2") (pin "POS") (pinfunction "POS_POS") (pintype "passive"))
      (node (ref "R6") (pin "P$1") (pinfunction "1_P$1") (pintype "passive"))
    )
    (net (code "15") (name "Net-(R7-1)") (class "Default")
      (node (ref "POWER3") (pin "POS") (pinfunction "POS_POS") (pintype "passive"))
      (node (ref "R7") (pin "P$1") (pinfunction "1_P$1") (pintype "passive"))
    )
    (net (code "16") (name "Net-(R8-1)") (class "Default")
      (node (ref "HELLO3") (pin "POS") (pinfunction "POS_POS") (pintype "passive"))
      (node (ref "R8") (pin "P$1") (pinfunction "1_P$1") (pintype "passive"))
    )
    (net (code "17") (name "Net-(R9-1)") (class "Default")
      (node (ref "POWER4") (pin "POS") (pinfunction "POS_POS") (pintype "passive"))
      (node (ref "R9") (pin "P$1") (pinfunction "1_P$1") (pintype "passive"))
    )
    (net (code "18") (name "Net-(R10-1)") (class "Default")
      (node (ref "HELLO4") (pin "POS") (pinfunction "POS_POS") (pintype "passive"))
      (node (ref "R10") (pin "P$1") (pinfunction "1_P$1") (pintype "passive"))
    )
    (net (code "19") (name "Net-(R11-1)") (class "Default")
      (node (ref "POWER5") (pin "POS") (pinfunction "POS_POS") (pintype "passive"))
      (node (ref "R11") (pin "P$1") (pinfunction "1_P$1") (pintype "passive"))
    )
    (net (code "20") (name "Net-(R12-1)") (class "Default")
      (node (ref "HELLO5") (pin "POS") (pinfunction "POS_POS") (pintype "passive"))
      (node (ref "R12") (pin "P$1") (pinfunction "1_P$1") (pintype "passive"))
    )
    (net (code "21") (name "unconnected-(U$1-P-Pad1)") (class "Default")
      (node (ref "U$1") (pin "1") (pinfunction "P_1") (pintype "passive"))
    )
    (net (code "22") (name "unconnected-(U$2-P-Pad1)") (class "Default")
      (node (ref "U$2") (pin "1") (pinfunction "P_1") (pintype "passive"))
    )
    (net (code "23") (name "unconnected-(U$3-P-Pad1)") (class "Default")
      (node (ref "U$3") (pin "1") (pinfunction "P_1") (pintype "passive"))
    )
    (net (code "24") (name "unconnected-(U$4-P-Pad1)") (class "Default")
      (node (ref "U$4") (pin "1") (pinfunction "P_1") (pintype "passive"))
    )
    (net (code "25") (name "unconnected-(U$5-P-Pad1)") (class "Default")
      (node (ref "U$5") (pin "1") (pinfunction "P_1") (pintype "passive"))
    )
    (net (code "26") (name "unconnected-(U$6-P-Pad1)") (class "Default")
      (node (ref "U$6") (pin "1") (pinfunction "P_1") (pintype "passive"))
    )
    (net (code "27") (name "unconnected-(U$7-P-Pad1)") (class "Default")
      (node (ref "U$7") (pin "1") (pinfunction "P_1") (pintype "passive"))
    )
    (net (code "28") (name "unconnected-(U$8-P-Pad1)") (class "Default")
      (node (ref "U$8") (pin "1") (pinfunction "P_1") (pintype "passive"))
    )
    (net (code "29") (name "unconnected-(U$9-P-Pad1)") (class "Default")
      (node (ref "U$9") (pin "1") (pinfunction "P_1") (pintype "passive"))
    )
    (net (code "30") (name "unconnected-(U$10-P-Pad1)") (class "Default")
      (node (ref "U$10") (pin "1") (pinfunction "P_1") (pintype "passive"))
    )
    (net (code "31") (name "unconnected-(U$11-P-Pad1)") (class "Default")
      (node (ref "U$11") (pin "1") (pinfunction "P_1") (pintype "passive"))
    )
    (net (code "32") (name "unconnected-(U$12-P-Pad1)") (class "Default")
      (node (ref "U$12") (pin "1") (pinfunction "P_1") (pintype "passive"))
    )
    (net (code "33") (name "unconnected-(U$13-P-Pad1)") (class "Default")
      (node (ref "U$13") (pin "1") (pinfunction "P_1") (pintype "passive"))
    )
    (net (code "34") (name "unconnected-(U$14-P-Pad1)") (class "Default")
      (node (ref "U$14") (pin "1") (pinfunction "P_1") (pintype "passive"))
    )
    (net (code "35") (name "unconnected-(U$15-P-Pad1)") (class "Default")
      (node (ref "U$15") (pin "1") (pinfunction "P_1") (pintype "passive"))
    )
    (net (code "36") (name "unconnected-(U$16-P-Pad1)") (class "Default")
      (node (ref "U$16") (pin "1") (pinfunction "P_1") (pintype "passive"))
    )
    (net (code "37") (name "unconnected-(U$17-P-Pad1)") (class "Default")
      (node (ref "U$17") (pin "1") (pinfunction "P_1") (pintype "passive"))
    )
    (net (code "38") (name "unconnected-(U$18-P-Pad1)") (class "Default")
      (node (ref "U$18") (pin "1") (pinfunction "P_1") (pintype "passive"))
    )
    (net (code "39") (name "unconnected-(U$19-P-Pad1)") (class "Default")
      (node (ref "U$19") (pin "1") (pinfunction "P_1") (pintype "passive"))
    )
    (net (code "40") (name "unconnected-(U$20-P-Pad1)") (class "Default")
      (node (ref "U$20") (pin "1") (pinfunction "P_1") (pintype "passive"))
    )
    (net (code "41") (name "unconnected-(U$21-P-Pad1)") (class "Default")
      (node (ref "U$21") (pin "1") (pinfunction "P_1") (pintype "passive"))
    )
    (net (code "42") (name "unconnected-(U$22-P-Pad1)") (class "Default")
      (node (ref "U$22") (pin "1") (pinfunction "P_1") (pintype "passive"))
    )
    (net (code "43") (name "unconnected-(U$23-P-Pad1)") (class "Default")
      (node (ref "U$23") (pin "1") (pinfunction "P_1") (pintype "passive"))
    )
    (net (code "44") (name "unconnected-(U$24-P-Pad1)") (class "Default")
      (node (ref "U$24") (pin "1") (pinfunction "P_1") (pintype "passive"))
    )
    (net (code "45") (name "unconnected-(U$25-P-Pad1)") (class "Default")
      (node (ref "U$25") (pin "1") (pinfunction "P_1") (pintype "passive"))
    )
    (net (code "46") (name "unconnected-(U$26-P-Pad1)") (class "Default")
      (node (ref "U$26") (pin "1") (pinfunction "P_1") (pintype "passive"))
    )
    (net (code "47") (name "unconnected-(U$27-P-Pad1)") (class "Default")
      (node (ref "U$27") (pin "1") (pinfunction "P_1") (pintype "passive"))
    )
    (net (code "48") (name "unconnected-(U$28-P-Pad1)") (class "Default")
      (node (ref "U$28") (pin "1") (pinfunction "P_1") (pintype "passive"))
    )
    (net (code "49") (name "unconnected-(U$29-P-Pad1)") (class "Default")
      (node (ref "U$29") (pin "1") (pinfunction "P_1") (pintype "passive"))
    )
    (net (code "50") (name "unconnected-(U$30-P-Pad1)") (class "Default")
      (node (ref "U$30") (pin "1") (pinfunction "P_1") (pintype "passive"))
    )
    (net (code "51") (name "unconnected-(U$31-P-Pad1)") (class "Default")
      (node (ref "U$31") (pin "1") (pinfunction "P_1") (pintype "passive"))
    )
    (net (code "52") (name "unconnected-(U$32-P-Pad1)") (class "Default")
      (node (ref "U$32") (pin "1") (pinfunction "P_1") (pintype "passive"))
    )
    (net (code "53") (name "unconnected-(U$33-P-Pad1)") (class "Default")
      (node (ref "U$33") (pin "1") (pinfunction "P_1") (pintype "passive"))
    )
    (net (code "54") (name "unconnected-(U$34-P-Pad1)") (class "Default")
      (node (ref "U$34") (pin "1") (pinfunction "P_1") (pintype "passive"))
    )
    (net (code "55") (name "unconnected-(U$35-P-Pad1)") (class "Default")
      (node (ref "U$35") (pin "1") (pinfunction "P_1") (pintype "passive"))
    )
    (net (code "56") (name "unconnected-(U$36-P-Pad1)") (class "Default")
      (node (ref "U$36") (pin "1") (pinfunction "P_1") (pintype "passive"))
    )
    (net (code "57") (name "unconnected-(U$37-P-Pad1)") (class "Default")
      (node (ref "U$37") (pin "1") (pinfunction "P_1") (pintype "passive"))
    )
    (net (code "58") (name "unconnected-(U$38-P-Pad1)") (class "Default")
      (node (ref "U$38") (pin "1") (pinfunction "P_1") (pintype "passive"))
    )
    (net (code "59") (name "unconnected-(U$39-P-Pad1)") (class "Default")
      (node (ref "U$39") (pin "1") (pinfunction "P_1") (pintype "passive"))
    )
    (net (code "60") (name "unconnected-(U$40-P-Pad1)") (class "Default")
      (node (ref "U$40") (pin "1") (pinfunction "P_1") (pintype "passive"))
    )
    (net (code "61") (name "unconnected-(U$41-P-Pad1)") (class "Default")
      (node (ref "U$41") (pin "1") (pinfunction "P_1") (pintype "passive"))
    )
    (net (code "62") (name "unconnected-(U$42-P-Pad1)") (class "Default")
      (node (ref "U$42") (pin "1") (pinfunction "P_1") (pintype "passive"))
    )
    (net (code "63") (name "unconnected-(U$43-P-Pad1)") (class "Default")
      (node (ref "U$43") (pin "1") (pinfunction "P_1") (pintype "passive"))
    )
    (net (code "64") (name "unconnected-(U$44-P-Pad1)") (class "Default")
      (node (ref "U$44") (pin "1") (pinfunction "P_1") (pintype "passive"))
    )
    (net (code "65") (name "unconnected-(U$45-P-Pad1)") (class "Default")
      (node (ref "U$45") (pin "1") (pinfunction "P_1") (pintype "passive"))
    )
    (net (code "66") (name "unconnected-(U$46-P-Pad1)") (class "Default")
      (node (ref "U$46") (pin "1") (pinfunction "P_1") (pintype "passive"))
    )
    (net (code "67") (name "unconnected-(U$47-P-Pad1)") (class "Default")
      (node (ref "U$47") (pin "1") (pinfunction "P_1") (pintype "passive"))
    )
    (net (code "68") (name "unconnected-(U$48-P-Pad1)") (class "Default")
      (node (ref "U$48") (pin "1") (pinfunction "P_1") (pintype "passive"))
    )
    (net (code "69") (name "unconnected-(U$49-P-Pad1)") (class "Default")
      (node (ref "U$49") (pin "1") (pinfunction "P_1") (pintype "passive"))
    )
    (net (code "70") (name "unconnected-(U$50-P-Pad1)") (class "Default")
      (node (ref "U$50") (pin "1") (pinfunction "P_1") (pintype "passive"))
    )
    (net (code "71") (name "unconnected-(U$51-P-Pad1)") (class "Default")
      (node (ref "U$51") (pin "1") (pinfunction "P_1") (pintype "passive"))
    )
    (net (code "72") (name "unconnected-(U$52-P-Pad1)") (class "Default")
      (node (ref "U$52") (pin "1") (pinfunction "P_1") (pintype "passive"))
    )
    (net (code "73") (name "unconnected-(U$53-P-Pad1)") (class "Default")
      (node (ref "U$53") (pin "1") (pinfunction "P_1") (pintype "passive"))
    )
    (net (code "74") (name "unconnected-(U$54-P-Pad1)") (class "Default")
      (node (ref "U$54") (pin "1") (pinfunction "P_1") (pintype "passive"))
    )
    (net (code "75") (name "unconnected-(U$55-P-Pad1)") (class "Default")
      (node (ref "U$55") (pin "1") (pinfunction "P_1") (pintype "passive"))
    )
    (net (code "76") (name "unconnected-(U$56-P-Pad1)") (class "Default")
      (node (ref "U$56") (pin "1") (pinfunction "P_1") (pintype "passive"))
    )
    (net (code "77") (name "unconnected-(U$57-P-Pad1)") (class "Default")
      (node (ref "U$57") (pin "1") (pinfunction "P_1") (pintype "passive"))
    )
    (net (code "78") (name "unconnected-(U$58-P-Pad1)") (class "Default")
      (node (ref "U$58") (pin "1") (pinfunction "P_1") (pintype "passive"))
    )
    (net (code "79") (name "unconnected-(U$59-P-Pad1)") (class "Default")
      (node (ref "U$59") (pin "1") (pinfunction "P_1") (pintype "passive"))
    )
    (net (code "80") (name "unconnected-(U$60-P-Pad1)") (class "Default")
      (node (ref "U$60") (pin "1") (pinfunction "P_1") (pintype "passive"))
    )
    (net (code "81") (name "unconnected-(U$61-P-Pad1)") (class "Default")
      (node (ref "U$61") (pin "1") (pinfunction "P_1") (pintype "passive"))
    )
    (net (code "82") (name "unconnected-(U$62-P-Pad1)") (class "Default")
      (node (ref "U$62") (pin "1") (pinfunction "P_1") (pintype "passive"))
    )
    (net (code "83") (name "unconnected-(U$63-P-Pad1)") (class "Default")
      (node (ref "U$63") (pin "1") (pinfunction "P_1") (pintype "passive"))
    )
    (net (code "84") (name "unconnected-(U$64-P-Pad1)") (class "Default")
      (node (ref "U$64") (pin "1") (pinfunction "P_1") (pintype "passive"))
    )
    (net (code "85") (name "unconnected-(U$65-P-Pad1)") (class "Default")
      (node (ref "U$65") (pin "1") (pinfunction "P_1") (pintype "passive"))
    )
    (net (code "86") (name "unconnected-(U$66-P-Pad1)") (class "Default")
      (node (ref "U$66") (pin "1") (pinfunction "P_1") (pintype "passive"))
    )
    (net (code "87") (name "unconnected-(U$67-P-Pad1)") (class "Default")
      (node (ref "U$67") (pin "1") (pinfunction "P_1") (pintype "passive"))
    )
    (net (code "88") (name "unconnected-(U$68-P-Pad1)") (class "Default")
      (node (ref "U$68") (pin "1") (pinfunction "P_1") (pintype "passive"))
    )
    (net (code "89") (name "unconnected-(U$69-P-Pad1)") (class "Default")
      (node (ref "U$69") (pin "1") (pinfunction "P_1") (pintype "passive"))
    )
    (net (code "90") (name "unconnected-(U$70-P-Pad1)") (class "Default")
      (node (ref "U$70") (pin "1") (pinfunction "P_1") (pintype "passive"))
    )
    (net (code "91") (name "unconnected-(U$93-P-Pad1)") (class "Default")
      (node (ref "U$93") (pin "1") (pinfunction "P_1") (pintype "passive"))
    )
    (net (code "92") (name "unconnected-(U$94-P-Pad1)") (class "Default")
      (node (ref "U$94") (pin "1") (pinfunction "P_1") (pintype "passive"))
    )
    (net (code "93") (name "unconnected-(U$95-P-Pad1)") (class "Default")
      (node (ref "U$95") (pin "1") (pinfunction "P_1") (pintype "passive"))
    )
    (net (code "94") (name "unconnected-(U$96-P-Pad1)") (class "Default")
      (node (ref "U$96") (pin "1") (pinfunction "P_1") (pintype "passive"))
    )
    (net (code "95") (name "unconnected-(U$97-P-Pad1)") (class "Default")
      (node (ref "U$97") (pin "1") (pinfunction "P_1") (pintype "passive"))
    )
    (net (code "96") (name "unconnected-(U$98-P-Pad1)") (class "Default")
      (node (ref "U$98") (pin "1") (pinfunction "P_1") (pintype "passive"))
    )
    (net (code "97") (name "unconnected-(U$99-P-Pad1)") (class "Default")
      (node (ref "U$99") (pin "1") (pinfunction "P_1") (pintype "passive"))
    )
    (net (code "98") (name "unconnected-(U$100-P-Pad1)") (class "Default")
      (node (ref "U$100") (pin "1") (pinfunction "P_1") (pintype "passive"))
    )
    (net (code "99") (name "unconnected-(U$101-P-Pad1)") (class "Default")
      (node (ref "U$101") (pin "1") (pinfunction "P_1") (pintype "passive"))
    )
    (net (code "100") (name "unconnected-(U$102-P-Pad1)") (class "Default")
      (node (ref "U$102") (pin "1") (pinfunction "P_1") (pintype "passive"))
    )
    (net (code "101") (name "unconnected-(U$103-P-Pad1)") (class "Default")
      (node (ref "U$103") (pin "1") (pinfunction "P_1") (pintype "passive"))
    )
    (net (code "102") (name "unconnected-(U$104-P-Pad1)") (class "Default")
      (node (ref "U$104") (pin "1") (pinfunction "P_1") (pintype "passive"))
    )
    (net (code "103") (name "unconnected-(U$105-P-Pad1)") (class "Default")
      (node (ref "U$105") (pin "1") (pinfunction "P_1") (pintype "passive"))
    )
    (net (code "104") (name "unconnected-(U$106-P-Pad1)") (class "Default")
      (node (ref "U$106") (pin "1") (pinfunction "P_1") (pintype "passive"))
    )
    (net (code "105") (name "unconnected-(U$107-P-Pad1)") (class "Default")
      (node (ref "U$107") (pin "1") (pinfunction "P_1") (pintype "passive"))
    )
    (net (code "106") (name "unconnected-(U$108-P-Pad1)") (class "Default")
      (node (ref "U$108") (pin "1") (pinfunction "P_1") (pintype "passive"))
    )
    (net (code "107") (name "unconnected-(U$109-P-Pad1)") (class "Default")
      (node (ref "U$109") (pin "1") (pinfunction "P_1") (pintype "passive"))
    )
    (net (code "108") (name "unconnected-(U$110-P-Pad1)") (class "Default")
      (node (ref "U$110") (pin "1") (pinfunction "P_1") (pintype "passive"))
    )
    (net (code "109") (name "unconnected-(U$111-P-Pad1)") (class "Default")
      (node (ref "U$111") (pin "1") (pinfunction "P_1") (pintype "passive"))
    )
    (net (code "110") (name "unconnected-(U$112-P-Pad1)") (class "Default")
      (node (ref "U$112") (pin "1") (pinfunction "P_1") (pintype "passive"))
    )
    (net (code "111") (name "unconnected-(U$113-P-Pad1)") (class "Default")
      (node (ref "U$113") (pin "1") (pinfunction "P_1") (pintype "passive"))
    )
    (net (code "112") (name "unconnected-(U$114-P-Pad1)") (class "Default")
      (node (ref "U$114") (pin "1") (pinfunction "P_1") (pintype "passive"))
    )
    (net (code "113") (name "unconnected-(U$115-P-Pad1)") (class "Default")
      (node (ref "U$115") (pin "1") (pinfunction "P_1") (pintype "passive"))
    )
    (net (code "114") (name "unconnected-(U$116-P-Pad1)") (class "Default")
      (node (ref "U$116") (pin "1") (pinfunction "P_1") (pintype "passive"))
    )
    (net (code "115") (name "unconnected-(U$117-P-Pad1)") (class "Default")
      (node (ref "U$117") (pin "1") (pinfunction "P_1") (pintype "passive"))
    )
    (net (code "116") (name "unconnected-(U$118-P-Pad1)") (class "Default")
      (node (ref "U$118") (pin "1") (pinfunction "P_1") (pintype "passive"))
    )
    (net (code "117") (name "unconnected-(U$119-P-Pad1)") (class "Default")
      (node (ref "U$119") (pin "1") (pinfunction "P_1") (pintype "passive"))
    )
    (net (code "118") (name "unconnected-(U$120-P-Pad1)") (class "Default")
      (node (ref "U$120") (pin "1") (pinfunction "P_1") (pintype "passive"))
    )
    (net (code "119") (name "unconnected-(U$121-P-Pad1)") (class "Default")
      (node (ref "U$121") (pin "1") (pinfunction "P_1") (pintype "passive"))
    )
    (net (code "120") (name "unconnected-(U$122-P-Pad1)") (class "Default")
      (node (ref "U$122") (pin "1") (pinfunction "P_1") (pintype "passive"))
    )
    (net (code "121") (name "unconnected-(U$123-P-Pad1)") (class "Default")
      (node (ref "U$123") (pin "1") (pinfunction "P_1") (pintype "passive"))
    )
    (net (code "122") (name "unconnected-(U$124-P-Pad1)") (class "Default")
      (node (ref "U$124") (pin "1") (pinfunction "P_1") (pintype "passive"))
    )
    (net (code "123") (name "unconnected-(U$125-P-Pad1)") (class "Default")
      (node (ref "U$125") (pin "1") (pinfunction "P_1") (pintype "passive"))
    )
    (net (code "124") (name "unconnected-(U$126-P-Pad1)") (class "Default")
      (node (ref "U$126") (pin "1") (pinfunction "P_1") (pintype "passive"))
    )
    (net (code "125") (name "unconnected-(U$127-P-Pad1)") (class "Default")
      (node (ref "U$127") (pin "1") (pinfunction "P_1") (pintype "passive"))
    )
    (net (code "126") (name "unconnected-(U$128-P-Pad1)") (class "Default")
      (node (ref "U$128") (pin "1") (pinfunction "P_1") (pintype "passive"))
    )
    (net (code "127") (name "unconnected-(U$129-P-Pad1)") (class "Default")
      (node (ref "U$129") (pin "1") (pinfunction "P_1") (pintype "passive"))
    )
    (net (code "128") (name "unconnected-(U$130-P-Pad1)") (class "Default")
      (node (ref "U$130") (pin "1") (pinfunction "P_1") (pintype "passive"))
    )
    (net (code "129") (name "unconnected-(U$131-P-Pad1)") (class "Default")
      (node (ref "U$131") (pin "1") (pinfunction "P_1") (pintype "passive"))
    )
    (net (code "130") (name "unconnected-(U$132-P-Pad1)") (class "Default")
      (node (ref "U$132") (pin "1") (pinfunction "P_1") (pintype "passive"))
    )
    (net (code "131") (name "unconnected-(U$133-P-Pad1)") (class "Default")
      (node (ref "U$133") (pin "1") (pinfunction "P_1") (pintype "passive"))
    )
    (net (code "132") (name "unconnected-(U$134-P-Pad1)") (class "Default")
      (node (ref "U$134") (pin "1") (pinfunction "P_1") (pintype "passive"))
    )
    (net (code "133") (name "unconnected-(U$135-P-Pad1)") (class "Default")
      (node (ref "U$135") (pin "1") (pinfunction "P_1") (pintype "passive"))
    )
    (net (code "134") (name "unconnected-(U$136-P-Pad1)") (class "Default")
      (node (ref "U$136") (pin "1") (pinfunction "P_1") (pintype "passive"))
    )
    (net (code "135") (name "unconnected-(U$137-P-Pad1)") (class "Default")
      (node (ref "U$137") (pin "1") (pinfunction "P_1") (pintype "passive"))
    )
    (net (code "136") (name "unconnected-(U$138-P-Pad1)") (class "Default")
      (node (ref "U$138") (pin "1") (pinfunction "P_1") (pintype "passive"))
    )
    (net (code "137") (name "unconnected-(U$139-P-Pad1)") (class "Default")
      (node (ref "U$139") (pin "1") (pinfunction "P_1") (pintype "passive"))
    )
    (net (code "138") (name "unconnected-(U$140-P-Pad1)") (class "Default")
      (node (ref "U$140") (pin "1") (pinfunction "P_1") (pintype "passive"))
    )
    (net (code "139") (name "unconnected-(U$141-P-Pad1)") (class "Default")
      (node (ref "U$141") (pin "1") (pinfunction "P_1") (pintype "passive"))
    )
    (net (code "140") (name "unconnected-(U$142-P-Pad1)") (class "Default")
      (node (ref "U$142") (pin "1") (pinfunction "P_1") (pintype "passive"))
    )
    (net (code "141") (name "unconnected-(U$143-P-Pad1)") (class "Default")
      (node (ref "U$143") (pin "1") (pinfunction "P_1") (pintype "passive"))
    )
    (net (code "142") (name "unconnected-(U$144-P-Pad1)") (class "Default")
      (node (ref "U$144") (pin "1") (pinfunction "P_1") (pintype "passive"))
    )
    (net (code "143") (name "unconnected-(U$145-P-Pad1)") (class "Default")
      (node (ref "U$145") (pin "1") (pinfunction "P_1") (pintype "passive"))
    )
    (net (code "144") (name "unconnected-(U$146-P-Pad1)") (class "Default")
      (node (ref "U$146") (pin "1") (pinfunction "P_1") (pintype "passive"))
    )
    (net (code "145") (name "unconnected-(U$147-P-Pad1)") (class "Default")
      (node (ref "U$147") (pin "1") (pinfunction "P_1") (pintype "passive"))
    )
    (net (code "146") (name "unconnected-(U$148-P-Pad1)") (class "Default")
      (node (ref "U$148") (pin "1") (pinfunction "P_1") (pintype "passive"))
    )
    (net (code "147") (name "unconnected-(U$149-P-Pad1)") (class "Default")
      (node (ref "U$149") (pin "1") (pinfunction "P_1") (pintype "passive"))
    )
    (net (code "148") (name "unconnected-(U$150-P-Pad1)") (class "Default")
      (node (ref "U$150") (pin "1") (pinfunction "P_1") (pintype "passive"))
    )
    (net (code "149") (name "unconnected-(U$151-P-Pad1)") (class "Default")
      (node (ref "U$151") (pin "1") (pinfunction "P_1") (pintype "passive"))
    )
    (net (code "150") (name "unconnected-(U$152-P-Pad1)") (class "Default")
      (node (ref "U$152") (pin "1") (pinfunction "P_1") (pintype "passive"))
    )
    (net (code "151") (name "unconnected-(U$153-P-Pad1)") (class "Default")
      (node (ref "U$153") (pin "1") (pinfunction "P_1") (pintype "passive"))
    )
    (net (code "152") (name "unconnected-(U$154-P-Pad1)") (class "Default")
      (node (ref "U$154") (pin "1") (pinfunction "P_1") (pintype "passive"))
    )
    (net (code "153") (name "unconnected-(U$155-P-Pad1)") (class "Default")
      (node (ref "U$155") (pin "1") (pinfunction "P_1") (pintype "passive"))
    )
    (net (code "154") (name "unconnected-(U$156-P-Pad1)") (class "Default")
      (node (ref "U$156") (pin "1") (pinfunction "P_1") (pintype "passive"))
    )
    (net (code "155") (name "unconnected-(U$157-P-Pad1)") (class "Default")
      (node (ref "U$157") (pin "1") (pinfunction "P_1") (pintype "passive"))
    )
    (net (code "156") (name "unconnected-(U$158-P-Pad1)") (class "Default")
      (node (ref "U$158") (pin "1") (pinfunction "P_1") (pintype "passive"))
    )
    (net (code "157") (name "unconnected-(U$159-P-Pad1)") (class "Default")
      (node (ref "U$159") (pin "1") (pinfunction "P_1") (pintype "passive"))
    )
    (net (code "158") (name "unconnected-(U$160-P-Pad1)") (class "Default")
      (node (ref "U$160") (pin "1") (pinfunction "P_1") (pintype "passive"))
    )
    (net (code "159") (name "unconnected-(U$161-P-Pad1)") (class "Default")
      (node (ref "U$161") (pin "1") (pinfunction "P_1") (pintype "passive"))
    )
    (net (code "160") (name "unconnected-(U$162-P-Pad1)") (class "Default")
      (node (ref "U$162") (pin "1") (pinfunction "P_1") (pintype "passive"))
    )
    (net (code "161") (name "unconnected-(U$163-P-Pad1)") (class "Default")
      (node (ref "U$163") (pin "1") (pinfunction "P_1") (pintype "passive"))
    )
    (net (code "162") (name "unconnected-(U$164-P-Pad1)") (class "Default")
      (node (ref "U$164") (pin "1") (pinfunction "P_1") (pintype "passive"))
    )
    (net (code "163") (name "unconnected-(U$165-P-Pad1)") (class "Default")
      (node (ref "U$165") (pin "1") (pinfunction "P_1") (pintype "passive"))
    )
    (net (code "164") (name "unconnected-(U$166-P-Pad1)") (class "Default")
      (node (ref "U$166") (pin "1") (pinfunction "P_1") (pintype "passive"))
    )
    (net (code "165") (name "unconnected-(U$167-P-Pad1)") (class "Default")
      (node (ref "U$167") (pin "1") (pinfunction "P_1") (pintype "passive"))
    )
    (net (code "166") (name "unconnected-(U$168-P-Pad1)") (class "Default")
      (node (ref "U$168") (pin "1") (pinfunction "P_1") (pintype "passive"))
    )
    (net (code "167") (name "unconnected-(U$169-P-Pad1)") (class "Default")
      (node (ref "U$169") (pin "1") (pinfunction "P_1") (pintype "passive"))
    )
    (net (code "168") (name "unconnected-(U$170-P-Pad1)") (class "Default")
      (node (ref "U$170") (pin "1") (pinfunction "P_1") (pintype "passive"))
    )
    (net (code "169") (name "unconnected-(U$171-P-Pad1)") (class "Default")
      (node (ref "U$171") (pin "1") (pinfunction "P_1") (pintype "passive"))
    )
    (net (code "170") (name "unconnected-(U$172-P-Pad1)") (class "Default")
      (node (ref "U$172") (pin "1") (pinfunction "P_1") (pintype "passive"))
    )
    (net (code "171") (name "unconnected-(U$173-P-Pad1)") (class "Default")
      (node (ref "U$173") (pin "1") (pinfunction "P_1") (pintype "passive"))
    )
    (net (code "172") (name "unconnected-(U$174-P-Pad1)") (class "Default")
      (node (ref "U$174") (pin "1") (pinfunction "P_1") (pintype "passive"))
    )
    (net (code "173") (name "unconnected-(U$175-P-Pad1)") (class "Default")
      (node (ref "U$175") (pin "1") (pinfunction "P_1") (pintype "passive"))
    )
    (net (code "174") (name "unconnected-(U$176-P-Pad1)") (class "Default")
      (node (ref "U$176") (pin "1") (pinfunction "P_1") (pintype "passive"))
    )
    (net (code "175") (name "unconnected-(U$177-P-Pad1)") (class "Default")
      (node (ref "U$177") (pin "1") (pinfunction "P_1") (pintype "passive"))
    )
    (net (code "176") (name "unconnected-(U$178-P-Pad1)") (class "Default")
      (node (ref "U$178") (pin "1") (pinfunction "P_1") (pintype "passive"))
    )
    (net (code "177") (name "unconnected-(U$179-P-Pad1)") (class "Default")
      (node (ref "U$179") (pin "1") (pinfunction "P_1") (pintype "passive"))
    )
    (net (code "178") (name "unconnected-(U$180-P-Pad1)") (class "Default")
      (node (ref "U$180") (pin "1") (pinfunction "P_1") (pintype "passive"))
    )
    (net (code "179") (name "unconnected-(U$181-P-Pad1)") (class "Default")
      (node (ref "U$181") (pin "1") (pinfunction "P_1") (pintype "passive"))
    )
    (net (code "180") (name "unconnected-(U$182-P-Pad1)") (class "Default")
      (node (ref "U$182") (pin "1") (pinfunction "P_1") (pintype "passive"))
    )
    (net (code "181") (name "unconnected-(U$183-P-Pad1)") (class "Default")
      (node (ref "U$183") (pin "1") (pinfunction "P_1") (pintype "passive"))
    )
    (net (code "182") (name "unconnected-(U$184-P-Pad1)") (class "Default")
      (node (ref "U$184") (pin "1") (pinfunction "P_1") (pintype "passive"))
    )
    (net (code "183") (name "unconnected-(U$185-P-Pad1)") (class "Default")
      (node (ref "U$185") (pin "1") (pinfunction "P_1") (pintype "passive"))
    )
    (net (code "184") (name "unconnected-(U$186-P-Pad1)") (class "Default")
      (node (ref "U$186") (pin "1") (pinfunction "P_1") (pintype "passive"))
    )
    (net (code "185") (name "unconnected-(U$187-P-Pad1)") (class "Default")
      (node (ref "U$187") (pin "1") (pinfunction "P_1") (pintype "passive"))
    )
    (net (code "186") (name "unconnected-(U$188-P-Pad1)") (class "Default")
      (node (ref "U$188") (pin "1") (pinfunction "P_1") (pintype "passive"))
    )
    (net (code "187") (name "unconnected-(U$189-P-Pad1)") (class "Default")
      (node (ref "U$189") (pin "1") (pinfunction "P_1") (pintype "passive"))
    )
    (net (code "188") (name "unconnected-(U$190-P-Pad1)") (class "Default")
      (node (ref "U$190") (pin "1") (pinfunction "P_1") (pintype "passive"))
    )
    (net (code "189") (name "unconnected-(U$191-P-Pad1)") (class "Default")
      (node (ref "U$191") (pin "1") (pinfunction "P_1") (pintype "passive"))
    )
    (net (code "190") (name "unconnected-(U$192-P-Pad1)") (class "Default")
      (node (ref "U$192") (pin "1") (pinfunction "P_1") (pintype "passive"))
    )
    (net (code "191") (name "unconnected-(U$215-P-Pad1)") (class "Default")
      (node (ref "U$215") (pin "1") (pinfunction "P_1") (pintype "passive"))
    )
    (net (code "192") (name "unconnected-(U$216-P-Pad1)") (class "Default")
      (node (ref "U$216") (pin "1") (pinfunction "P_1") (pintype "passive"))
    )
    (net (code "193") (name "unconnected-(U$217-P-Pad1)") (class "Default")
      (node (ref "U$217") (pin "1") (pinfunction "P_1") (pintype "passive"))
    )
    (net (code "194") (name "unconnected-(U$218-P-Pad1)") (class "Default")
      (node (ref "U$218") (pin "1") (pinfunction "P_1") (pintype "passive"))
    )
    (net (code "195") (name "unconnected-(U$219-P-Pad1)") (class "Default")
      (node (ref "U$219") (pin "1") (pinfunction "P_1") (pintype "passive"))
    )
    (net (code "196") (name "unconnected-(U$220-P-Pad1)") (class "Default")
      (node (ref "U$220") (pin "1") (pinfunction "P_1") (pintype "passive"))
    )
    (net (code "197") (name "unconnected-(U$221-P-Pad1)") (class "Default")
      (node (ref "U$221") (pin "1") (pinfunction "P_1") (pintype "passive"))
    )
    (net (code "198") (name "unconnected-(U$222-P-Pad1)") (class "Default")
      (node (ref "U$222") (pin "1") (pinfunction "P_1") (pintype "passive"))
    )
    (net (code "199") (name "unconnected-(U$223-P-Pad1)") (class "Default")
      (node (ref "U$223") (pin "1") (pinfunction "P_1") (pintype "passive"))
    )
    (net (code "200") (name "unconnected-(U$224-P-Pad1)") (class "Default")
      (node (ref "U$224") (pin "1") (pinfunction "P_1") (pintype "passive"))
    )
    (net (code "201") (name "unconnected-(U$225-P-Pad1)") (class "Default")
      (node (ref "U$225") (pin "1") (pinfunction "P_1") (pintype "passive"))
    )
    (net (code "202") (name "unconnected-(U$226-P-Pad1)") (class "Default")
      (node (ref "U$226") (pin "1") (pinfunction "P_1") (pintype "passive"))
    )
    (net (code "203") (name "unconnected-(U$227-P-Pad1)") (class "Default")
      (node (ref "U$227") (pin "1") (pinfunction "P_1") (pintype "passive"))
    )
    (net (code "204") (name "unconnected-(U$228-P-Pad1)") (class "Default")
      (node (ref "U$228") (pin "1") (pinfunction "P_1") (pintype "passive"))
    )
    (net (code "205") (name "unconnected-(U$229-P-Pad1)") (class "Default")
      (node (ref "U$229") (pin "1") (pinfunction "P_1") (pintype "passive"))
    )
    (net (code "206") (name "unconnected-(U$230-P-Pad1)") (class "Default")
      (node (ref "U$230") (pin "1") (pinfunction "P_1") (pintype "passive"))
    )
    (net (code "207") (name "unconnected-(U$231-P-Pad1)") (class "Default")
      (node (ref "U$231") (pin "1") (pinfunction "P_1") (pintype "passive"))
    )
    (net (code "208") (name "unconnected-(U$232-P-Pad1)") (class "Default")
      (node (ref "U$232") (pin "1") (pinfunction "P_1") (pintype "passive"))
    )
    (net (code "209") (name "unconnected-(U$233-P-Pad1)") (class "Default")
      (node (ref "U$233") (pin "1") (pinfunction "P_1") (pintype "passive"))
    )
    (net (code "210") (name "unconnected-(U$234-P-Pad1)") (class "Default")
      (node (ref "U$234") (pin "1") (pinfunction "P_1") (pintype "passive"))
    )
    (net (code "211") (name "unconnected-(U$235-P-Pad1)") (class "Default")
      (node (ref "U$235") (pin "1") (pinfunction "P_1") (pintype "passive"))
    )
    (net (code "212") (name "unconnected-(U$236-P-Pad1)") (class "Default")
      (node (ref "U$236") (pin "1") (pinfunction "P_1") (pintype "passive"))
    )
    (net (code "213") (name "unconnected-(U$237-P-Pad1)") (class "Default")
      (node (ref "U$237") (pin "1") (pinfunction "P_1") (pintype "passive"))
    )
    (net (code "214") (name "unconnected-(U$238-P-Pad1)") (class "Default")
      (node (ref "U$238") (pin "1") (pinfunction "P_1") (pintype "passive"))
    )
    (net (code "215") (name "unconnected-(U$239-P-Pad1)") (class "Default")
      (node (ref "U$239") (pin "1") (pinfunction "P_1") (pintype "passive"))
    )
    (net (code "216") (name "unconnected-(U$240-P-Pad1)") (class "Default")
      (node (ref "U$240") (pin "1") (pinfunction "P_1") (pintype "passive"))
    )
    (net (code "217") (name "unconnected-(U$241-P-Pad1)") (class "Default")
      (node (ref "U$241") (pin "1") (pinfunction "P_1") (pintype "passive"))
    )
    (net (code "218") (name "unconnected-(U$242-P-Pad1)") (class "Default")
      (node (ref "U$242") (pin "1") (pinfunction "P_1") (pintype "passive"))
    )
    (net (code "219") (name "unconnected-(U$243-P-Pad1)") (class "Default")
      (node (ref "U$243") (pin "1") (pinfunction "P_1") (pintype "passive"))
    )
    (net (code "220") (name "unconnected-(U$244-P-Pad1)") (class "Default")
      (node (ref "U$244") (pin "1") (pinfunction "P_1") (pintype "passive"))
    )
    (net (code "221") (name "unconnected-(U$245-P-Pad1)") (class "Default")
      (node (ref "U$245") (pin "1") (pinfunction "P_1") (pintype "passive"))
    )
    (net (code "222") (name "unconnected-(U$246-P-Pad1)") (class "Default")
      (node (ref "U$246") (pin "1") (pinfunction "P_1") (pintype "passive"))
    )
    (net (code "223") (name "unconnected-(U$247-P-Pad1)") (class "Default")
      (node (ref "U$247") (pin "1") (pinfunction "P_1") (pintype "passive"))
    )
    (net (code "224") (name "unconnected-(U$248-P-Pad1)") (class "Default")
      (node (ref "U$248") (pin "1") (pinfunction "P_1") (pintype "passive"))
    )
    (net (code "225") (name "unconnected-(U$249-P-Pad1)") (class "Default")
      (node (ref "U$249") (pin "1") (pinfunction "P_1") (pintype "passive"))
    )
    (net (code "226") (name "unconnected-(U$250-P-Pad1)") (class "Default")
      (node (ref "U$250") (pin "1") (pinfunction "P_1") (pintype "passive"))
    )
    (net (code "227") (name "unconnected-(U$251-P-Pad1)") (class "Default")
      (node (ref "U$251") (pin "1") (pinfunction "P_1") (pintype "passive"))
    )
    (net (code "228") (name "unconnected-(U$252-P-Pad1)") (class "Default")
      (node (ref "U$252") (pin "1") (pinfunction "P_1") (pintype "passive"))
    )
    (net (code "229") (name "unconnected-(U$253-P-Pad1)") (class "Default")
      (node (ref "U$253") (pin "1") (pinfunction "P_1") (pintype "passive"))
    )
    (net (code "230") (name "unconnected-(U$254-P-Pad1)") (class "Default")
      (node (ref "U$254") (pin "1") (pinfunction "P_1") (pintype "passive"))
    )
    (net (code "231") (name "unconnected-(U$255-P-Pad1)") (class "Default")
      (node (ref "U$255") (pin "1") (pinfunction "P_1") (pintype "passive"))
    )
    (net (code "232") (name "unconnected-(U$256-P-Pad1)") (class "Default")
      (node (ref "U$256") (pin "1") (pinfunction "P_1") (pintype "passive"))
    )
    (net (code "233") (name "unconnected-(U$257-P-Pad1)") (class "Default")
      (node (ref "U$257") (pin "1") (pinfunction "P_1") (pintype "passive"))
    )
    (net (code "234") (name "unconnected-(U$258-P-Pad1)") (class "Default")
      (node (ref "U$258") (pin "1") (pinfunction "P_1") (pintype "passive"))
    )
    (net (code "235") (name "unconnected-(U$259-P-Pad1)") (class "Default")
      (node (ref "U$259") (pin "1") (pinfunction "P_1") (pintype "passive"))
    )
    (net (code "236") (name "unconnected-(U$260-P-Pad1)") (class "Default")
      (node (ref "U$260") (pin "1") (pinfunction "P_1") (pintype "passive"))
    )
    (net (code "237") (name "unconnected-(U$261-P-Pad1)") (class "Default")
      (node (ref "U$261") (pin "1") (pinfunction "P_1") (pintype "passive"))
    )
    (net (code "238") (name "unconnected-(U$262-P-Pad1)") (class "Default")
      (node (ref "U$262") (pin "1") (pinfunction "P_1") (pintype "passive"))
    )
    (net (code "239") (name "unconnected-(U$263-P-Pad1)") (class "Default")
      (node (ref "U$263") (pin "1") (pinfunction "P_1") (pintype "passive"))
    )
    (net (code "240") (name "unconnected-(U$264-P-Pad1)") (class "Default")
      (node (ref "U$264") (pin "1") (pinfunction "P_1") (pintype "passive"))
    )
    (net (code "241") (name "unconnected-(U$265-P-Pad1)") (class "Default")
      (node (ref "U$265") (pin "1") (pinfunction "P_1") (pintype "passive"))
    )
    (net (code "242") (name "unconnected-(U$266-P-Pad1)") (class "Default")
      (node (ref "U$266") (pin "1") (pinfunction "P_1") (pintype "passive"))
    )
    (net (code "243") (name "unconnected-(U$267-P-Pad1)") (class "Default")
      (node (ref "U$267") (pin "1") (pinfunction "P_1") (pintype "passive"))
    )
    (net (code "244") (name "unconnected-(U$268-P-Pad1)") (class "Default")
      (node (ref "U$268") (pin "1") (pinfunction "P_1") (pintype "passive"))
    )
    (net (code "245") (name "unconnected-(U$269-P-Pad1)") (class "Default")
      (node (ref "U$269") (pin "1") (pinfunction "P_1") (pintype "passive"))
    )
    (net (code "246") (name "unconnected-(U$270-P-Pad1)") (class "Default")
      (node (ref "U$270") (pin "1") (pinfunction "P_1") (pintype "passive"))
    )
    (net (code "247") (name "unconnected-(U$271-P-Pad1)") (class "Default")
      (node (ref "U$271") (pin "1") (pinfunction "P_1") (pintype "passive"))
    )
    (net (code "248") (name "unconnected-(U$272-P-Pad1)") (class "Default")
      (node (ref "U$272") (pin "1") (pinfunction "P_1") (pintype "passive"))
    )
    (net (code "249") (name "unconnected-(U$273-P-Pad1)") (class "Default")
      (node (ref "U$273") (pin "1") (pinfunction "P_1") (pintype "passive"))
    )
    (net (code "250") (name "unconnected-(U$274-P-Pad1)") (class "Default")
      (node (ref "U$274") (pin "1") (pinfunction "P_1") (pintype "passive"))
    )
    (net (code "251") (name "unconnected-(U$275-P-Pad1)") (class "Default")
      (node (ref "U$275") (pin "1") (pinfunction "P_1") (pintype "passive"))
    )
    (net (code "252") (name "unconnected-(U$276-P-Pad1)") (class "Default")
      (node (ref "U$276") (pin "1") (pinfunction "P_1") (pintype "passive"))
    )
    (net (code "253") (name "unconnected-(U$277-P-Pad1)") (class "Default")
      (node (ref "U$277") (pin "1") (pinfunction "P_1") (pintype "passive"))
    )
    (net (code "254") (name "unconnected-(U$278-P-Pad1)") (class "Default")
      (node (ref "U$278") (pin "1") (pinfunction "P_1") (pintype "passive"))
    )
    (net (code "255") (name "unconnected-(U$279-P-Pad1)") (class "Default")
      (node (ref "U$279") (pin "1") (pinfunction "P_1") (pintype "passive"))
    )
    (net (code "256") (name "unconnected-(U$280-P-Pad1)") (class "Default")
      (node (ref "U$280") (pin "1") (pinfunction "P_1") (pintype "passive"))
    )
    (net (code "257") (name "unconnected-(U$281-P-Pad1)") (class "Default")
      (node (ref "U$281") (pin "1") (pinfunction "P_1") (pintype "passive"))
    )
    (net (code "258") (name "unconnected-(U$282-P-Pad1)") (class "Default")
      (node (ref "U$282") (pin "1") (pinfunction "P_1") (pintype "passive"))
    )
    (net (code "259") (name "unconnected-(U$283-P-Pad1)") (class "Default")
      (node (ref "U$283") (pin "1") (pinfunction "P_1") (pintype "passive"))
    )
    (net (code "260") (name "unconnected-(U$284-P-Pad1)") (class "Default")
      (node (ref "U$284") (pin "1") (pinfunction "P_1") (pintype "passive"))
    )
    (net (code "261") (name "unconnected-(U$285-P-Pad1)") (class "Default")
      (node (ref "U$285") (pin "1") (pinfunction "P_1") (pintype "passive"))
    )
    (net (code "262") (name "unconnected-(U$286-P-Pad1)") (class "Default")
      (node (ref "U$286") (pin "1") (pinfunction "P_1") (pintype "passive"))
    )
    (net (code "263") (name "unconnected-(U$287-P-Pad1)") (class "Default")
      (node (ref "U$287") (pin "1") (pinfunction "P_1") (pintype "passive"))
    )
    (net (code "264") (name "unconnected-(U$288-P-Pad1)") (class "Default")
      (node (ref "U$288") (pin "1") (pinfunction "P_1") (pintype "passive"))
    )
    (net (code "265") (name "unconnected-(U$289-P-Pad1)") (class "Default")
      (node (ref "U$289") (pin "1") (pinfunction "P_1") (pintype "passive"))
    )
    (net (code "266") (name "unconnected-(U$290-P-Pad1)") (class "Default")
      (node (ref "U$290") (pin "1") (pinfunction "P_1") (pintype "passive"))
    )
    (net (code "267") (name "unconnected-(U$291-P-Pad1)") (class "Default")
      (node (ref "U$291") (pin "1") (pinfunction "P_1") (pintype "passive"))
    )
    (net (code "268") (name "unconnected-(U$292-P-Pad1)") (class "Default")
      (node (ref "U$292") (pin "1") (pinfunction "P_1") (pintype "passive"))
    )
    (net (code "269") (name "unconnected-(U$293-P-Pad1)") (class "Default")
      (node (ref "U$293") (pin "1") (pinfunction "P_1") (pintype "passive"))
    )
    (net (code "270") (name "unconnected-(U$294-P-Pad1)") (class "Default")
      (node (ref "U$294") (pin "1") (pinfunction "P_1") (pintype "passive"))
    )
    (net (code "271") (name "unconnected-(U$295-P-Pad1)") (class "Default")
      (node (ref "U$295") (pin "1") (pinfunction "P_1") (pintype "passive"))
    )
    (net (code "272") (name "unconnected-(U$296-P-Pad1)") (class "Default")
      (node (ref "U$296") (pin "1") (pinfunction "P_1") (pintype "passive"))
    )
    (net (code "273") (name "unconnected-(U$297-P-Pad1)") (class "Default")
      (node (ref "U$297") (pin "1") (pinfunction "P_1") (pintype "passive"))
    )
    (net (code "274") (name "unconnected-(U$298-P-Pad1)") (class "Default")
      (node (ref "U$298") (pin "1") (pinfunction "P_1") (pintype "passive"))
    )
    (net (code "275") (name "unconnected-(U$299-P-Pad1)") (class "Default")
      (node (ref "U$299") (pin "1") (pinfunction "P_1") (pintype "passive"))
    )
    (net (code "276") (name "unconnected-(U$300-P-Pad1)") (class "Default")
      (node (ref "U$300") (pin "1") (pinfunction "P_1") (pintype "passive"))
    )
    (net (code "277") (name "unconnected-(U$301-P-Pad1)") (class "Default")
      (node (ref "U$301") (pin "1") (pinfunction "P_1") (pintype "passive"))
    )
    (net (code "278") (name "unconnected-(U$302-P-Pad1)") (class "Default")
      (node (ref "U$302") (pin "1") (pinfunction "P_1") (pintype "passive"))
    )
    (net (code "279") (name "unconnected-(U$303-P-Pad1)") (class "Default")
      (node (ref "U$303") (pin "1") (pinfunction "P_1") (pintype "passive"))
    )
    (net (code "280") (name "unconnected-(U$304-P-Pad1)") (class "Default")
      (node (ref "U$304") (pin "1") (pinfunction "P_1") (pintype "passive"))
    )
    (net (code "281") (name "unconnected-(U$305-P-Pad1)") (class "Default")
      (node (ref "U$305") (pin "1") (pinfunction "P_1") (pintype "passive"))
    )
    (net (code "282") (name "unconnected-(U$306-P-Pad1)") (class "Default")
      (node (ref "U$306") (pin "1") (pinfunction "P_1") (pintype "passive"))
    )
    (net (code "283") (name "unconnected-(U$307-P-Pad1)") (class "Default")
      (node (ref "U$307") (pin "1") (pinfunction "P_1") (pintype "passive"))
    )
    (net (code "284") (name "unconnected-(U$308-P-Pad1)") (class "Default")
      (node (ref "U$308") (pin "1") (pinfunction "P_1") (pintype "passive"))
    )
    (net (code "285") (name "unconnected-(U$309-P-Pad1)") (class "Default")
      (node (ref "U$309") (pin "1") (pinfunction "P_1") (pintype "passive"))
    )
    (net (code "286") (name "unconnected-(U$310-P-Pad1)") (class "Default")
      (node (ref "U$310") (pin "1") (pinfunction "P_1") (pintype "passive"))
    )
    (net (code "287") (name "unconnected-(U$311-P-Pad1)") (class "Default")
      (node (ref "U$311") (pin "1") (pinfunction "P_1") (pintype "passive"))
    )
    (net (code "288") (name "unconnected-(U$312-P-Pad1)") (class "Default")
      (node (ref "U$312") (pin "1") (pinfunction "P_1") (pintype "passive"))
    )
    (net (code "289") (name "unconnected-(U$313-P-Pad1)") (class "Default")
      (node (ref "U$313") (pin "1") (pinfunction "P_1") (pintype "passive"))
    )
    (net (code "290") (name "unconnected-(U$314-P-Pad1)") (class "Default")
      (node (ref "U$314") (pin "1") (pinfunction "P_1") (pintype "passive"))
    )
    (net (code "291") (name "unconnected-(U$337-P-Pad1)") (class "Default")
      (node (ref "U$337") (pin "1") (pinfunction "P_1") (pintype "passive"))
    )
    (net (code "292") (name "unconnected-(U$338-P-Pad1)") (class "Default")
      (node (ref "U$338") (pin "1") (pinfunction "P_1") (pintype "passive"))
    )
    (net (code "293") (name "unconnected-(U$339-P-Pad1)") (class "Default")
      (node (ref "U$339") (pin "1") (pinfunction "P_1") (pintype "passive"))
    )
    (net (code "294") (name "unconnected-(U$340-P-Pad1)") (class "Default")
      (node (ref "U$340") (pin "1") (pinfunction "P_1") (pintype "passive"))
    )
    (net (code "295") (name "unconnected-(U$341-P-Pad1)") (class "Default")
      (node (ref "U$341") (pin "1") (pinfunction "P_1") (pintype "passive"))
    )
    (net (code "296") (name "unconnected-(U$342-P-Pad1)") (class "Default")
      (node (ref "U$342") (pin "1") (pinfunction "P_1") (pintype "passive"))
    )
    (net (code "297") (name "unconnected-(U$343-P-Pad1)") (class "Default")
      (node (ref "U$343") (pin "1") (pinfunction "P_1") (pintype "passive"))
    )
    (net (code "298") (name "unconnected-(U$344-P-Pad1)") (class "Default")
      (node (ref "U$344") (pin "1") (pinfunction "P_1") (pintype "passive"))
    )
    (net (code "299") (name "unconnected-(U$345-P-Pad1)") (class "Default")
      (node (ref "U$345") (pin "1") (pinfunction "P_1") (pintype "passive"))
    )
    (net (code "300") (name "unconnected-(U$346-P-Pad1)") (class "Default")
      (node (ref "U$346") (pin "1") (pinfunction "P_1") (pintype "passive"))
    )
    (net (code "301") (name "unconnected-(U$347-P-Pad1)") (class "Default")
      (node (ref "U$347") (pin "1") (pinfunction "P_1") (pintype "passive"))
    )
    (net (code "302") (name "unconnected-(U$348-P-Pad1)") (class "Default")
      (node (ref "U$348") (pin "1") (pinfunction "P_1") (pintype "passive"))
    )
    (net (code "303") (name "unconnected-(U$349-P-Pad1)") (class "Default")
      (node (ref "U$349") (pin "1") (pinfunction "P_1") (pintype "passive"))
    )
    (net (code "304") (name "unconnected-(U$350-P-Pad1)") (class "Default")
      (node (ref "U$350") (pin "1") (pinfunction "P_1") (pintype "passive"))
    )
    (net (code "305") (name "unconnected-(U$351-P-Pad1)") (class "Default")
      (node (ref "U$351") (pin "1") (pinfunction "P_1") (pintype "passive"))
    )
    (net (code "306") (name "unconnected-(U$352-P-Pad1)") (class "Default")
      (node (ref "U$352") (pin "1") (pinfunction "P_1") (pintype "passive"))
    )
    (net (code "307") (name "unconnected-(U$353-P-Pad1)") (class "Default")
      (node (ref "U$353") (pin "1") (pinfunction "P_1") (pintype "passive"))
    )
    (net (code "308") (name "unconnected-(U$354-P-Pad1)") (class "Default")
      (node (ref "U$354") (pin "1") (pinfunction "P_1") (pintype "passive"))
    )
    (net (code "309") (name "unconnected-(U$355-P-Pad1)") (class "Default")
      (node (ref "U$355") (pin "1") (pinfunction "P_1") (pintype "passive"))
    )
    (net (code "310") (name "unconnected-(U$356-P-Pad1)") (class "Default")
      (node (ref "U$356") (pin "1") (pinfunction "P_1") (pintype "passive"))
    )
    (net (code "311") (name "unconnected-(U$357-P-Pad1)") (class "Default")
      (node (ref "U$357") (pin "1") (pinfunction "P_1") (pintype "passive"))
    )
    (net (code "312") (name "unconnected-(U$358-P-Pad1)") (class "Default")
      (node (ref "U$358") (pin "1") (pinfunction "P_1") (pintype "passive"))
    )
    (net (code "313") (name "unconnected-(U$359-P-Pad1)") (class "Default")
      (node (ref "U$359") (pin "1") (pinfunction "P_1") (pintype "passive"))
    )
    (net (code "314") (name "unconnected-(U$360-P-Pad1)") (class "Default")
      (node (ref "U$360") (pin "1") (pinfunction "P_1") (pintype "passive"))
    )
    (net (code "315") (name "unconnected-(U$361-P-Pad1)") (class "Default")
      (node (ref "U$361") (pin "1") (pinfunction "P_1") (pintype "passive"))
    )
    (net (code "316") (name "unconnected-(U$362-P-Pad1)") (class "Default")
      (node (ref "U$362") (pin "1") (pinfunction "P_1") (pintype "passive"))
    )
    (net (code "317") (name "unconnected-(U$363-P-Pad1)") (class "Default")
      (node (ref "U$363") (pin "1") (pinfunction "P_1") (pintype "passive"))
    )
    (net (code "318") (name "unconnected-(U$364-P-Pad1)") (class "Default")
      (node (ref "U$364") (pin "1") (pinfunction "P_1") (pintype "passive"))
    )
    (net (code "319") (name "unconnected-(U$365-P-Pad1)") (class "Default")
      (node (ref "U$365") (pin "1") (pinfunction "P_1") (pintype "passive"))
    )
    (net (code "320") (name "unconnected-(U$366-P-Pad1)") (class "Default")
      (node (ref "U$366") (pin "1") (pinfunction "P_1") (pintype "passive"))
    )
    (net (code "321") (name "unconnected-(U$367-P-Pad1)") (class "Default")
      (node (ref "U$367") (pin "1") (pinfunction "P_1") (pintype "passive"))
    )
    (net (code "322") (name "unconnected-(U$368-P-Pad1)") (class "Default")
      (node (ref "U$368") (pin "1") (pinfunction "P_1") (pintype "passive"))
    )
    (net (code "323") (name "unconnected-(U$369-P-Pad1)") (class "Default")
      (node (ref "U$369") (pin "1") (pinfunction "P_1") (pintype "passive"))
    )
    (net (code "324") (name "unconnected-(U$370-P-Pad1)") (class "Default")
      (node (ref "U$370") (pin "1") (pinfunction "P_1") (pintype "passive"))
    )
    (net (code "325") (name "unconnected-(U$371-P-Pad1)") (class "Default")
      (node (ref "U$371") (pin "1") (pinfunction "P_1") (pintype "passive"))
    )
    (net (code "326") (name "unconnected-(U$372-P-Pad1)") (class "Default")
      (node (ref "U$372") (pin "1") (pinfunction "P_1") (pintype "passive"))
    )
    (net (code "327") (name "unconnected-(U$373-P-Pad1)") (class "Default")
      (node (ref "U$373") (pin "1") (pinfunction "P_1") (pintype "passive"))
    )
    (net (code "328") (name "unconnected-(U$374-P-Pad1)") (class "Default")
      (node (ref "U$374") (pin "1") (pinfunction "P_1") (pintype "passive"))
    )
    (net (code "329") (name "unconnected-(U$375-P-Pad1)") (class "Default")
      (node (ref "U$375") (pin "1") (pinfunction "P_1") (pintype "passive"))
    )
    (net (code "330") (name "unconnected-(U$376-P-Pad1)") (class "Default")
      (node (ref "U$376") (pin "1") (pinfunction "P_1") (pintype "passive"))
    )
    (net (code "331") (name "unconnected-(U$377-P-Pad1)") (class "Default")
      (node (ref "U$377") (pin "1") (pinfunction "P_1") (pintype "passive"))
    )
    (net (code "332") (name "unconnected-(U$378-P-Pad1)") (class "Default")
      (node (ref "U$378") (pin "1") (pinfunction "P_1") (pintype "passive"))
    )
    (net (code "333") (name "unconnected-(U$379-P-Pad1)") (class "Default")
      (node (ref "U$379") (pin "1") (pinfunction "P_1") (pintype "passive"))
    )
    (net (code "334") (name "unconnected-(U$380-P-Pad1)") (class "Default")
      (node (ref "U$380") (pin "1") (pinfunction "P_1") (pintype "passive"))
    )
    (net (code "335") (name "unconnected-(U$381-P-Pad1)") (class "Default")
      (node (ref "U$381") (pin "1") (pinfunction "P_1") (pintype "passive"))
    )
    (net (code "336") (name "unconnected-(U$382-P-Pad1)") (class "Default")
      (node (ref "U$382") (pin "1") (pinfunction "P_1") (pintype "passive"))
    )
    (net (code "337") (name "unconnected-(U$383-P-Pad1)") (class "Default")
      (node (ref "U$383") (pin "1") (pinfunction "P_1") (pintype "passive"))
    )
    (net (code "338") (name "unconnected-(U$384-P-Pad1)") (class "Default")
      (node (ref "U$384") (pin "1") (pinfunction "P_1") (pintype "passive"))
    )
    (net (code "339") (name "unconnected-(U$385-P-Pad1)") (class "Default")
      (node (ref "U$385") (pin "1") (pinfunction "P_1") (pintype "passive"))
    )
    (net (code "340") (name "unconnected-(U$386-P-Pad1)") (class "Default")
      (node (ref "U$386") (pin "1") (pinfunction "P_1") (pintype "passive"))
    )
    (net (code "341") (name "unconnected-(U$387-P-Pad1)") (class "Default")
      (node (ref "U$387") (pin "1") (pinfunction "P_1") (pintype "passive"))
    )
    (net (code "342") (name "unconnected-(U$388-P-Pad1)") (class "Default")
      (node (ref "U$388") (pin "1") (pinfunction "P_1") (pintype "passive"))
    )
    (net (code "343") (name "unconnected-(U$389-P-Pad1)") (class "Default")
      (node (ref "U$389") (pin "1") (pinfunction "P_1") (pintype "passive"))
    )
    (net (code "344") (name "unconnected-(U$390-P-Pad1)") (class "Default")
      (node (ref "U$390") (pin "1") (pinfunction "P_1") (pintype "passive"))
    )
    (net (code "345") (name "unconnected-(U$391-P-Pad1)") (class "Default")
      (node (ref "U$391") (pin "1") (pinfunction "P_1") (pintype "passive"))
    )
    (net (code "346") (name "unconnected-(U$392-P-Pad1)") (class "Default")
      (node (ref "U$392") (pin "1") (pinfunction "P_1") (pintype "passive"))
    )
    (net (code "347") (name "unconnected-(U$393-P-Pad1)") (class "Default")
      (node (ref "U$393") (pin "1") (pinfunction "P_1") (pintype "passive"))
    )
    (net (code "348") (name "unconnected-(U$394-P-Pad1)") (class "Default")
      (node (ref "U$394") (pin "1") (pinfunction "P_1") (pintype "passive"))
    )
    (net (code "349") (name "unconnected-(U$395-P-Pad1)") (class "Default")
      (node (ref "U$395") (pin "1") (pinfunction "P_1") (pintype "passive"))
    )
    (net (code "350") (name "unconnected-(U$396-P-Pad1)") (class "Default")
      (node (ref "U$396") (pin "1") (pinfunction "P_1") (pintype "passive"))
    )
    (net (code "351") (name "unconnected-(U$397-P-Pad1)") (class "Default")
      (node (ref "U$397") (pin "1") (pinfunction "P_1") (pintype "passive"))
    )
    (net (code "352") (name "unconnected-(U$398-P-Pad1)") (class "Default")
      (node (ref "U$398") (pin "1") (pinfunction "P_1") (pintype "passive"))
    )
    (net (code "353") (name "unconnected-(U$399-P-Pad1)") (class "Default")
      (node (ref "U$399") (pin "1") (pinfunction "P_1") (pintype "passive"))
    )
    (net (code "354") (name "unconnected-(U$400-P-Pad1)") (class "Default")
      (node (ref "U$400") (pin "1") (pinfunction "P_1") (pintype "passive"))
    )
    (net (code "355") (name "unconnected-(U$401-P-Pad1)") (class "Default")
      (node (ref "U$401") (pin "1") (pinfunction "P_1") (pintype "passive"))
    )
    (net (code "356") (name "unconnected-(U$402-P-Pad1)") (class "Default")
      (node (ref "U$402") (pin "1") (pinfunction "P_1") (pintype "passive"))
    )
    (net (code "357") (name "unconnected-(U$403-P-Pad1)") (class "Default")
      (node (ref "U$403") (pin "1") (pinfunction "P_1") (pintype "passive"))
    )
    (net (code "358") (name "unconnected-(U$404-P-Pad1)") (class "Default")
      (node (ref "U$404") (pin "1") (pinfunction "P_1") (pintype "passive"))
    )
    (net (code "359") (name "unconnected-(U$405-P-Pad1)") (class "Default")
      (node (ref "U$405") (pin "1") (pinfunction "P_1") (pintype "passive"))
    )
    (net (code "360") (name "unconnected-(U$406-P-Pad1)") (class "Default")
      (node (ref "U$406") (pin "1") (pinfunction "P_1") (pintype "passive"))
    )
    (net (code "361") (name "unconnected-(U$407-P-Pad1)") (class "Default")
      (node (ref "U$407") (pin "1") (pinfunction "P_1") (pintype "passive"))
    )
    (net (code "362") (name "unconnected-(U$408-P-Pad1)") (class "Default")
      (node (ref "U$408") (pin "1") (pinfunction "P_1") (pintype "passive"))
    )
    (net (code "363") (name "unconnected-(U$409-P-Pad1)") (class "Default")
      (node (ref "U$409") (pin "1") (pinfunction "P_1") (pintype "passive"))
    )
    (net (code "364") (name "unconnected-(U$410-P-Pad1)") (class "Default")
      (node (ref "U$410") (pin "1") (pinfunction "P_1") (pintype "passive"))
    )
    (net (code "365") (name "unconnected-(U$411-P-Pad1)") (class "Default")
      (node (ref "U$411") (pin "1") (pinfunction "P_1") (pintype "passive"))
    )
    (net (code "366") (name "unconnected-(U$412-P-Pad1)") (class "Default")
      (node (ref "U$412") (pin "1") (pinfunction "P_1") (pintype "passive"))
    )
    (net (code "367") (name "unconnected-(U$413-P-Pad1)") (class "Default")
      (node (ref "U$413") (pin "1") (pinfunction "P_1") (pintype "passive"))
    )
    (net (code "368") (name "unconnected-(U$414-P-Pad1)") (class "Default")
      (node (ref "U$414") (pin "1") (pinfunction "P_1") (pintype "passive"))
    )
    (net (code "369") (name "unconnected-(U$415-P-Pad1)") (class "Default")
      (node (ref "U$415") (pin "1") (pinfunction "P_1") (pintype "passive"))
    )
    (net (code "370") (name "unconnected-(U$416-P-Pad1)") (class "Default")
      (node (ref "U$416") (pin "1") (pinfunction "P_1") (pintype "passive"))
    )
    (net (code "371") (name "unconnected-(U$417-P-Pad1)") (class "Default")
      (node (ref "U$417") (pin "1") (pinfunction "P_1") (pintype "passive"))
    )
    (net (code "372") (name "unconnected-(U$418-P-Pad1)") (class "Default")
      (node (ref "U$418") (pin "1") (pinfunction "P_1") (pintype "passive"))
    )
    (net (code "373") (name "unconnected-(U$419-P-Pad1)") (class "Default")
      (node (ref "U$419") (pin "1") (pinfunction "P_1") (pintype "passive"))
    )
    (net (code "374") (name "unconnected-(U$420-P-Pad1)") (class "Default")
      (node (ref "U$420") (pin "1") (pinfunction "P_1") (pintype "passive"))
    )
    (net (code "375") (name "unconnected-(U$421-P-Pad1)") (class "Default")
      (node (ref "U$421") (pin "1") (pinfunction "P_1") (pintype "passive"))
    )
    (net (code "376") (name "unconnected-(U$422-P-Pad1)") (class "Default")
      (node (ref "U$422") (pin "1") (pinfunction "P_1") (pintype "passive"))
    )
    (net (code "377") (name "unconnected-(U$423-P-Pad1)") (class "Default")
      (node (ref "U$423") (pin "1") (pinfunction "P_1") (pintype "passive"))
    )
    (net (code "378") (name "unconnected-(U$424-P-Pad1)") (class "Default")
      (node (ref "U$424") (pin "1") (pinfunction "P_1") (pintype "passive"))
    )
    (net (code "379") (name "unconnected-(U$425-P-Pad1)") (class "Default")
      (node (ref "U$425") (pin "1") (pinfunction "P_1") (pintype "passive"))
    )
    (net (code "380") (name "unconnected-(U$426-P-Pad1)") (class "Default")
      (node (ref "U$426") (pin "1") (pinfunction "P_1") (pintype "passive"))
    )
    (net (code "381") (name "unconnected-(U$427-P-Pad1)") (class "Default")
      (node (ref "U$427") (pin "1") (pinfunction "P_1") (pintype "passive"))
    )
    (net (code "382") (name "unconnected-(U$428-P-Pad1)") (class "Default")
      (node (ref "U$428") (pin "1") (pinfunction "P_1") (pintype "passive"))
    )
    (net (code "383") (name "unconnected-(U$429-P-Pad1)") (class "Default")
      (node (ref "U$429") (pin "1") (pinfunction "P_1") (pintype "passive"))
    )
    (net (code "384") (name "unconnected-(U$430-P-Pad1)") (class "Default")
      (node (ref "U$430") (pin "1") (pinfunction "P_1") (pintype "passive"))
    )
    (net (code "385") (name "unconnected-(U$431-P-Pad1)") (class "Default")
      (node (ref "U$431") (pin "1") (pinfunction "P_1") (pintype "passive"))
    )
    (net (code "386") (name "unconnected-(U$432-P-Pad1)") (class "Default")
      (node (ref "U$432") (pin "1") (pinfunction "P_1") (pintype "passive"))
    )
    (net (code "387") (name "unconnected-(U$433-P-Pad1)") (class "Default")
      (node (ref "U$433") (pin "1") (pinfunction "P_1") (pintype "passive"))
    )
    (net (code "388") (name "unconnected-(U$434-P-Pad1)") (class "Default")
      (node (ref "U$434") (pin "1") (pinfunction "P_1") (pintype "passive"))
    )
    (net (code "389") (name "unconnected-(U$435-P-Pad1)") (class "Default")
      (node (ref "U$435") (pin "1") (pinfunction "P_1") (pintype "passive"))
    )
    (net (code "390") (name "unconnected-(U$436-P-Pad1)") (class "Default")
      (node (ref "U$436") (pin "1") (pinfunction "P_1") (pintype "passive"))
    )
    (net (code "391") (name "unconnected-(U$459-P-Pad1)") (class "Default")
      (node (ref "U$459") (pin "1") (pinfunction "P_1") (pintype "passive"))
    )
    (net (code "392") (name "unconnected-(U$460-P-Pad1)") (class "Default")
      (node (ref "U$460") (pin "1") (pinfunction "P_1") (pintype "passive"))
    )
    (net (code "393") (name "unconnected-(U$461-P-Pad1)") (class "Default")
      (node (ref "U$461") (pin "1") (pinfunction "P_1") (pintype "passive"))
    )
    (net (code "394") (name "unconnected-(U$462-P-Pad1)") (class "Default")
      (node (ref "U$462") (pin "1") (pinfunction "P_1") (pintype "passive"))
    )
    (net (code "395") (name "unconnected-(U$463-P-Pad1)") (class "Default")
      (node (ref "U$463") (pin "1") (pinfunction "P_1") (pintype "passive"))
    )
    (net (code "396") (name "unconnected-(U$464-P-Pad1)") (class "Default")
      (node (ref "U$464") (pin "1") (pinfunction "P_1") (pintype "passive"))
    )
    (net (code "397") (name "unconnected-(U$465-P-Pad1)") (class "Default")
      (node (ref "U$465") (pin "1") (pinfunction "P_1") (pintype "passive"))
    )
    (net (code "398") (name "unconnected-(U$466-P-Pad1)") (class "Default")
      (node (ref "U$466") (pin "1") (pinfunction "P_1") (pintype "passive"))
    )
    (net (code "399") (name "unconnected-(U$467-P-Pad1)") (class "Default")
      (node (ref "U$467") (pin "1") (pinfunction "P_1") (pintype "passive"))
    )
    (net (code "400") (name "unconnected-(U$468-P-Pad1)") (class "Default")
      (node (ref "U$468") (pin "1") (pinfunction "P_1") (pintype "passive"))
    )
    (net (code "401") (name "unconnected-(U$469-P-Pad1)") (class "Default")
      (node (ref "U$469") (pin "1") (pinfunction "P_1") (pintype "passive"))
    )
    (net (code "402") (name "unconnected-(U$470-P-Pad1)") (class "Default")
      (node (ref "U$470") (pin "1") (pinfunction "P_1") (pintype "passive"))
    )
    (net (code "403") (name "unconnected-(U$471-P-Pad1)") (class "Default")
      (node (ref "U$471") (pin "1") (pinfunction "P_1") (pintype "passive"))
    )
    (net (code "404") (name "unconnected-(U$472-P-Pad1)") (class "Default")
      (node (ref "U$472") (pin "1") (pinfunction "P_1") (pintype "passive"))
    )
    (net (code "405") (name "unconnected-(U$473-P-Pad1)") (class "Default")
      (node (ref "U$473") (pin "1") (pinfunction "P_1") (pintype "passive"))
    )
    (net (code "406") (name "unconnected-(U$474-P-Pad1)") (class "Default")
      (node (ref "U$474") (pin "1") (pinfunction "P_1") (pintype "passive"))
    )
    (net (code "407") (name "unconnected-(U$475-P-Pad1)") (class "Default")
      (node (ref "U$475") (pin "1") (pinfunction "P_1") (pintype "passive"))
    )
    (net (code "408") (name "unconnected-(U$476-P-Pad1)") (class "Default")
      (node (ref "U$476") (pin "1") (pinfunction "P_1") (pintype "passive"))
    )
    (net (code "409") (name "unconnected-(U$477-P-Pad1)") (class "Default")
      (node (ref "U$477") (pin "1") (pinfunction "P_1") (pintype "passive"))
    )
    (net (code "410") (name "unconnected-(U$478-P-Pad1)") (class "Default")
      (node (ref "U$478") (pin "1") (pinfunction "P_1") (pintype "passive"))
    )
    (net (code "411") (name "unconnected-(U$479-P-Pad1)") (class "Default")
      (node (ref "U$479") (pin "1") (pinfunction "P_1") (pintype "passive"))
    )
    (net (code "412") (name "unconnected-(U$480-P-Pad1)") (class "Default")
      (node (ref "U$480") (pin "1") (pinfunction "P_1") (pintype "passive"))
    )
    (net (code "413") (name "unconnected-(U$481-P-Pad1)") (class "Default")
      (node (ref "U$481") (pin "1") (pinfunction "P_1") (pintype "passive"))
    )
    (net (code "414") (name "unconnected-(U$482-P-Pad1)") (class "Default")
      (node (ref "U$482") (pin "1") (pinfunction "P_1") (pintype "passive"))
    )
    (net (code "415") (name "unconnected-(U$483-P-Pad1)") (class "Default")
      (node (ref "U$483") (pin "1") (pinfunction "P_1") (pintype "passive"))
    )
    (net (code "416") (name "unconnected-(U$484-P-Pad1)") (class "Default")
      (node (ref "U$484") (pin "1") (pinfunction "P_1") (pintype "passive"))
    )
    (net (code "417") (name "unconnected-(U$485-P-Pad1)") (class "Default")
      (node (ref "U$485") (pin "1") (pinfunction "P_1") (pintype "passive"))
    )
    (net (code "418") (name "unconnected-(U$486-P-Pad1)") (class "Default")
      (node (ref "U$486") (pin "1") (pinfunction "P_1") (pintype "passive"))
    )
    (net (code "419") (name "unconnected-(U$487-P-Pad1)") (class "Default")
      (node (ref "U$487") (pin "1") (pinfunction "P_1") (pintype "passive"))
    )
    (net (code "420") (name "unconnected-(U$488-P-Pad1)") (class "Default")
      (node (ref "U$488") (pin "1") (pinfunction "P_1") (pintype "passive"))
    )
    (net (code "421") (name "unconnected-(U$489-P-Pad1)") (class "Default")
      (node (ref "U$489") (pin "1") (pinfunction "P_1") (pintype "passive"))
    )
    (net (code "422") (name "unconnected-(U$490-P-Pad1)") (class "Default")
      (node (ref "U$490") (pin "1") (pinfunction "P_1") (pintype "passive"))
    )
    (net (code "423") (name "unconnected-(U$491-P-Pad1)") (class "Default")
      (node (ref "U$491") (pin "1") (pinfunction "P_1") (pintype "passive"))
    )
    (net (code "424") (name "unconnected-(U$492-P-Pad1)") (class "Default")
      (node (ref "U$492") (pin "1") (pinfunction "P_1") (pintype "passive"))
    )
    (net (code "425") (name "unconnected-(U$493-P-Pad1)") (class "Default")
      (node (ref "U$493") (pin "1") (pinfunction "P_1") (pintype "passive"))
    )
    (net (code "426") (name "unconnected-(U$494-P-Pad1)") (class "Default")
      (node (ref "U$494") (pin "1") (pinfunction "P_1") (pintype "passive"))
    )
    (net (code "427") (name "unconnected-(U$495-P-Pad1)") (class "Default")
      (node (ref "U$495") (pin "1") (pinfunction "P_1") (pintype "passive"))
    )
    (net (code "428") (name "unconnected-(U$496-P-Pad1)") (class "Default")
      (node (ref "U$496") (pin "1") (pinfunction "P_1") (pintype "passive"))
    )
    (net (code "429") (name "unconnected-(U$497-P-Pad1)") (class "Default")
      (node (ref "U$497") (pin "1") (pinfunction "P_1") (pintype "passive"))
    )
    (net (code "430") (name "unconnected-(U$498-P-Pad1)") (class "Default")
      (node (ref "U$498") (pin "1") (pinfunction "P_1") (pintype "passive"))
    )
    (net (code "431") (name "unconnected-(U$499-P-Pad1)") (class "Default")
      (node (ref "U$499") (pin "1") (pinfunction "P_1") (pintype "passive"))
    )
    (net (code "432") (name "unconnected-(U$500-P-Pad1)") (class "Default")
      (node (ref "U$500") (pin "1") (pinfunction "P_1") (pintype "passive"))
    )
    (net (code "433") (name "unconnected-(U$501-P-Pad1)") (class "Default")
      (node (ref "U$501") (pin "1") (pinfunction "P_1") (pintype "passive"))
    )
    (net (code "434") (name "unconnected-(U$502-P-Pad1)") (class "Default")
      (node (ref "U$502") (pin "1") (pinfunction "P_1") (pintype "passive"))
    )
    (net (code "435") (name "unconnected-(U$503-P-Pad1)") (class "Default")
      (node (ref "U$503") (pin "1") (pinfunction "P_1") (pintype "passive"))
    )
    (net (code "436") (name "unconnected-(U$504-P-Pad1)") (class "Default")
      (node (ref "U$504") (pin "1") (pinfunction "P_1") (pintype "passive"))
    )
    (net (code "437") (name "unconnected-(U$505-P-Pad1)") (class "Default")
      (node (ref "U$505") (pin "1") (pinfunction "P_1") (pintype "passive"))
    )
    (net (code "438") (name "unconnected-(U$506-P-Pad1)") (class "Default")
      (node (ref "U$506") (pin "1") (pinfunction "P_1") (pintype "passive"))
    )
    (net (code "439") (name "unconnected-(U$507-P-Pad1)") (class "Default")
      (node (ref "U$507") (pin "1") (pinfunction "P_1") (pintype "passive"))
    )
    (net (code "440") (name "unconnected-(U$508-P-Pad1)") (class "Default")
      (node (ref "U$508") (pin "1") (pinfunction "P_1") (pintype "passive"))
    )
    (net (code "441") (name "unconnected-(U$509-P-Pad1)") (class "Default")
      (node (ref "U$509") (pin "1") (pinfunction "P_1") (pintype "passive"))
    )
    (net (code "442") (name "unconnected-(U$510-P-Pad1)") (class "Default")
      (node (ref "U$510") (pin "1") (pinfunction "P_1") (pintype "passive"))
    )
    (net (code "443") (name "unconnected-(U$511-P-Pad1)") (class "Default")
      (node (ref "U$511") (pin "1") (pinfunction "P_1") (pintype "passive"))
    )
    (net (code "444") (name "unconnected-(U$512-P-Pad1)") (class "Default")
      (node (ref "U$512") (pin "1") (pinfunction "P_1") (pintype "passive"))
    )
    (net (code "445") (name "unconnected-(U$513-P-Pad1)") (class "Default")
      (node (ref "U$513") (pin "1") (pinfunction "P_1") (pintype "passive"))
    )
    (net (code "446") (name "unconnected-(U$514-P-Pad1)") (class "Default")
      (node (ref "U$514") (pin "1") (pinfunction "P_1") (pintype "passive"))
    )
    (net (code "447") (name "unconnected-(U$515-P-Pad1)") (class "Default")
      (node (ref "U$515") (pin "1") (pinfunction "P_1") (pintype "passive"))
    )
    (net (code "448") (name "unconnected-(U$516-P-Pad1)") (class "Default")
      (node (ref "U$516") (pin "1") (pinfunction "P_1") (pintype "passive"))
    )
    (net (code "449") (name "unconnected-(U$517-P-Pad1)") (class "Default")
      (node (ref "U$517") (pin "1") (pinfunction "P_1") (pintype "passive"))
    )
    (net (code "450") (name "unconnected-(U$518-P-Pad1)") (class "Default")
      (node (ref "U$518") (pin "1") (pinfunction "P_1") (pintype "passive"))
    )
    (net (code "451") (name "unconnected-(U$519-P-Pad1)") (class "Default")
      (node (ref "U$519") (pin "1") (pinfunction "P_1") (pintype "passive"))
    )
    (net (code "452") (name "unconnected-(U$520-P-Pad1)") (class "Default")
      (node (ref "U$520") (pin "1") (pinfunction "P_1") (pintype "passive"))
    )
    (net (code "453") (name "unconnected-(U$521-P-Pad1)") (class "Default")
      (node (ref "U$521") (pin "1") (pinfunction "P_1") (pintype "passive"))
    )
    (net (code "454") (name "unconnected-(U$522-P-Pad1)") (class "Default")
      (node (ref "U$522") (pin "1") (pinfunction "P_1") (pintype "passive"))
    )
    (net (code "455") (name "unconnected-(U$523-P-Pad1)") (class "Default")
      (node (ref "U$523") (pin "1") (pinfunction "P_1") (pintype "passive"))
    )
    (net (code "456") (name "unconnected-(U$524-P-Pad1)") (class "Default")
      (node (ref "U$524") (pin "1") (pinfunction "P_1") (pintype "passive"))
    )
    (net (code "457") (name "unconnected-(U$525-P-Pad1)") (class "Default")
      (node (ref "U$525") (pin "1") (pinfunction "P_1") (pintype "passive"))
    )
    (net (code "458") (name "unconnected-(U$526-P-Pad1)") (class "Default")
      (node (ref "U$526") (pin "1") (pinfunction "P_1") (pintype "passive"))
    )
    (net (code "459") (name "unconnected-(U$527-P-Pad1)") (class "Default")
      (node (ref "U$527") (pin "1") (pinfunction "P_1") (pintype "passive"))
    )
    (net (code "460") (name "unconnected-(U$528-P-Pad1)") (class "Default")
      (node (ref "U$528") (pin "1") (pinfunction "P_1") (pintype "passive"))
    )
    (net (code "461") (name "unconnected-(U$529-P-Pad1)") (class "Default")
      (node (ref "U$529") (pin "1") (pinfunction "P_1") (pintype "passive"))
    )
    (net (code "462") (name "unconnected-(U$530-P-Pad1)") (class "Default")
      (node (ref "U$530") (pin "1") (pinfunction "P_1") (pintype "passive"))
    )
    (net (code "463") (name "unconnected-(U$531-P-Pad1)") (class "Default")
      (node (ref "U$531") (pin "1") (pinfunction "P_1") (pintype "passive"))
    )
    (net (code "464") (name "unconnected-(U$532-P-Pad1)") (class "Default")
      (node (ref "U$532") (pin "1") (pinfunction "P_1") (pintype "passive"))
    )
    (net (code "465") (name "unconnected-(U$533-P-Pad1)") (class "Default")
      (node (ref "U$533") (pin "1") (pinfunction "P_1") (pintype "passive"))
    )
    (net (code "466") (name "unconnected-(U$534-P-Pad1)") (class "Default")
      (node (ref "U$534") (pin "1") (pinfunction "P_1") (pintype "passive"))
    )
    (net (code "467") (name "unconnected-(U$535-P-Pad1)") (class "Default")
      (node (ref "U$535") (pin "1") (pinfunction "P_1") (pintype "passive"))
    )
    (net (code "468") (name "unconnected-(U$536-P-Pad1)") (class "Default")
      (node (ref "U$536") (pin "1") (pinfunction "P_1") (pintype "passive"))
    )
    (net (code "469") (name "unconnected-(U$537-P-Pad1)") (class "Default")
      (node (ref "U$537") (pin "1") (pinfunction "P_1") (pintype "passive"))
    )
    (net (code "470") (name "unconnected-(U$538-P-Pad1)") (class "Default")
      (node (ref "U$538") (pin "1") (pinfunction "P_1") (pintype "passive"))
    )
    (net (code "471") (name "unconnected-(U$539-P-Pad1)") (class "Default")
      (node (ref "U$539") (pin "1") (pinfunction "P_1") (pintype "passive"))
    )
    (net (code "472") (name "unconnected-(U$540-P-Pad1)") (class "Default")
      (node (ref "U$540") (pin "1") (pinfunction "P_1") (pintype "passive"))
    )
    (net (code "473") (name "unconnected-(U$541-P-Pad1)") (class "Default")
      (node (ref "U$541") (pin "1") (pinfunction "P_1") (pintype "passive"))
    )
    (net (code "474") (name "unconnected-(U$542-P-Pad1)") (class "Default")
      (node (ref "U$542") (pin "1") (pinfunction "P_1") (pintype "passive"))
    )
    (net (code "475") (name "unconnected-(U$543-P-Pad1)") (class "Default")
      (node (ref "U$543") (pin "1") (pinfunction "P_1") (pintype "passive"))
    )
    (net (code "476") (name "unconnected-(U$544-P-Pad1)") (class "Default")
      (node (ref "U$544") (pin "1") (pinfunction "P_1") (pintype "passive"))
    )
    (net (code "477") (name "unconnected-(U$545-P-Pad1)") (class "Default")
      (node (ref "U$545") (pin "1") (pinfunction "P_1") (pintype "passive"))
    )
    (net (code "478") (name "unconnected-(U$546-P-Pad1)") (class "Default")
      (node (ref "U$546") (pin "1") (pinfunction "P_1") (pintype "passive"))
    )
    (net (code "479") (name "unconnected-(U$547-P-Pad1)") (class "Default")
      (node (ref "U$547") (pin "1") (pinfunction "P_1") (pintype "passive"))
    )
    (net (code "480") (name "unconnected-(U$548-P-Pad1)") (class "Default")
      (node (ref "U$548") (pin "1") (pinfunction "P_1") (pintype "passive"))
    )
    (net (code "481") (name "unconnected-(U$549-P-Pad1)") (class "Default")
      (node (ref "U$549") (pin "1") (pinfunction "P_1") (pintype "passive"))
    )
    (net (code "482") (name "unconnected-(U$550-P-Pad1)") (class "Default")
      (node (ref "U$550") (pin "1") (pinfunction "P_1") (pintype "passive"))
    )
    (net (code "483") (name "unconnected-(U$551-P-Pad1)") (class "Default")
      (node (ref "U$551") (pin "1") (pinfunction "P_1") (pintype "passive"))
    )
    (net (code "484") (name "unconnected-(U$552-P-Pad1)") (class "Default")
      (node (ref "U$552") (pin "1") (pinfunction "P_1") (pintype "passive"))
    )
    (net (code "485") (name "unconnected-(U$553-P-Pad1)") (class "Default")
      (node (ref "U$553") (pin "1") (pinfunction "P_1") (pintype "passive"))
    )
    (net (code "486") (name "unconnected-(U$554-P-Pad1)") (class "Default")
      (node (ref "U$554") (pin "1") (pinfunction "P_1") (pintype "passive"))
    )
    (net (code "487") (name "unconnected-(U$555-P-Pad1)") (class "Default")
      (node (ref "U$555") (pin "1") (pinfunction "P_1") (pintype "passive"))
    )
    (net (code "488") (name "unconnected-(U$556-P-Pad1)") (class "Default")
      (node (ref "U$556") (pin "1") (pinfunction "P_1") (pintype "passive"))
    )
    (net (code "489") (name "unconnected-(U$557-P-Pad1)") (class "Default")
      (node (ref "U$557") (pin "1") (pinfunction "P_1") (pintype "passive"))
    )
    (net (code "490") (name "unconnected-(U$558-P-Pad1)") (class "Default")
      (node (ref "U$558") (pin "1") (pinfunction "P_1") (pintype "passive"))
    )
    (net (code "491") (name "unconnected-(U$581-P-Pad1)") (class "Default")
      (node (ref "U$581") (pin "1") (pinfunction "P_1") (pintype "passive"))
    )
    (net (code "492") (name "unconnected-(U$582-P-Pad1)") (class "Default")
      (node (ref "U$582") (pin "1") (pinfunction "P_1") (pintype "passive"))
    )
    (net (code "493") (name "unconnected-(U$583-P-Pad1)") (class "Default")
      (node (ref "U$583") (pin "1") (pinfunction "P_1") (pintype "passive"))
    )
    (net (code "494") (name "unconnected-(U$584-P-Pad1)") (class "Default")
      (node (ref "U$584") (pin "1") (pinfunction "P_1") (pintype "passive"))
    )
    (net (code "495") (name "unconnected-(U$585-P-Pad1)") (class "Default")
      (node (ref "U$585") (pin "1") (pinfunction "P_1") (pintype "passive"))
    )
    (net (code "496") (name "unconnected-(U$586-P-Pad1)") (class "Default")
      (node (ref "U$586") (pin "1") (pinfunction "P_1") (pintype "passive"))
    )
    (net (code "497") (name "unconnected-(U$587-P-Pad1)") (class "Default")
      (node (ref "U$587") (pin "1") (pinfunction "P_1") (pintype "passive"))
    )
    (net (code "498") (name "unconnected-(U$588-P-Pad1)") (class "Default")
      (node (ref "U$588") (pin "1") (pinfunction "P_1") (pintype "passive"))
    )
    (net (code "499") (name "unconnected-(U$589-P-Pad1)") (class "Default")
      (node (ref "U$589") (pin "1") (pinfunction "P_1") (pintype "passive"))
    )
    (net (code "500") (name "unconnected-(U$590-P-Pad1)") (class "Default")
      (node (ref "U$590") (pin "1") (pinfunction "P_1") (pintype "passive"))
    )
    (net (code "501") (name "unconnected-(U$591-P-Pad1)") (class "Default")
      (node (ref "U$591") (pin "1") (pinfunction "P_1") (pintype "passive"))
    )
    (net (code "502") (name "unconnected-(U$592-P-Pad1)") (class "Default")
      (node (ref "U$592") (pin "1") (pinfunction "P_1") (pintype "passive"))
    )
    (net (code "503") (name "unconnected-(U$593-P-Pad1)") (class "Default")
      (node (ref "U$593") (pin "1") (pinfunction "P_1") (pintype "passive"))
    )
    (net (code "504") (name "unconnected-(U$594-P-Pad1)") (class "Default")
      (node (ref "U$594") (pin "1") (pinfunction "P_1") (pintype "passive"))
    )
    (net (code "505") (name "unconnected-(U$595-P-Pad1)") (class "Default")
      (node (ref "U$595") (pin "1") (pinfunction "P_1") (pintype "passive"))
    )
    (net (code "506") (name "unconnected-(U$596-P-Pad1)") (class "Default")
      (node (ref "U$596") (pin "1") (pinfunction "P_1") (pintype "passive"))
    )
    (net (code "507") (name "unconnected-(U$597-P-Pad1)") (class "Default")
      (node (ref "U$597") (pin "1") (pinfunction "P_1") (pintype "passive"))
    )
    (net (code "508") (name "unconnected-(U$598-P-Pad1)") (class "Default")
      (node (ref "U$598") (pin "1") (pinfunction "P_1") (pintype "passive"))
    )
    (net (code "509") (name "unconnected-(U$599-P-Pad1)") (class "Default")
      (node (ref "U$599") (pin "1") (pinfunction "P_1") (pintype "passive"))
    )
    (net (code "510") (name "unconnected-(U$600-P-Pad1)") (class "Default")
      (node (ref "U$600") (pin "1") (pinfunction "P_1") (pintype "passive"))
    )
    (net (code "511") (name "unconnected-(U$601-P-Pad1)") (class "Default")
      (node (ref "U$601") (pin "1") (pinfunction "P_1") (pintype "passive"))
    )
    (net (code "512") (name "unconnected-(U$602-P-Pad1)") (class "Default")
      (node (ref "U$602") (pin "1") (pinfunction "P_1") (pintype "passive"))
    )
    (net (code "513") (name "unconnected-(U$603-P-Pad1)") (class "Default")
      (node (ref "U$603") (pin "1") (pinfunction "P_1") (pintype "passive"))
    )
    (net (code "514") (name "unconnected-(U$604-P-Pad1)") (class "Default")
      (node (ref "U$604") (pin "1") (pinfunction "P_1") (pintype "passive"))
    )
    (net (code "515") (name "unconnected-(U$605-P-Pad1)") (class "Default")
      (node (ref "U$605") (pin "1") (pinfunction "P_1") (pintype "passive"))
    )
    (net (code "516") (name "unconnected-(U$606-P-Pad1)") (class "Default")
      (node (ref "U$606") (pin "1") (pinfunction "P_1") (pintype "passive"))
    )
    (net (code "517") (name "unconnected-(U$607-P-Pad1)") (class "Default")
      (node (ref "U$607") (pin "1") (pinfunction "P_1") (pintype "passive"))
    )
    (net (code "518") (name "unconnected-(U$608-P-Pad1)") (class "Default")
      (node (ref "U$608") (pin "1") (pinfunction "P_1") (pintype "passive"))
    )
    (net (code "519") (name "unconnected-(U$609-P-Pad1)") (class "Default")
      (node (ref "U$609") (pin "1") (pinfunction "P_1") (pintype "passive"))
    )
    (net (code "520") (name "unconnected-(U$610-P-Pad1)") (class "Default")
      (node (ref "U$610") (pin "1") (pinfunction "P_1") (pintype "passive"))
    )
    (net (code "521") (name "unconnected-(U$611-P-Pad1)") (class "Default")
      (node (ref "U$611") (pin "1") (pinfunction "P_1") (pintype "passive"))
    )
    (net (code "522") (name "unconnected-(U$612-P-Pad1)") (class "Default")
      (node (ref "U$612") (pin "1") (pinfunction "P_1") (pintype "passive"))
    )
    (net (code "523") (name "unconnected-(U$613-P-Pad1)") (class "Default")
      (node (ref "U$613") (pin "1") (pinfunction "P_1") (pintype "passive"))
    )
    (net (code "524") (name "unconnected-(U$614-P-Pad1)") (class "Default")
      (node (ref "U$614") (pin "1") (pinfunction "P_1") (pintype "passive"))
    )
    (net (code "525") (name "unconnected-(U$615-P-Pad1)") (class "Default")
      (node (ref "U$615") (pin "1") (pinfunction "P_1") (pintype "passive"))
    )
    (net (code "526") (name "unconnected-(U$616-P-Pad1)") (class "Default")
      (node (ref "U$616") (pin "1") (pinfunction "P_1") (pintype "passive"))
    )
    (net (code "527") (name "unconnected-(U$617-P-Pad1)") (class "Default")
      (node (ref "U$617") (pin "1") (pinfunction "P_1") (pintype "passive"))
    )
    (net (code "528") (name "unconnected-(U$618-P-Pad1)") (class "Default")
      (node (ref "U$618") (pin "1") (pinfunction "P_1") (pintype "passive"))
    )
    (net (code "529") (name "unconnected-(U$619-P-Pad1)") (class "Default")
      (node (ref "U$619") (pin "1") (pinfunction "P_1") (pintype "passive"))
    )
    (net (code "530") (name "unconnected-(U$620-P-Pad1)") (class "Default")
      (node (ref "U$620") (pin "1") (pinfunction "P_1") (pintype "passive"))
    )
    (net (code "531") (name "unconnected-(U$621-P-Pad1)") (class "Default")
      (node (ref "U$621") (pin "1") (pinfunction "P_1") (pintype "passive"))
    )
    (net (code "532") (name "unconnected-(U$622-P-Pad1)") (class "Default")
      (node (ref "U$622") (pin "1") (pinfunction "P_1") (pintype "passive"))
    )
    (net (code "533") (name "unconnected-(U$623-P-Pad1)") (class "Default")
      (node (ref "U$623") (pin "1") (pinfunction "P_1") (pintype "passive"))
    )
    (net (code "534") (name "unconnected-(U$624-P-Pad1)") (class "Default")
      (node (ref "U$624") (pin "1") (pinfunction "P_1") (pintype "passive"))
    )
    (net (code "535") (name "unconnected-(U$625-P-Pad1)") (class "Default")
      (node (ref "U$625") (pin "1") (pinfunction "P_1") (pintype "passive"))
    )
    (net (code "536") (name "unconnected-(U$626-P-Pad1)") (class "Default")
      (node (ref "U$626") (pin "1") (pinfunction "P_1") (pintype "passive"))
    )
    (net (code "537") (name "unconnected-(U$627-P-Pad1)") (class "Default")
      (node (ref "U$627") (pin "1") (pinfunction "P_1") (pintype "passive"))
    )
    (net (code "538") (name "unconnected-(U$628-P-Pad1)") (class "Default")
      (node (ref "U$628") (pin "1") (pinfunction "P_1") (pintype "passive"))
    )
    (net (code "539") (name "unconnected-(U$629-P-Pad1)") (class "Default")
      (node (ref "U$629") (pin "1") (pinfunction "P_1") (pintype "passive"))
    )
    (net (code "540") (name "unconnected-(U$630-P-Pad1)") (class "Default")
      (node (ref "U$630") (pin "1") (pinfunction "P_1") (pintype "passive"))
    )
    (net (code "541") (name "unconnected-(U$631-P-Pad1)") (class "Default")
      (node (ref "U$631") (pin "1") (pinfunction "P_1") (pintype "passive"))
    )
    (net (code "542") (name "unconnected-(U$632-P-Pad1)") (class "Default")
      (node (ref "U$632") (pin "1") (pinfunction "P_1") (pintype "passive"))
    )
    (net (code "543") (name "unconnected-(U$633-P-Pad1)") (class "Default")
      (node (ref "U$633") (pin "1") (pinfunction "P_1") (pintype "passive"))
    )
    (net (code "544") (name "unconnected-(U$634-P-Pad1)") (class "Default")
      (node (ref "U$634") (pin "1") (pinfunction "P_1") (pintype "passive"))
    )
    (net (code "545") (name "unconnected-(U$635-P-Pad1)") (class "Default")
      (node (ref "U$635") (pin "1") (pinfunction "P_1") (pintype "passive"))
    )
    (net (code "546") (name "unconnected-(U$636-P-Pad1)") (class "Default")
      (node (ref "U$636") (pin "1") (pinfunction "P_1") (pintype "passive"))
    )
    (net (code "547") (name "unconnected-(U$637-P-Pad1)") (class "Default")
      (node (ref "U$637") (pin "1") (pinfunction "P_1") (pintype "passive"))
    )
    (net (code "548") (name "unconnected-(U$638-P-Pad1)") (class "Default")
      (node (ref "U$638") (pin "1") (pinfunction "P_1") (pintype "passive"))
    )
    (net (code "549") (name "unconnected-(U$639-P-Pad1)") (class "Default")
      (node (ref "U$639") (pin "1") (pinfunction "P_1") (pintype "passive"))
    )
    (net (code "550") (name "unconnected-(U$640-P-Pad1)") (class "Default")
      (node (ref "U$640") (pin "1") (pinfunction "P_1") (pintype "passive"))
    )
    (net (code "551") (name "unconnected-(U$641-P-Pad1)") (class "Default")
      (node (ref "U$641") (pin "1") (pinfunction "P_1") (pintype "passive"))
    )
    (net (code "552") (name "unconnected-(U$642-P-Pad1)") (class "Default")
      (node (ref "U$642") (pin "1") (pinfunction "P_1") (pintype "passive"))
    )
    (net (code "553") (name "unconnected-(U$643-P-Pad1)") (class "Default")
      (node (ref "U$643") (pin "1") (pinfunction "P_1") (pintype "passive"))
    )
    (net (code "554") (name "unconnected-(U$644-P-Pad1)") (class "Default")
      (node (ref "U$644") (pin "1") (pinfunction "P_1") (pintype "passive"))
    )
    (net (code "555") (name "unconnected-(U$645-P-Pad1)") (class "Default")
      (node (ref "U$645") (pin "1") (pinfunction "P_1") (pintype "passive"))
    )
    (net (code "556") (name "unconnected-(U$646-P-Pad1)") (class "Default")
      (node (ref "U$646") (pin "1") (pinfunction "P_1") (pintype "passive"))
    )
    (net (code "557") (name "unconnected-(U$647-P-Pad1)") (class "Default")
      (node (ref "U$647") (pin "1") (pinfunction "P_1") (pintype "passive"))
    )
    (net (code "558") (name "unconnected-(U$648-P-Pad1)") (class "Default")
      (node (ref "U$648") (pin "1") (pinfunction "P_1") (pintype "passive"))
    )
    (net (code "559") (name "unconnected-(U$649-P-Pad1)") (class "Default")
      (node (ref "U$649") (pin "1") (pinfunction "P_1") (pintype "passive"))
    )
    (net (code "560") (name "unconnected-(U$650-P-Pad1)") (class "Default")
      (node (ref "U$650") (pin "1") (pinfunction "P_1") (pintype "passive"))
    )
    (net (code "561") (name "unconnected-(U$651-P-Pad1)") (class "Default")
      (node (ref "U$651") (pin "1") (pinfunction "P_1") (pintype "passive"))
    )
    (net (code "562") (name "unconnected-(U$652-P-Pad1)") (class "Default")
      (node (ref "U$652") (pin "1") (pinfunction "P_1") (pintype "passive"))
    )
    (net (code "563") (name "unconnected-(U$653-P-Pad1)") (class "Default")
      (node (ref "U$653") (pin "1") (pinfunction "P_1") (pintype "passive"))
    )
    (net (code "564") (name "unconnected-(U$654-P-Pad1)") (class "Default")
      (node (ref "U$654") (pin "1") (pinfunction "P_1") (pintype "passive"))
    )
    (net (code "565") (name "unconnected-(U$655-P-Pad1)") (class "Default")
      (node (ref "U$655") (pin "1") (pinfunction "P_1") (pintype "passive"))
    )
    (net (code "566") (name "unconnected-(U$656-P-Pad1)") (class "Default")
      (node (ref "U$656") (pin "1") (pinfunction "P_1") (pintype "passive"))
    )
    (net (code "567") (name "unconnected-(U$657-P-Pad1)") (class "Default")
      (node (ref "U$657") (pin "1") (pinfunction "P_1") (pintype "passive"))
    )
    (net (code "568") (name "unconnected-(U$658-P-Pad1)") (class "Default")
      (node (ref "U$658") (pin "1") (pinfunction "P_1") (pintype "passive"))
    )
    (net (code "569") (name "unconnected-(U$659-P-Pad1)") (class "Default")
      (node (ref "U$659") (pin "1") (pinfunction "P_1") (pintype "passive"))
    )
    (net (code "570") (name "unconnected-(U$660-P-Pad1)") (class "Default")
      (node (ref "U$660") (pin "1") (pinfunction "P_1") (pintype "passive"))
    )
    (net (code "571") (name "unconnected-(U$661-P-Pad1)") (class "Default")
      (node (ref "U$661") (pin "1") (pinfunction "P_1") (pintype "passive"))
    )
    (net (code "572") (name "unconnected-(U$662-P-Pad1)") (class "Default")
      (node (ref "U$662") (pin "1") (pinfunction "P_1") (pintype "passive"))
    )
    (net (code "573") (name "unconnected-(U$663-P-Pad1)") (class "Default")
      (node (ref "U$663") (pin "1") (pinfunction "P_1") (pintype "passive"))
    )
    (net (code "574") (name "unconnected-(U$664-P-Pad1)") (class "Default")
      (node (ref "U$664") (pin "1") (pinfunction "P_1") (pintype "passive"))
    )
    (net (code "575") (name "unconnected-(U$665-P-Pad1)") (class "Default")
      (node (ref "U$665") (pin "1") (pinfunction "P_1") (pintype "passive"))
    )
    (net (code "576") (name "unconnected-(U$666-P-Pad1)") (class "Default")
      (node (ref "U$666") (pin "1") (pinfunction "P_1") (pintype "passive"))
    )
    (net (code "577") (name "unconnected-(U$667-P-Pad1)") (class "Default")
      (node (ref "U$667") (pin "1") (pinfunction "P_1") (pintype "passive"))
    )
    (net (code "578") (name "unconnected-(U$668-P-Pad1)") (class "Default")
      (node (ref "U$668") (pin "1") (pinfunction "P_1") (pintype "passive"))
    )
    (net (code "579") (name "unconnected-(U$669-P-Pad1)") (class "Default")
      (node (ref "U$669") (pin "1") (pinfunction "P_1") (pintype "passive"))
    )
    (net (code "580") (name "unconnected-(U$670-P-Pad1)") (class "Default")
      (node (ref "U$670") (pin "1") (pinfunction "P_1") (pintype "passive"))
    )
    (net (code "581") (name "unconnected-(U$671-P-Pad1)") (class "Default")
      (node (ref "U$671") (pin "1") (pinfunction "P_1") (pintype "passive"))
    )
    (net (code "582") (name "unconnected-(U$672-P-Pad1)") (class "Default")
      (node (ref "U$672") (pin "1") (pinfunction "P_1") (pintype "passive"))
    )
    (net (code "583") (name "unconnected-(U$673-P-Pad1)") (class "Default")
      (node (ref "U$673") (pin "1") (pinfunction "P_1") (pintype "passive"))
    )
    (net (code "584") (name "unconnected-(U$674-P-Pad1)") (class "Default")
      (node (ref "U$674") (pin "1") (pinfunction "P_1") (pintype "passive"))
    )
    (net (code "585") (name "unconnected-(U$675-P-Pad1)") (class "Default")
      (node (ref "U$675") (pin "1") (pinfunction "P_1") (pintype "passive"))
    )
    (net (code "586") (name "unconnected-(U$676-P-Pad1)") (class "Default")
      (node (ref "U$676") (pin "1") (pinfunction "P_1") (pintype "passive"))
    )
    (net (code "587") (name "unconnected-(U$677-P-Pad1)") (class "Default")
      (node (ref "U$677") (pin "1") (pinfunction "P_1") (pintype "passive"))
    )
    (net (code "588") (name "unconnected-(U$678-P-Pad1)") (class "Default")
      (node (ref "U$678") (pin "1") (pinfunction "P_1") (pintype "passive"))
    )
    (net (code "589") (name "unconnected-(U$679-P-Pad1)") (class "Default")
      (node (ref "U$679") (pin "1") (pinfunction "P_1") (pintype "passive"))
    )
    (net (code "590") (name "unconnected-(U$680-P-Pad1)") (class "Default")
      (node (ref "U$680") (pin "1") (pinfunction "P_1") (pintype "passive"))
    )
    (net (code "591") (name "unconnected-(U$703-P-Pad1)") (class "Default")
      (node (ref "U$703") (pin "1") (pinfunction "P_1") (pintype "passive"))
    )
    (net (code "592") (name "unconnected-(U$704-P-Pad1)") (class "Default")
      (node (ref "U$704") (pin "1") (pinfunction "P_1") (pintype "passive"))
    )
    (net (code "593") (name "unconnected-(U$705-P-Pad1)") (class "Default")
      (node (ref "U$705") (pin "1") (pinfunction "P_1") (pintype "passive"))
    )
    (net (code "594") (name "unconnected-(U$706-P-Pad1)") (class "Default")
      (node (ref "U$706") (pin "1") (pinfunction "P_1") (pintype "passive"))
    )
    (net (code "595") (name "unconnected-(U$707-P-Pad1)") (class "Default")
      (node (ref "U$707") (pin "1") (pinfunction "P_1") (pintype "passive"))
    )
    (net (code "596") (name "unconnected-(U$708-P-Pad1)") (class "Default")
      (node (ref "U$708") (pin "1") (pinfunction "P_1") (pintype "passive"))
    )
    (net (code "597") (name "unconnected-(U$709-P-Pad1)") (class "Default")
      (node (ref "U$709") (pin "1") (pinfunction "P_1") (pintype "passive"))
    )
    (net (code "598") (name "unconnected-(U$710-P-Pad1)") (class "Default")
      (node (ref "U$710") (pin "1") (pinfunction "P_1") (pintype "passive"))
    )
    (net (code "599") (name "unconnected-(U$711-P-Pad1)") (class "Default")
      (node (ref "U$711") (pin "1") (pinfunction "P_1") (pintype "passive"))
    )
    (net (code "600") (name "unconnected-(U$712-P-Pad1)") (class "Default")
      (node (ref "U$712") (pin "1") (pinfunction "P_1") (pintype "passive"))
    )
    (net (code "601") (name "unconnected-(U$713-P-Pad1)") (class "Default")
      (node (ref "U$713") (pin "1") (pinfunction "P_1") (pintype "passive"))
    )
    (net (code "602") (name "unconnected-(U$714-P-Pad1)") (class "Default")
      (node (ref "U$714") (pin "1") (pinfunction "P_1") (pintype "passive"))
    )
    (net (code "603") (name "unconnected-(U$715-P-Pad1)") (class "Default")
      (node (ref "U$715") (pin "1") (pinfunction "P_1") (pintype "passive"))
    )
    (net (code "604") (name "unconnected-(U$716-P-Pad1)") (class "Default")
      (node (ref "U$716") (pin "1") (pinfunction "P_1") (pintype "passive"))
    )
    (net (code "605") (name "unconnected-(U$717-P-Pad1)") (class "Default")
      (node (ref "U$717") (pin "1") (pinfunction "P_1") (pintype "passive"))
    )
    (net (code "606") (name "unconnected-(U$718-P-Pad1)") (class "Default")
      (node (ref "U$718") (pin "1") (pinfunction "P_1") (pintype "passive"))
    )
    (net (code "607") (name "unconnected-(U$719-P-Pad1)") (class "Default")
      (node (ref "U$719") (pin "1") (pinfunction "P_1") (pintype "passive"))
    )
    (net (code "608") (name "unconnected-(U$720-P-Pad1)") (class "Default")
      (node (ref "U$720") (pin "1") (pinfunction "P_1") (pintype "passive"))
    )
    (net (code "609") (name "unconnected-(U$721-P-Pad1)") (class "Default")
      (node (ref "U$721") (pin "1") (pinfunction "P_1") (pintype "passive"))
    )
    (net (code "610") (name "unconnected-(U$722-P-Pad1)") (class "Default")
      (node (ref "U$722") (pin "1") (pinfunction "P_1") (pintype "passive"))
    )
    (net (code "611") (name "unconnected-(U$723-P-Pad1)") (class "Default")
      (node (ref "U$723") (pin "1") (pinfunction "P_1") (pintype "passive"))
    )
    (net (code "612") (name "unconnected-(U$724-P-Pad1)") (class "Default")
      (node (ref "U$724") (pin "1") (pinfunction "P_1") (pintype "passive"))
    )
    (net (code "613") (name "unconnected-(U$725-P-Pad1)") (class "Default")
      (node (ref "U$725") (pin "1") (pinfunction "P_1") (pintype "passive"))
    )
    (net (code "614") (name "unconnected-(U$726-P-Pad1)") (class "Default")
      (node (ref "U$726") (pin "1") (pinfunction "P_1") (pintype "passive"))
    )
    (net (code "615") (name "unconnected-(U$727-P-Pad1)") (class "Default")
      (node (ref "U$727") (pin "1") (pinfunction "P_1") (pintype "passive"))
    )
    (net (code "616") (name "unconnected-(U$728-P-Pad1)") (class "Default")
      (node (ref "U$728") (pin "1") (pinfunction "P_1") (pintype "passive"))
    )
    (net (code "617") (name "unconnected-(U$729-P-Pad1)") (class "Default")
      (node (ref "U$729") (pin "1") (pinfunction "P_1") (pintype "passive"))
    )
    (net (code "618") (name "unconnected-(U$730-P-Pad1)") (class "Default")
      (node (ref "U$730") (pin "1") (pinfunction "P_1") (pintype "passive"))
    )
    (net (code "619") (name "unconnected-(U$731-P-Pad1)") (class "Default")
      (node (ref "U$731") (pin "1") (pinfunction "P_1") (pintype "passive"))
    )
    (net (code "620") (name "unconnected-(U$732-P-Pad1)") (class "Default")
      (node (ref "U$732") (pin "1") (pinfunction "P_1") (pintype "passive"))
    )
  )
)
